# Glasses.net
KiCad netlist of a schematic drawn in EAGLE
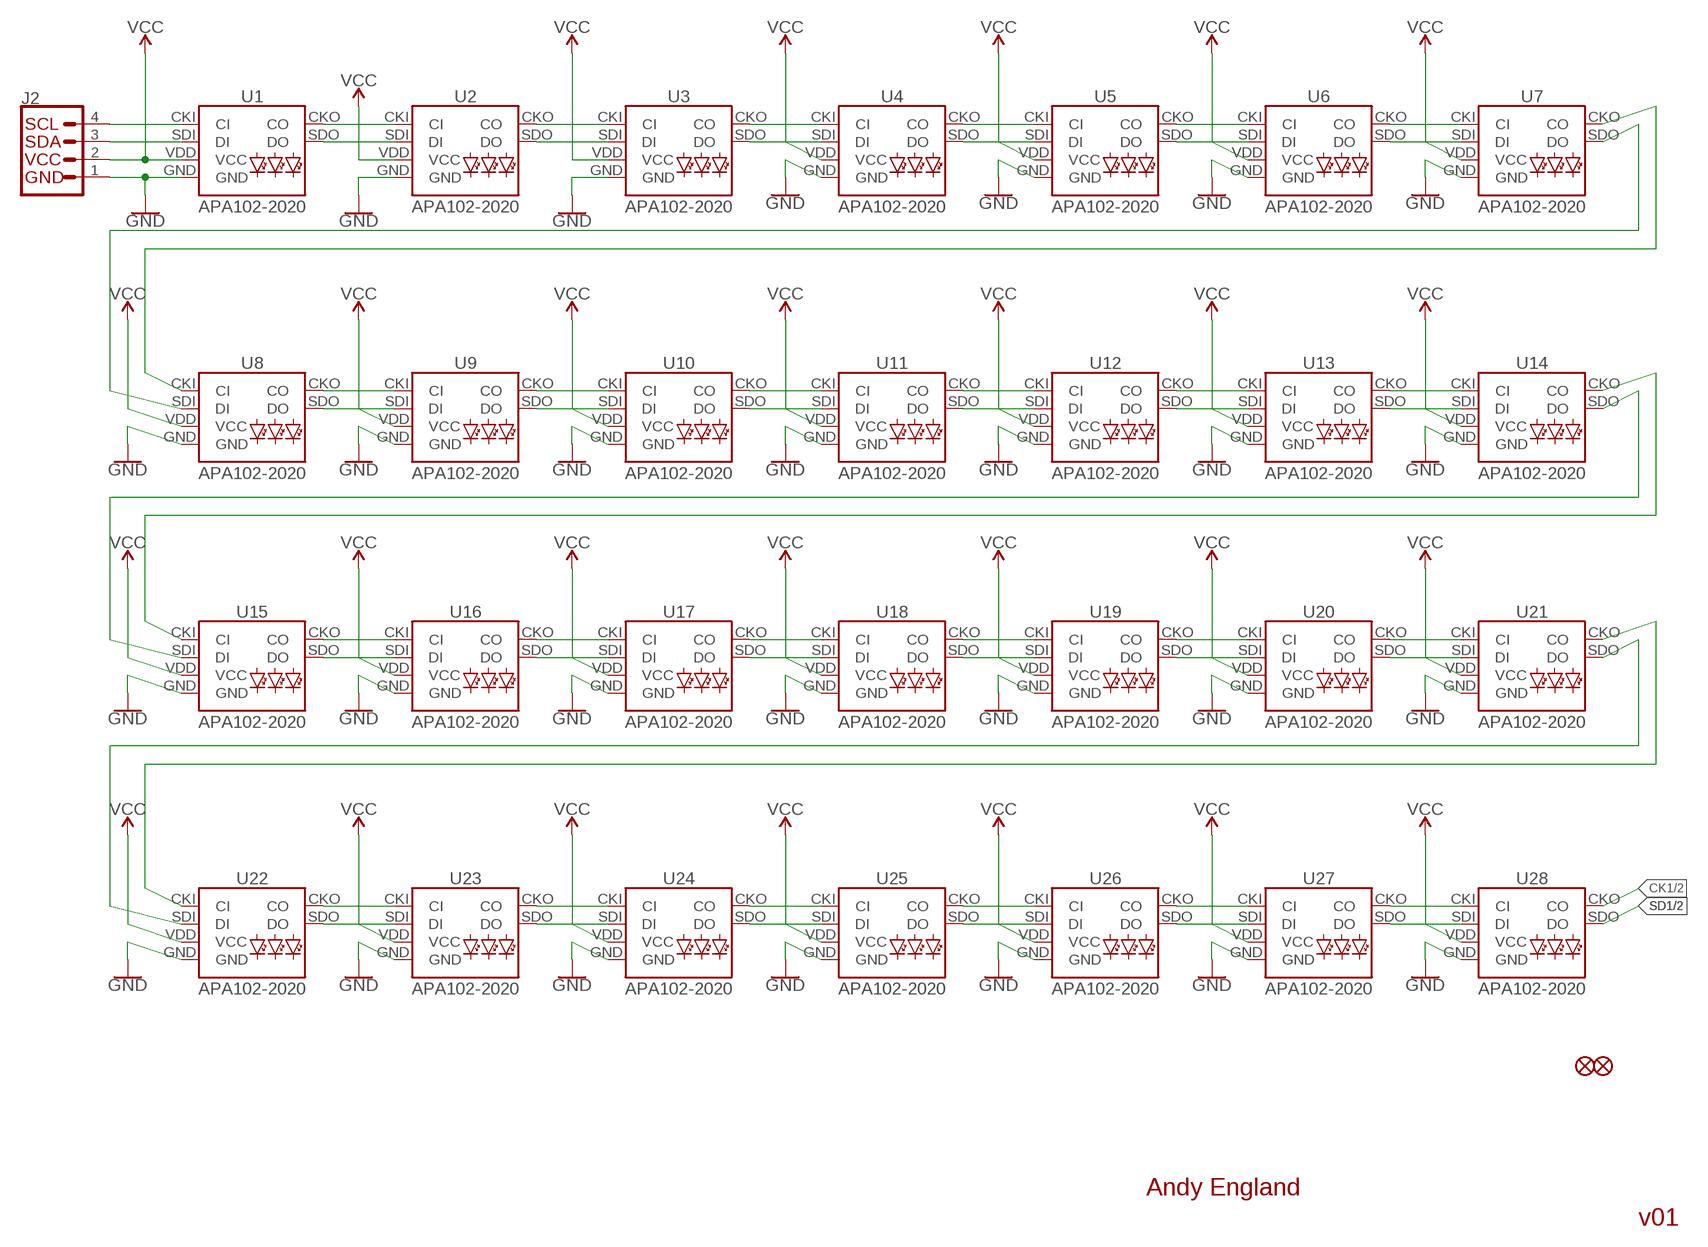
[diagram p0: schematic, sheet 1]
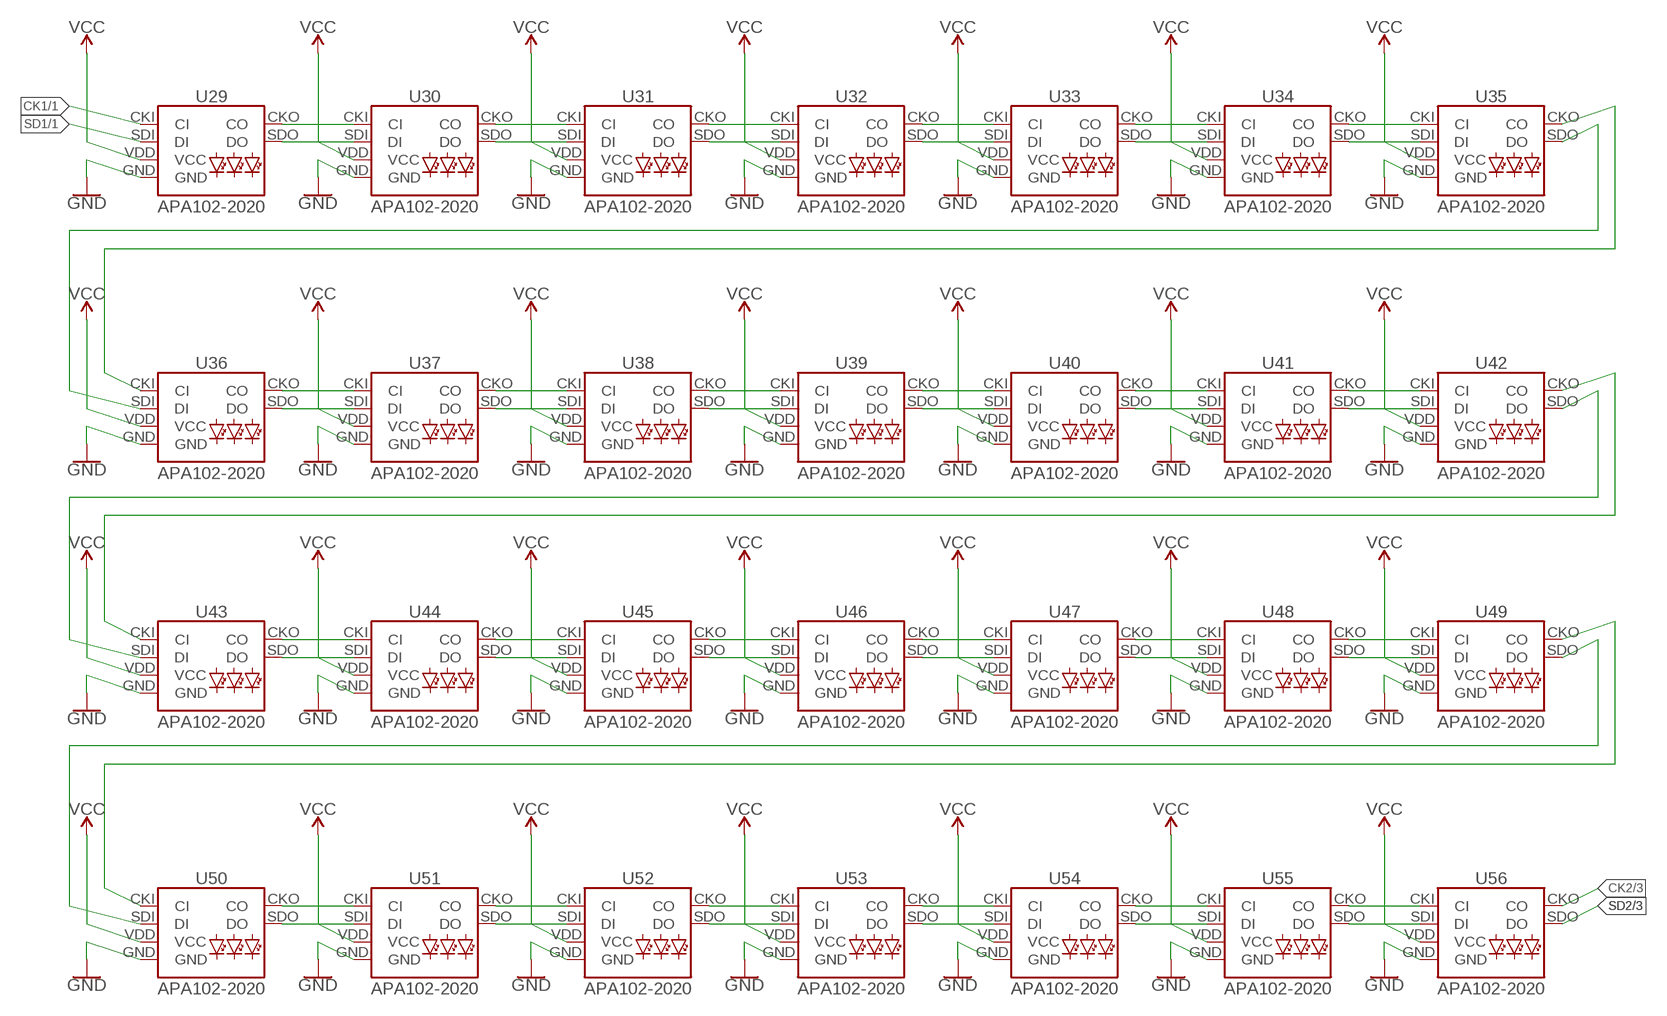
[diagram p1: schematic, sheet 2]
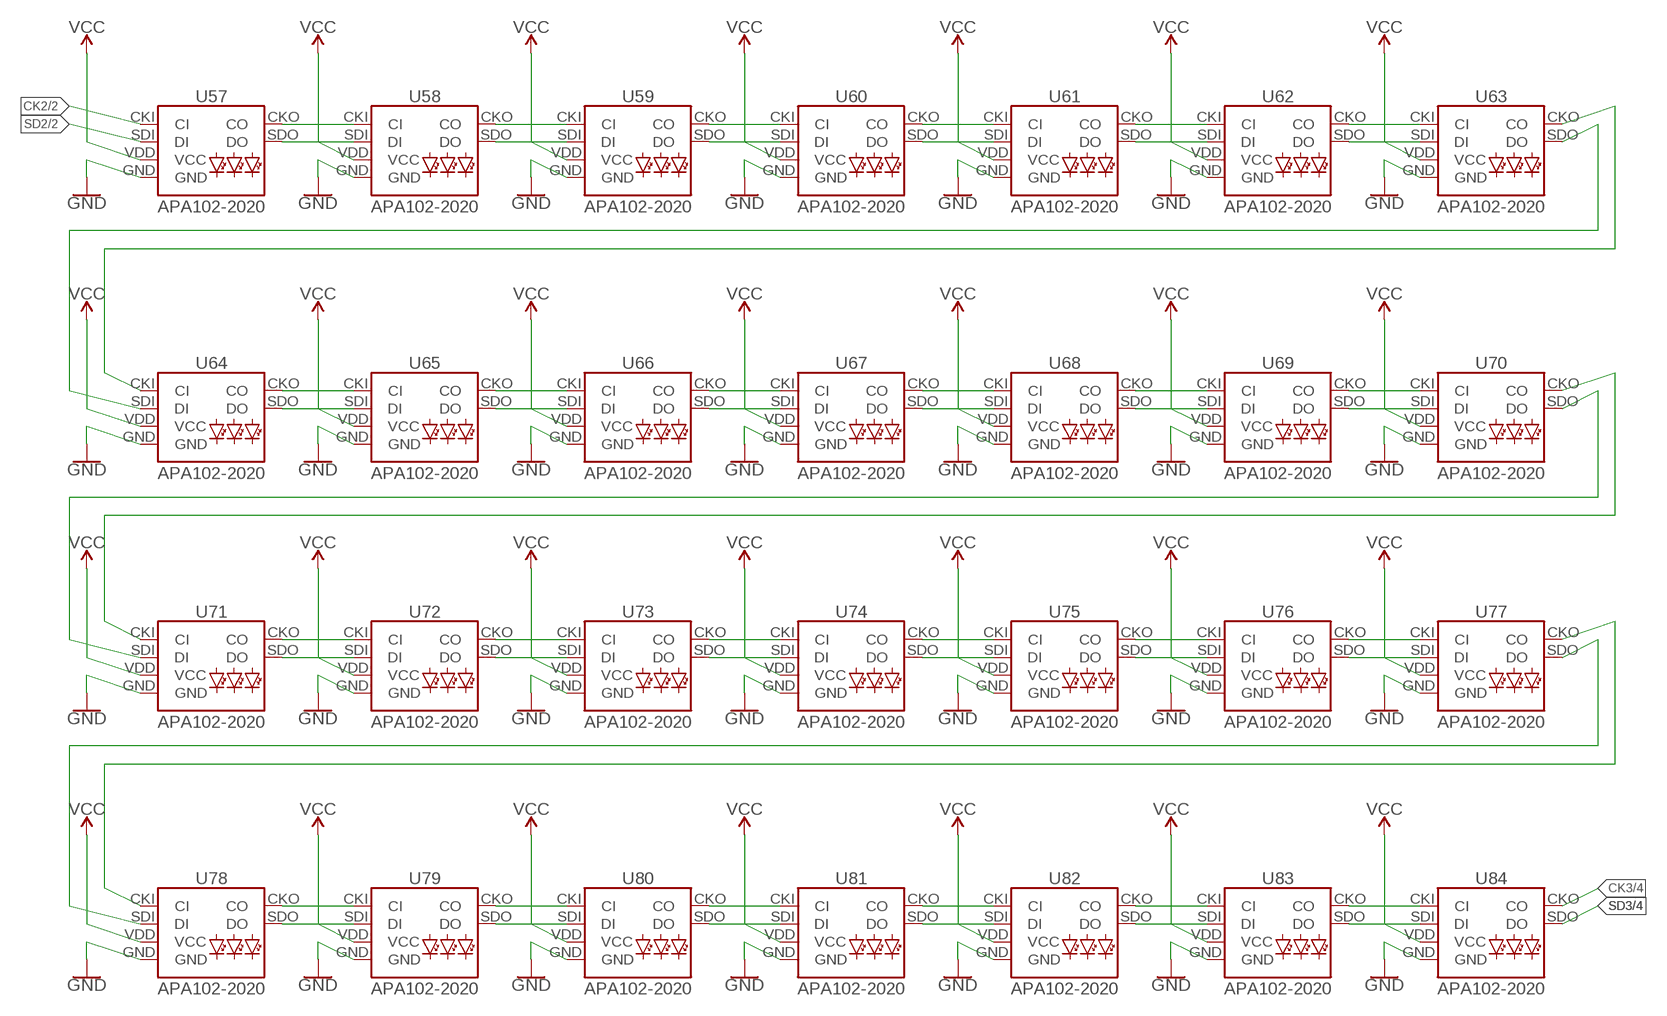
[diagram p2: schematic, sheet 3]
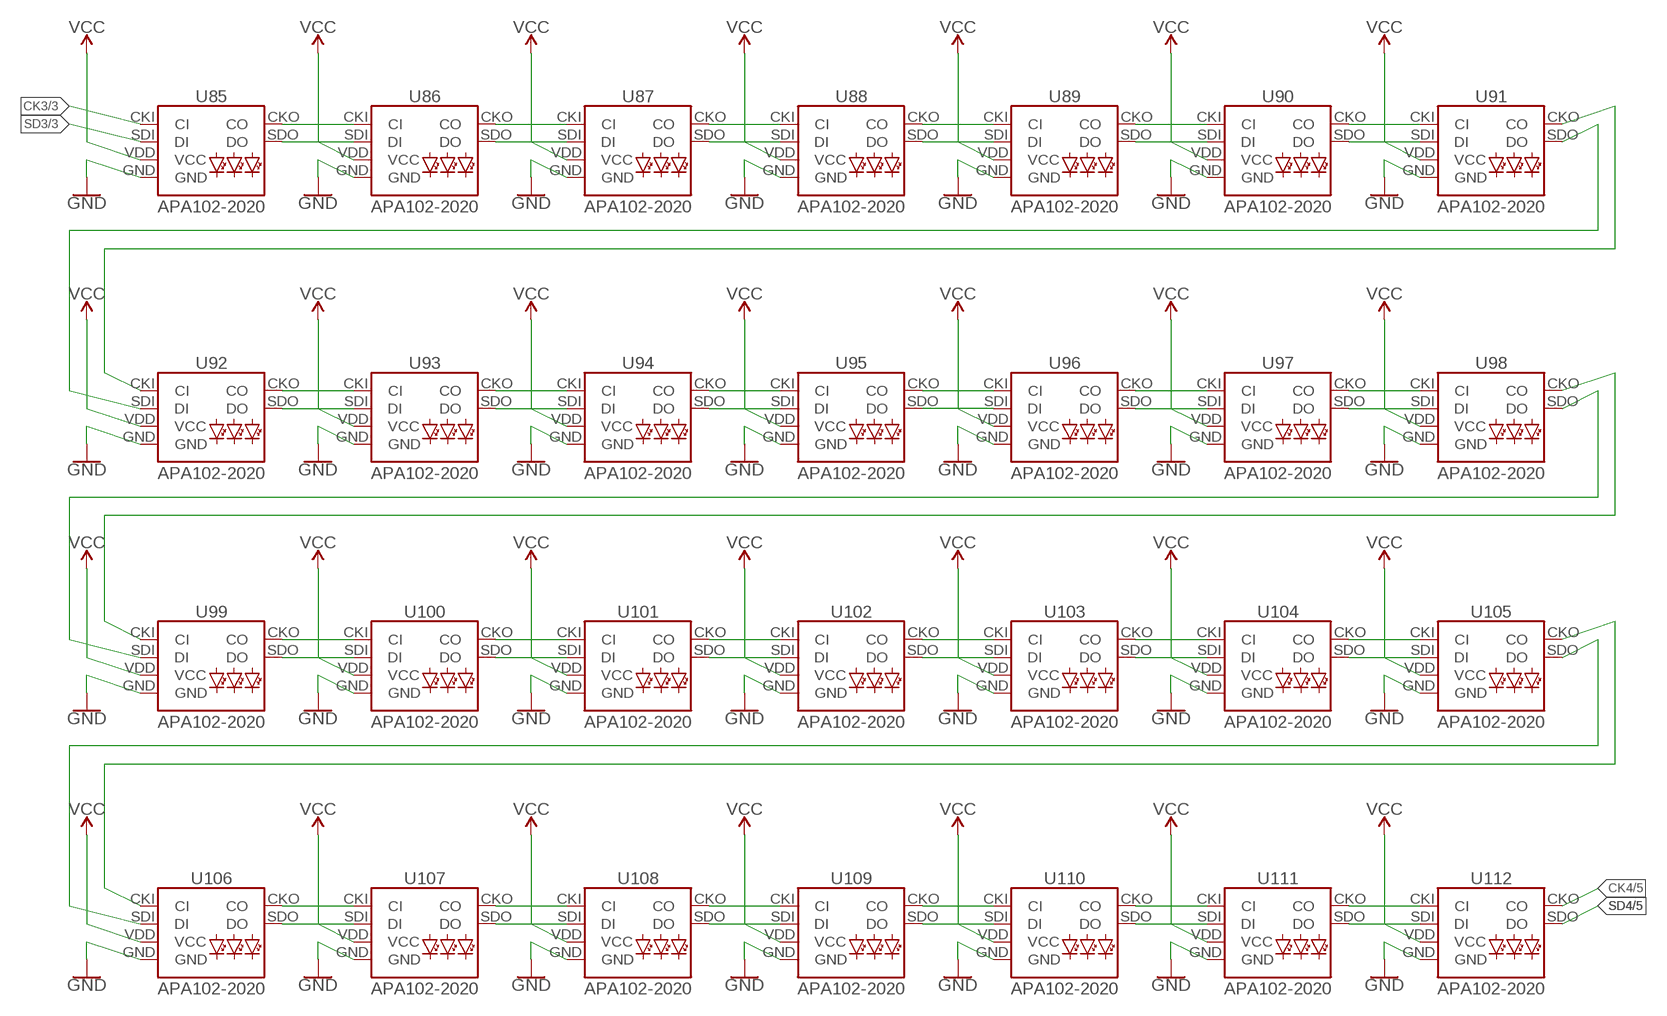
[diagram p3: schematic, sheet 4]
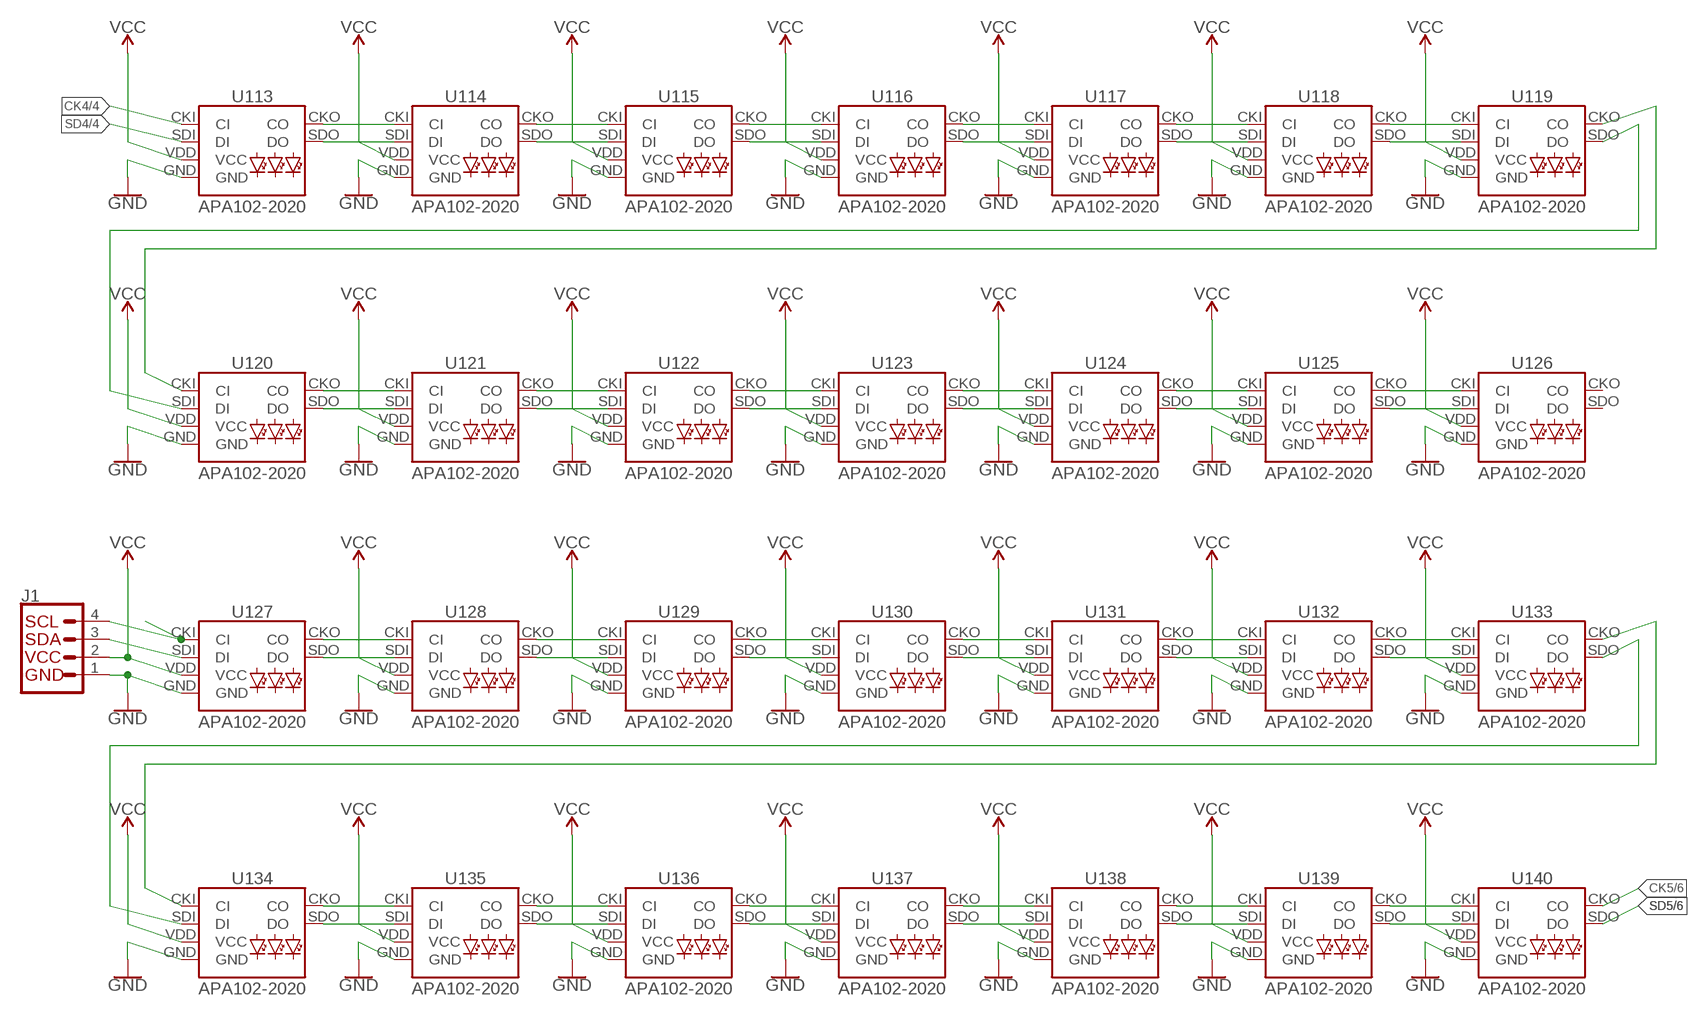
[diagram p4: schematic, sheet 5]
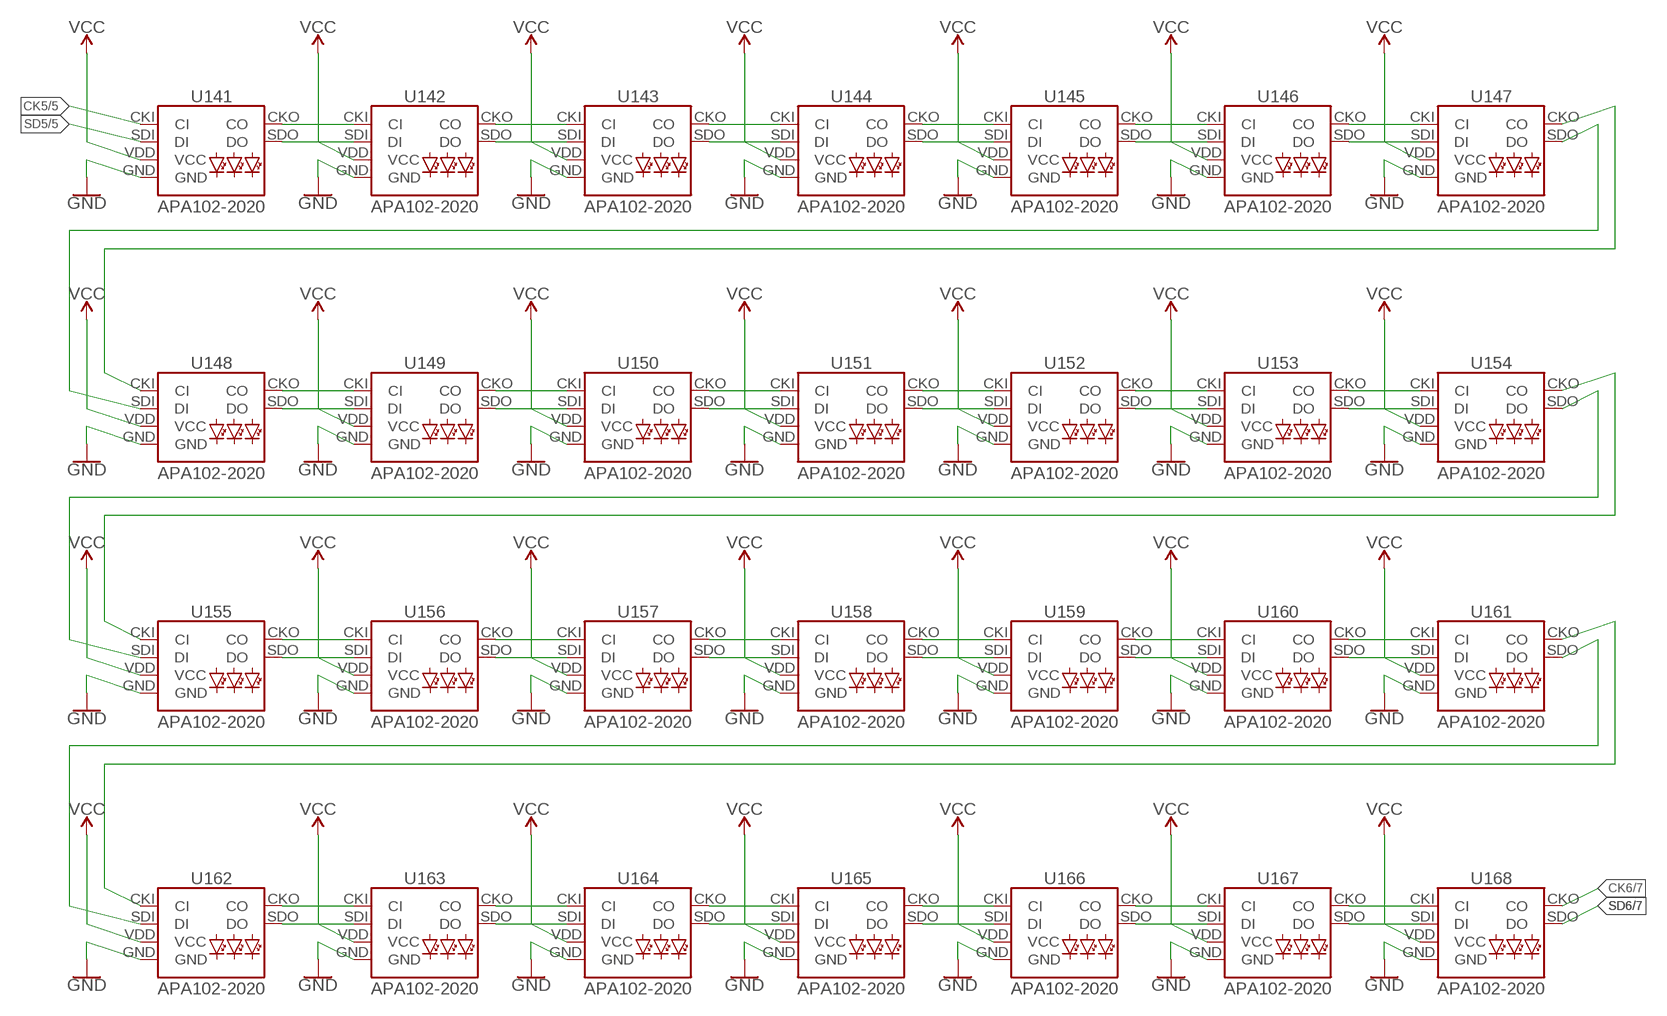
[diagram p5: schematic, sheet 6]
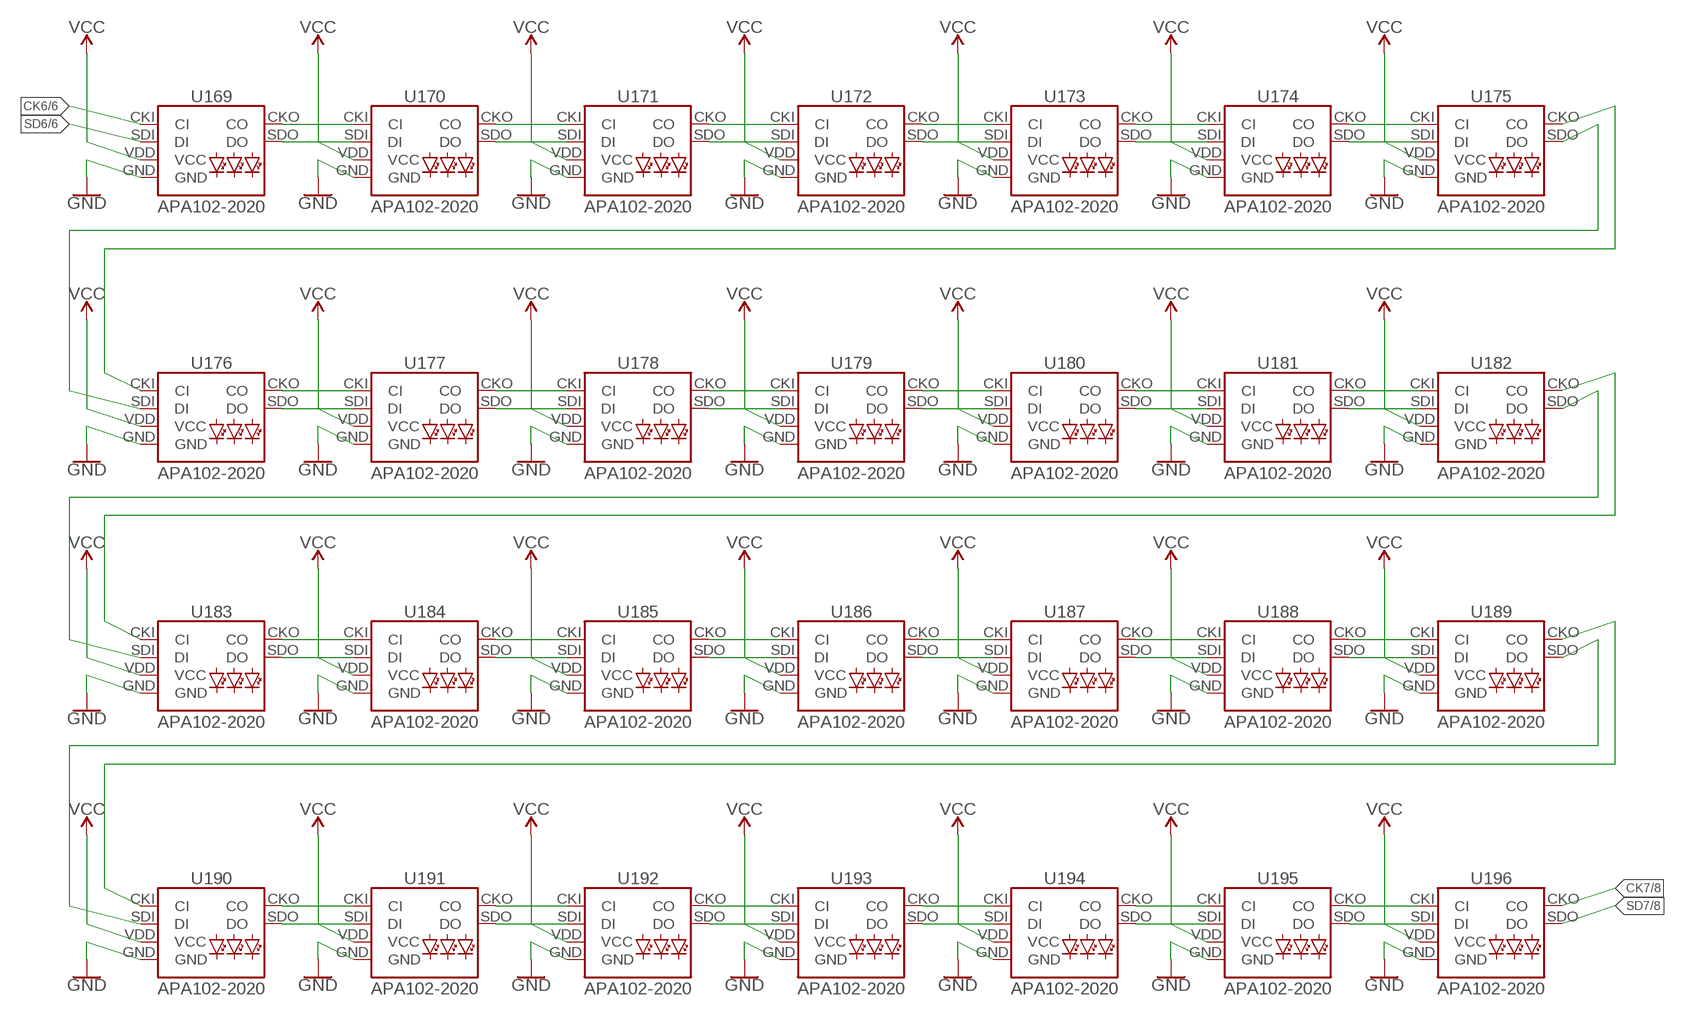
[diagram p6: schematic, sheet 7]
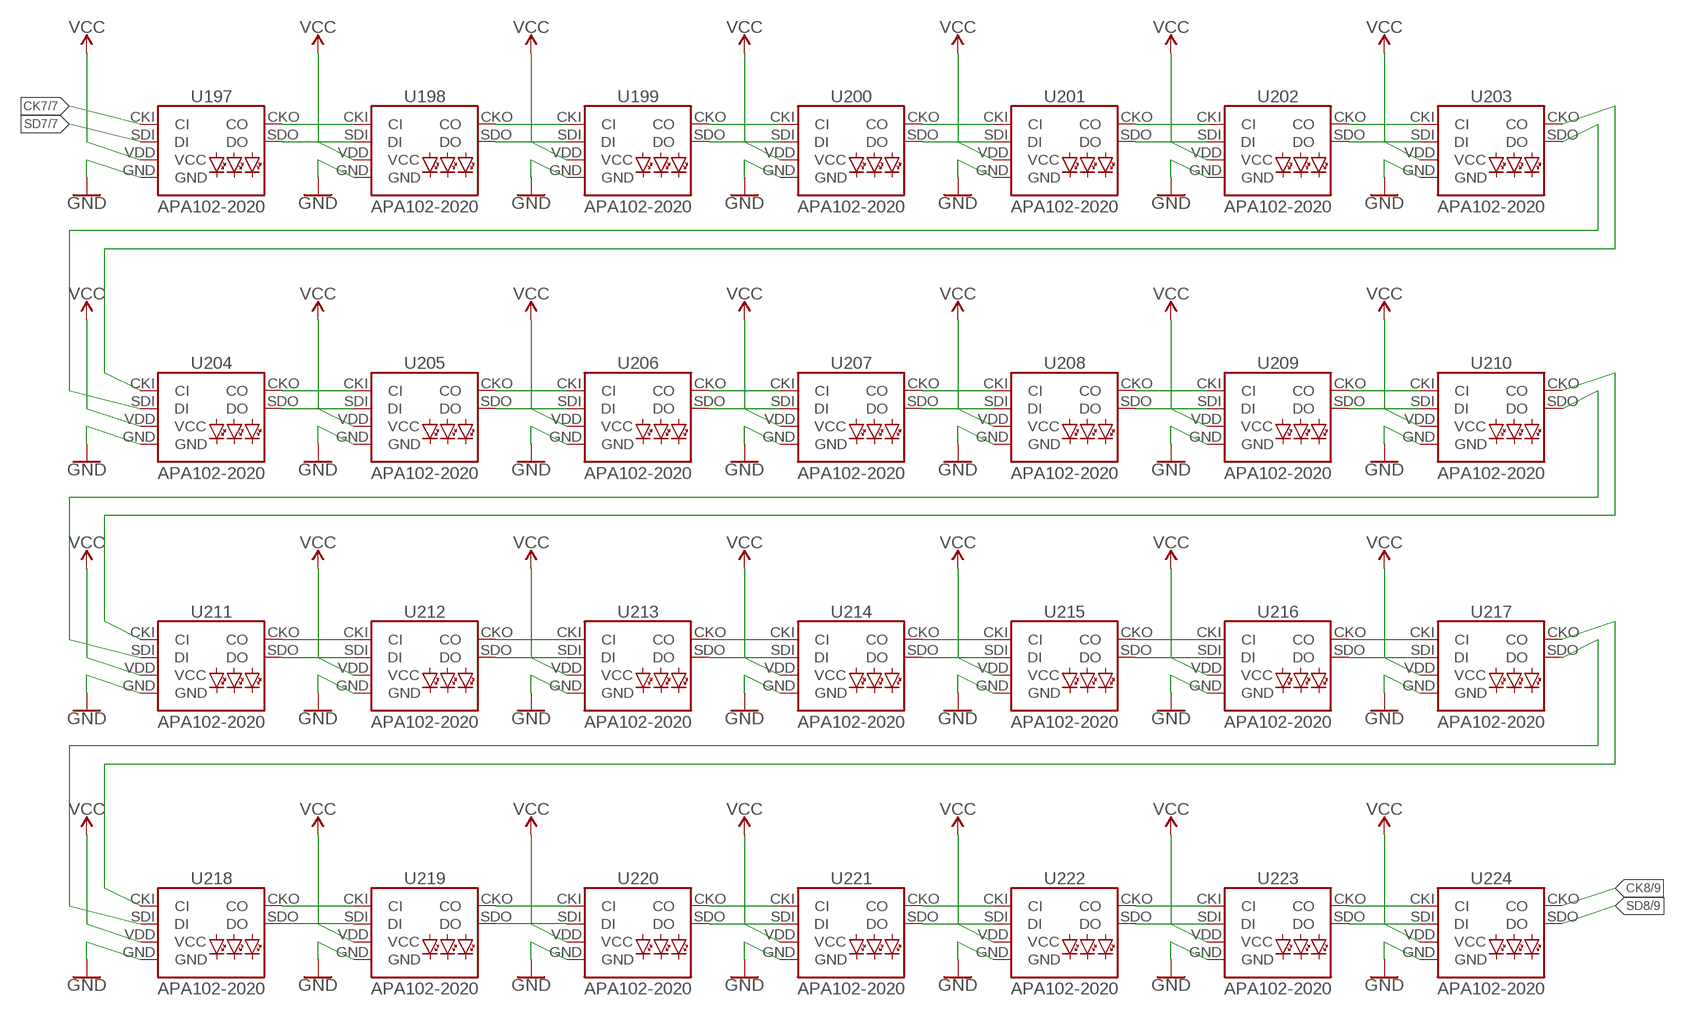
[diagram p7: schematic, sheet 8]
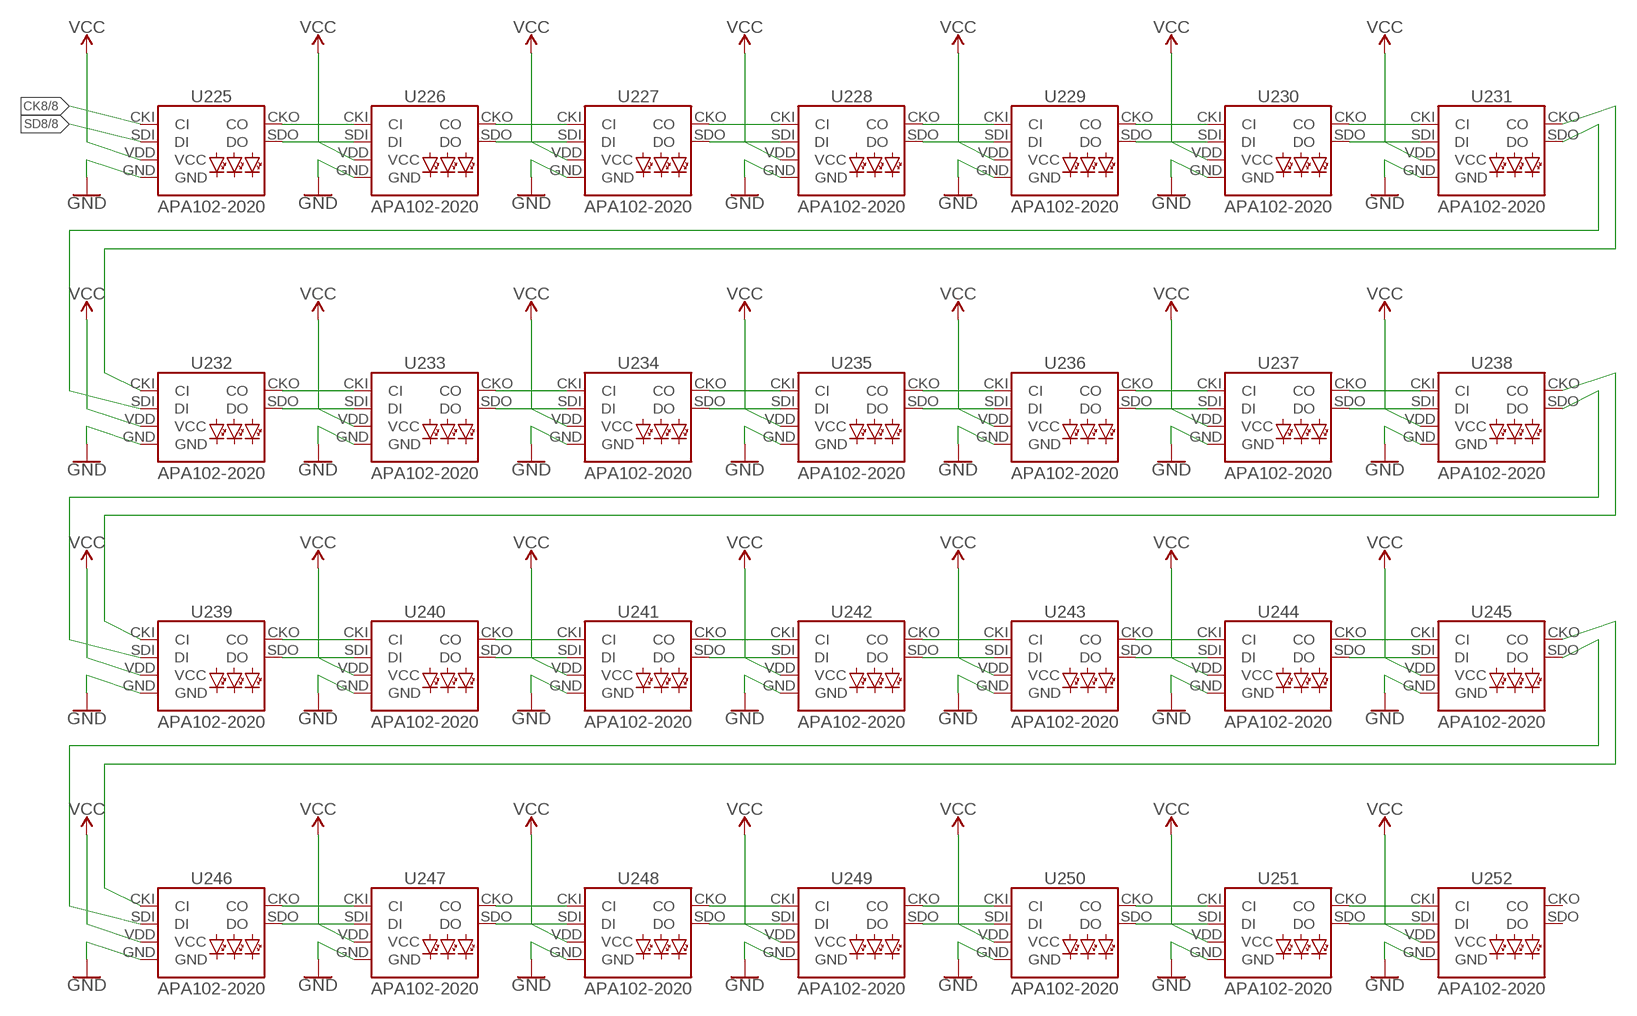
[diagram p8: schematic, sheet 9]

(export (version "E")
  (design (tool "Eeschema 10.0.6"))
  (components
    (comp (ref "U29")
      (value "APA102-2020")
      (footprint "eagle-import:APA102-2020")
      (libsource (lib "eagle-import") (part "APA102-2020"))
    )
    (comp (ref "U30")
      (value "APA102-2020")
      (footprint "eagle-import:APA102-2020")
      (libsource (lib "eagle-import") (part "APA102-2020"))
    )
    (comp (ref "U31")
      (value "APA102-2020")
      (footprint "eagle-import:APA102-2020")
      (libsource (lib "eagle-import") (part "APA102-2020"))
    )
    (comp (ref "U32")
      (value "APA102-2020")
      (footprint "eagle-import:APA102-2020")
      (libsource (lib "eagle-import") (part "APA102-2020"))
    )
    (comp (ref "U33")
      (value "APA102-2020")
      (footprint "eagle-import:APA102-2020")
      (libsource (lib "eagle-import") (part "APA102-2020"))
    )
    (comp (ref "U34")
      (value "APA102-2020")
      (footprint "eagle-import:APA102-2020")
      (libsource (lib "eagle-import") (part "APA102-2020"))
    )
    (comp (ref "U35")
      (value "APA102-2020")
      (footprint "eagle-import:APA102-2020")
      (libsource (lib "eagle-import") (part "APA102-2020"))
    )
    (comp (ref "U36")
      (value "APA102-2020")
      (footprint "eagle-import:APA102-2020")
      (libsource (lib "eagle-import") (part "APA102-2020"))
    )
    (comp (ref "U37")
      (value "APA102-2020")
      (footprint "eagle-import:APA102-2020")
      (libsource (lib "eagle-import") (part "APA102-2020"))
    )
    (comp (ref "U38")
      (value "APA102-2020")
      (footprint "eagle-import:APA102-2020")
      (libsource (lib "eagle-import") (part "APA102-2020"))
    )
    (comp (ref "U39")
      (value "APA102-2020")
      (footprint "eagle-import:APA102-2020")
      (libsource (lib "eagle-import") (part "APA102-2020"))
    )
    (comp (ref "U40")
      (value "APA102-2020")
      (footprint "eagle-import:APA102-2020")
      (libsource (lib "eagle-import") (part "APA102-2020"))
    )
    (comp (ref "U41")
      (value "APA102-2020")
      (footprint "eagle-import:APA102-2020")
      (libsource (lib "eagle-import") (part "APA102-2020"))
    )
    (comp (ref "U42")
      (value "APA102-2020")
      (footprint "eagle-import:APA102-2020")
      (libsource (lib "eagle-import") (part "APA102-2020"))
    )
    (comp (ref "U43")
      (value "APA102-2020")
      (footprint "eagle-import:APA102-2020")
      (libsource (lib "eagle-import") (part "APA102-2020"))
    )
    (comp (ref "U44")
      (value "APA102-2020")
      (footprint "eagle-import:APA102-2020")
      (libsource (lib "eagle-import") (part "APA102-2020"))
    )
    (comp (ref "U45")
      (value "APA102-2020")
      (footprint "eagle-import:APA102-2020")
      (libsource (lib "eagle-import") (part "APA102-2020"))
    )
    (comp (ref "U46")
      (value "APA102-2020")
      (footprint "eagle-import:APA102-2020")
      (libsource (lib "eagle-import") (part "APA102-2020"))
    )
    (comp (ref "U47")
      (value "APA102-2020")
      (footprint "eagle-import:APA102-2020")
      (libsource (lib "eagle-import") (part "APA102-2020"))
    )
    (comp (ref "U48")
      (value "APA102-2020")
      (footprint "eagle-import:APA102-2020")
      (libsource (lib "eagle-import") (part "APA102-2020"))
    )
    (comp (ref "U49")
      (value "APA102-2020")
      (footprint "eagle-import:APA102-2020")
      (libsource (lib "eagle-import") (part "APA102-2020"))
    )
    (comp (ref "U50")
      (value "APA102-2020")
      (footprint "eagle-import:APA102-2020")
      (libsource (lib "eagle-import") (part "APA102-2020"))
    )
    (comp (ref "U51")
      (value "APA102-2020")
      (footprint "eagle-import:APA102-2020")
      (libsource (lib "eagle-import") (part "APA102-2020"))
    )
    (comp (ref "U52")
      (value "APA102-2020")
      (footprint "eagle-import:APA102-2020")
      (libsource (lib "eagle-import") (part "APA102-2020"))
    )
    (comp (ref "U53")
      (value "APA102-2020")
      (footprint "eagle-import:APA102-2020")
      (libsource (lib "eagle-import") (part "APA102-2020"))
    )
    (comp (ref "U54")
      (value "APA102-2020")
      (footprint "eagle-import:APA102-2020")
      (libsource (lib "eagle-import") (part "APA102-2020"))
    )
    (comp (ref "U55")
      (value "APA102-2020")
      (footprint "eagle-import:APA102-2020")
      (libsource (lib "eagle-import") (part "APA102-2020"))
    )
    (comp (ref "U56")
      (value "APA102-2020")
      (footprint "eagle-import:APA102-2020")
      (libsource (lib "eagle-import") (part "APA102-2020"))
    )
    (comp (ref "U225")
      (value "APA102-2020")
      (footprint "eagle-import:APA102-2020")
      (libsource (lib "eagle-import") (part "APA102-2020"))
    )
    (comp (ref "U226")
      (value "APA102-2020")
      (footprint "eagle-import:APA102-2020")
      (libsource (lib "eagle-import") (part "APA102-2020"))
    )
    (comp (ref "U227")
      (value "APA102-2020")
      (footprint "eagle-import:APA102-2020")
      (libsource (lib "eagle-import") (part "APA102-2020"))
    )
    (comp (ref "U228")
      (value "APA102-2020")
      (footprint "eagle-import:APA102-2020")
      (libsource (lib "eagle-import") (part "APA102-2020"))
    )
    (comp (ref "U229")
      (value "APA102-2020")
      (footprint "eagle-import:APA102-2020")
      (libsource (lib "eagle-import") (part "APA102-2020"))
    )
    (comp (ref "U230")
      (value "APA102-2020")
      (footprint "eagle-import:APA102-2020")
      (libsource (lib "eagle-import") (part "APA102-2020"))
    )
    (comp (ref "U231")
      (value "APA102-2020")
      (footprint "eagle-import:APA102-2020")
      (libsource (lib "eagle-import") (part "APA102-2020"))
    )
    (comp (ref "U232")
      (value "APA102-2020")
      (footprint "eagle-import:APA102-2020")
      (libsource (lib "eagle-import") (part "APA102-2020"))
    )
    (comp (ref "U233")
      (value "APA102-2020")
      (footprint "eagle-import:APA102-2020")
      (libsource (lib "eagle-import") (part "APA102-2020"))
    )
    (comp (ref "U234")
      (value "APA102-2020")
      (footprint "eagle-import:APA102-2020")
      (libsource (lib "eagle-import") (part "APA102-2020"))
    )
    (comp (ref "U235")
      (value "APA102-2020")
      (footprint "eagle-import:APA102-2020")
      (libsource (lib "eagle-import") (part "APA102-2020"))
    )
    (comp (ref "U236")
      (value "APA102-2020")
      (footprint "eagle-import:APA102-2020")
      (libsource (lib "eagle-import") (part "APA102-2020"))
    )
    (comp (ref "U237")
      (value "APA102-2020")
      (footprint "eagle-import:APA102-2020")
      (libsource (lib "eagle-import") (part "APA102-2020"))
    )
    (comp (ref "U238")
      (value "APA102-2020")
      (footprint "eagle-import:APA102-2020")
      (libsource (lib "eagle-import") (part "APA102-2020"))
    )
    (comp (ref "U239")
      (value "APA102-2020")
      (footprint "eagle-import:APA102-2020")
      (libsource (lib "eagle-import") (part "APA102-2020"))
    )
    (comp (ref "U240")
      (value "APA102-2020")
      (footprint "eagle-import:APA102-2020")
      (libsource (lib "eagle-import") (part "APA102-2020"))
    )
    (comp (ref "U241")
      (value "APA102-2020")
      (footprint "eagle-import:APA102-2020")
      (libsource (lib "eagle-import") (part "APA102-2020"))
    )
    (comp (ref "U242")
      (value "APA102-2020")
      (footprint "eagle-import:APA102-2020")
      (libsource (lib "eagle-import") (part "APA102-2020"))
    )
    (comp (ref "U243")
      (value "APA102-2020")
      (footprint "eagle-import:APA102-2020")
      (libsource (lib "eagle-import") (part "APA102-2020"))
    )
    (comp (ref "U244")
      (value "APA102-2020")
      (footprint "eagle-import:APA102-2020")
      (libsource (lib "eagle-import") (part "APA102-2020"))
    )
    (comp (ref "U245")
      (value "APA102-2020")
      (footprint "eagle-import:APA102-2020")
      (libsource (lib "eagle-import") (part "APA102-2020"))
    )
    (comp (ref "U246")
      (value "APA102-2020")
      (footprint "eagle-import:APA102-2020")
      (libsource (lib "eagle-import") (part "APA102-2020"))
    )
    (comp (ref "U247")
      (value "APA102-2020")
      (footprint "eagle-import:APA102-2020")
      (libsource (lib "eagle-import") (part "APA102-2020"))
    )
    (comp (ref "U248")
      (value "APA102-2020")
      (footprint "eagle-import:APA102-2020")
      (libsource (lib "eagle-import") (part "APA102-2020"))
    )
    (comp (ref "U249")
      (value "APA102-2020")
      (footprint "eagle-import:APA102-2020")
      (libsource (lib "eagle-import") (part "APA102-2020"))
    )
    (comp (ref "U250")
      (value "APA102-2020")
      (footprint "eagle-import:APA102-2020")
      (libsource (lib "eagle-import") (part "APA102-2020"))
    )
    (comp (ref "U251")
      (value "APA102-2020")
      (footprint "eagle-import:APA102-2020")
      (libsource (lib "eagle-import") (part "APA102-2020"))
    )
    (comp (ref "U252")
      (value "APA102-2020")
      (footprint "eagle-import:APA102-2020")
      (libsource (lib "eagle-import") (part "APA102-2020"))
    )
    (comp (ref "U197")
      (value "APA102-2020")
      (footprint "eagle-import:APA102-2020")
      (libsource (lib "eagle-import") (part "APA102-2020"))
    )
    (comp (ref "U198")
      (value "APA102-2020")
      (footprint "eagle-import:APA102-2020")
      (libsource (lib "eagle-import") (part "APA102-2020"))
    )
    (comp (ref "U199")
      (value "APA102-2020")
      (footprint "eagle-import:APA102-2020")
      (libsource (lib "eagle-import") (part "APA102-2020"))
    )
    (comp (ref "U200")
      (value "APA102-2020")
      (footprint "eagle-import:APA102-2020")
      (libsource (lib "eagle-import") (part "APA102-2020"))
    )
    (comp (ref "U201")
      (value "APA102-2020")
      (footprint "eagle-import:APA102-2020")
      (libsource (lib "eagle-import") (part "APA102-2020"))
    )
    (comp (ref "U202")
      (value "APA102-2020")
      (footprint "eagle-import:APA102-2020")
      (libsource (lib "eagle-import") (part "APA102-2020"))
    )
    (comp (ref "U203")
      (value "APA102-2020")
      (footprint "eagle-import:APA102-2020")
      (libsource (lib "eagle-import") (part "APA102-2020"))
    )
    (comp (ref "U204")
      (value "APA102-2020")
      (footprint "eagle-import:APA102-2020")
      (libsource (lib "eagle-import") (part "APA102-2020"))
    )
    (comp (ref "U205")
      (value "APA102-2020")
      (footprint "eagle-import:APA102-2020")
      (libsource (lib "eagle-import") (part "APA102-2020"))
    )
    (comp (ref "U206")
      (value "APA102-2020")
      (footprint "eagle-import:APA102-2020")
      (libsource (lib "eagle-import") (part "APA102-2020"))
    )
    (comp (ref "U207")
      (value "APA102-2020")
      (footprint "eagle-import:APA102-2020")
      (libsource (lib "eagle-import") (part "APA102-2020"))
    )
    (comp (ref "U208")
      (value "APA102-2020")
      (footprint "eagle-import:APA102-2020")
      (libsource (lib "eagle-import") (part "APA102-2020"))
    )
    (comp (ref "U209")
      (value "APA102-2020")
      (footprint "eagle-import:APA102-2020")
      (libsource (lib "eagle-import") (part "APA102-2020"))
    )
    (comp (ref "U210")
      (value "APA102-2020")
      (footprint "eagle-import:APA102-2020")
      (libsource (lib "eagle-import") (part "APA102-2020"))
    )
    (comp (ref "U211")
      (value "APA102-2020")
      (footprint "eagle-import:APA102-2020")
      (libsource (lib "eagle-import") (part "APA102-2020"))
    )
    (comp (ref "U212")
      (value "APA102-2020")
      (footprint "eagle-import:APA102-2020")
      (libsource (lib "eagle-import") (part "APA102-2020"))
    )
    (comp (ref "U213")
      (value "APA102-2020")
      (footprint "eagle-import:APA102-2020")
      (libsource (lib "eagle-import") (part "APA102-2020"))
    )
    (comp (ref "U214")
      (value "APA102-2020")
      (footprint "eagle-import:APA102-2020")
      (libsource (lib "eagle-import") (part "APA102-2020"))
    )
    (comp (ref "U215")
      (value "APA102-2020")
      (footprint "eagle-import:APA102-2020")
      (libsource (lib "eagle-import") (part "APA102-2020"))
    )
    (comp (ref "U216")
      (value "APA102-2020")
      (footprint "eagle-import:APA102-2020")
      (libsource (lib "eagle-import") (part "APA102-2020"))
    )
    (comp (ref "U217")
      (value "APA102-2020")
      (footprint "eagle-import:APA102-2020")
      (libsource (lib "eagle-import") (part "APA102-2020"))
    )
    (comp (ref "U218")
      (value "APA102-2020")
      (footprint "eagle-import:APA102-2020")
      (libsource (lib "eagle-import") (part "APA102-2020"))
    )
    (comp (ref "U219")
      (value "APA102-2020")
      (footprint "eagle-import:APA102-2020")
      (libsource (lib "eagle-import") (part "APA102-2020"))
    )
    (comp (ref "U220")
      (value "APA102-2020")
      (footprint "eagle-import:APA102-2020")
      (libsource (lib "eagle-import") (part "APA102-2020"))
    )
    (comp (ref "U221")
      (value "APA102-2020")
      (footprint "eagle-import:APA102-2020")
      (libsource (lib "eagle-import") (part "APA102-2020"))
    )
    (comp (ref "U222")
      (value "APA102-2020")
      (footprint "eagle-import:APA102-2020")
      (libsource (lib "eagle-import") (part "APA102-2020"))
    )
    (comp (ref "U223")
      (value "APA102-2020")
      (footprint "eagle-import:APA102-2020")
      (libsource (lib "eagle-import") (part "APA102-2020"))
    )
    (comp (ref "U224")
      (value "APA102-2020")
      (footprint "eagle-import:APA102-2020")
      (libsource (lib "eagle-import") (part "APA102-2020"))
    )
    (comp (ref "U169")
      (value "APA102-2020")
      (footprint "eagle-import:APA102-2020")
      (libsource (lib "eagle-import") (part "APA102-2020"))
    )
    (comp (ref "U170")
      (value "APA102-2020")
      (footprint "eagle-import:APA102-2020")
      (libsource (lib "eagle-import") (part "APA102-2020"))
    )
    (comp (ref "U171")
      (value "APA102-2020")
      (footprint "eagle-import:APA102-2020")
      (libsource (lib "eagle-import") (part "APA102-2020"))
    )
    (comp (ref "U172")
      (value "APA102-2020")
      (footprint "eagle-import:APA102-2020")
      (libsource (lib "eagle-import") (part "APA102-2020"))
    )
    (comp (ref "U173")
      (value "APA102-2020")
      (footprint "eagle-import:APA102-2020")
      (libsource (lib "eagle-import") (part "APA102-2020"))
    )
    (comp (ref "U174")
      (value "APA102-2020")
      (footprint "eagle-import:APA102-2020")
      (libsource (lib "eagle-import") (part "APA102-2020"))
    )
    (comp (ref "U175")
      (value "APA102-2020")
      (footprint "eagle-import:APA102-2020")
      (libsource (lib "eagle-import") (part "APA102-2020"))
    )
    (comp (ref "U176")
      (value "APA102-2020")
      (footprint "eagle-import:APA102-2020")
      (libsource (lib "eagle-import") (part "APA102-2020"))
    )
    (comp (ref "U177")
      (value "APA102-2020")
      (footprint "eagle-import:APA102-2020")
      (libsource (lib "eagle-import") (part "APA102-2020"))
    )
    (comp (ref "U178")
      (value "APA102-2020")
      (footprint "eagle-import:APA102-2020")
      (libsource (lib "eagle-import") (part "APA102-2020"))
    )
    (comp (ref "U179")
      (value "APA102-2020")
      (footprint "eagle-import:APA102-2020")
      (libsource (lib "eagle-import") (part "APA102-2020"))
    )
    (comp (ref "U180")
      (value "APA102-2020")
      (footprint "eagle-import:APA102-2020")
      (libsource (lib "eagle-import") (part "APA102-2020"))
    )
    (comp (ref "U181")
      (value "APA102-2020")
      (footprint "eagle-import:APA102-2020")
      (libsource (lib "eagle-import") (part "APA102-2020"))
    )
    (comp (ref "U182")
      (value "APA102-2020")
      (footprint "eagle-import:APA102-2020")
      (libsource (lib "eagle-import") (part "APA102-2020"))
    )
    (comp (ref "U183")
      (value "APA102-2020")
      (footprint "eagle-import:APA102-2020")
      (libsource (lib "eagle-import") (part "APA102-2020"))
    )
    (comp (ref "U184")
      (value "APA102-2020")
      (footprint "eagle-import:APA102-2020")
      (libsource (lib "eagle-import") (part "APA102-2020"))
    )
    (comp (ref "U185")
      (value "APA102-2020")
      (footprint "eagle-import:APA102-2020")
      (libsource (lib "eagle-import") (part "APA102-2020"))
    )
    (comp (ref "U186")
      (value "APA102-2020")
      (footprint "eagle-import:APA102-2020")
      (libsource (lib "eagle-import") (part "APA102-2020"))
    )
    (comp (ref "U187")
      (value "APA102-2020")
      (footprint "eagle-import:APA102-2020")
      (libsource (lib "eagle-import") (part "APA102-2020"))
    )
    (comp (ref "U188")
      (value "APA102-2020")
      (footprint "eagle-import:APA102-2020")
      (libsource (lib "eagle-import") (part "APA102-2020"))
    )
    (comp (ref "U189")
      (value "APA102-2020")
      (footprint "eagle-import:APA102-2020")
      (libsource (lib "eagle-import") (part "APA102-2020"))
    )
    (comp (ref "U190")
      (value "APA102-2020")
      (footprint "eagle-import:APA102-2020")
      (libsource (lib "eagle-import") (part "APA102-2020"))
    )
    (comp (ref "U191")
      (value "APA102-2020")
      (footprint "eagle-import:APA102-2020")
      (libsource (lib "eagle-import") (part "APA102-2020"))
    )
    (comp (ref "U192")
      (value "APA102-2020")
      (footprint "eagle-import:APA102-2020")
      (libsource (lib "eagle-import") (part "APA102-2020"))
    )
    (comp (ref "U193")
      (value "APA102-2020")
      (footprint "eagle-import:APA102-2020")
      (libsource (lib "eagle-import") (part "APA102-2020"))
    )
    (comp (ref "U194")
      (value "APA102-2020")
      (footprint "eagle-import:APA102-2020")
      (libsource (lib "eagle-import") (part "APA102-2020"))
    )
    (comp (ref "U195")
      (value "APA102-2020")
      (footprint "eagle-import:APA102-2020")
      (libsource (lib "eagle-import") (part "APA102-2020"))
    )
    (comp (ref "U196")
      (value "APA102-2020")
      (footprint "eagle-import:APA102-2020")
      (libsource (lib "eagle-import") (part "APA102-2020"))
    )
    (comp (ref "U141")
      (value "APA102-2020")
      (footprint "eagle-import:APA102-2020")
      (libsource (lib "eagle-import") (part "APA102-2020"))
    )
    (comp (ref "U142")
      (value "APA102-2020")
      (footprint "eagle-import:APA102-2020")
      (libsource (lib "eagle-import") (part "APA102-2020"))
    )
    (comp (ref "U143")
      (value "APA102-2020")
      (footprint "eagle-import:APA102-2020")
      (libsource (lib "eagle-import") (part "APA102-2020"))
    )
    (comp (ref "U144")
      (value "APA102-2020")
      (footprint "eagle-import:APA102-2020")
      (libsource (lib "eagle-import") (part "APA102-2020"))
    )
    (comp (ref "U145")
      (value "APA102-2020")
      (footprint "eagle-import:APA102-2020")
      (libsource (lib "eagle-import") (part "APA102-2020"))
    )
    (comp (ref "U146")
      (value "APA102-2020")
      (footprint "eagle-import:APA102-2020")
      (libsource (lib "eagle-import") (part "APA102-2020"))
    )
    (comp (ref "U147")
      (value "APA102-2020")
      (footprint "eagle-import:APA102-2020")
      (libsource (lib "eagle-import") (part "APA102-2020"))
    )
    (comp (ref "U148")
      (value "APA102-2020")
      (footprint "eagle-import:APA102-2020")
      (libsource (lib "eagle-import") (part "APA102-2020"))
    )
    (comp (ref "U149")
      (value "APA102-2020")
      (footprint "eagle-import:APA102-2020")
      (libsource (lib "eagle-import") (part "APA102-2020"))
    )
    (comp (ref "U150")
      (value "APA102-2020")
      (footprint "eagle-import:APA102-2020")
      (libsource (lib "eagle-import") (part "APA102-2020"))
    )
    (comp (ref "U151")
      (value "APA102-2020")
      (footprint "eagle-import:APA102-2020")
      (libsource (lib "eagle-import") (part "APA102-2020"))
    )
    (comp (ref "U152")
      (value "APA102-2020")
      (footprint "eagle-import:APA102-2020")
      (libsource (lib "eagle-import") (part "APA102-2020"))
    )
    (comp (ref "U153")
      (value "APA102-2020")
      (footprint "eagle-import:APA102-2020")
      (libsource (lib "eagle-import") (part "APA102-2020"))
    )
    (comp (ref "U154")
      (value "APA102-2020")
      (footprint "eagle-import:APA102-2020")
      (libsource (lib "eagle-import") (part "APA102-2020"))
    )
    (comp (ref "U155")
      (value "APA102-2020")
      (footprint "eagle-import:APA102-2020")
      (libsource (lib "eagle-import") (part "APA102-2020"))
    )
    (comp (ref "U156")
      (value "APA102-2020")
      (footprint "eagle-import:APA102-2020")
      (libsource (lib "eagle-import") (part "APA102-2020"))
    )
    (comp (ref "U157")
      (value "APA102-2020")
      (footprint "eagle-import:APA102-2020")
      (libsource (lib "eagle-import") (part "APA102-2020"))
    )
    (comp (ref "U158")
      (value "APA102-2020")
      (footprint "eagle-import:APA102-2020")
      (libsource (lib "eagle-import") (part "APA102-2020"))
    )
    (comp (ref "U159")
      (value "APA102-2020")
      (footprint "eagle-import:APA102-2020")
      (libsource (lib "eagle-import") (part "APA102-2020"))
    )
    (comp (ref "U160")
      (value "APA102-2020")
      (footprint "eagle-import:APA102-2020")
      (libsource (lib "eagle-import") (part "APA102-2020"))
    )
    (comp (ref "U161")
      (value "APA102-2020")
      (footprint "eagle-import:APA102-2020")
      (libsource (lib "eagle-import") (part "APA102-2020"))
    )
    (comp (ref "U162")
      (value "APA102-2020")
      (footprint "eagle-import:APA102-2020")
      (libsource (lib "eagle-import") (part "APA102-2020"))
    )
    (comp (ref "U163")
      (value "APA102-2020")
      (footprint "eagle-import:APA102-2020")
      (libsource (lib "eagle-import") (part "APA102-2020"))
    )
    (comp (ref "U164")
      (value "APA102-2020")
      (footprint "eagle-import:APA102-2020")
      (libsource (lib "eagle-import") (part "APA102-2020"))
    )
    (comp (ref "U165")
      (value "APA102-2020")
      (footprint "eagle-import:APA102-2020")
      (libsource (lib "eagle-import") (part "APA102-2020"))
    )
    (comp (ref "U166")
      (value "APA102-2020")
      (footprint "eagle-import:APA102-2020")
      (libsource (lib "eagle-import") (part "APA102-2020"))
    )
    (comp (ref "U167")
      (value "APA102-2020")
      (footprint "eagle-import:APA102-2020")
      (libsource (lib "eagle-import") (part "APA102-2020"))
    )
    (comp (ref "U168")
      (value "APA102-2020")
      (footprint "eagle-import:APA102-2020")
      (libsource (lib "eagle-import") (part "APA102-2020"))
    )
    (comp (ref "FD1")
      (value "FIDUCIALUFIDUCIAL")
      (footprint "eagle-import:FIDUCIAL-MICRO")
      (libsource (lib "eagle-import") (part "FIDUCIALUFIDUCIAL"))
    )
    (comp (ref "FD2")
      (value "FIDUCIALUFIDUCIAL")
      (footprint "eagle-import:FIDUCIAL-MICRO")
      (libsource (lib "eagle-import") (part "FIDUCIALUFIDUCIAL"))
    )
    (comp (ref "J2")
      (value "QWIIC_CONNECTORJS-1MM")
      (footprint "eagle-import:1X04_1MM_RA")
      (libsource (lib "eagle-import") (part "QWIIC_CONNECTORJS-1MM"))
    )
    (comp (ref "U1")
      (value "APA102-2020")
      (footprint "eagle-import:APA102-2020")
      (libsource (lib "eagle-import") (part "APA102-2020"))
    )
    (comp (ref "U2")
      (value "APA102-2020")
      (footprint "eagle-import:APA102-2020")
      (libsource (lib "eagle-import") (part "APA102-2020"))
    )
    (comp (ref "U3")
      (value "APA102-2020")
      (footprint "eagle-import:APA102-2020")
      (libsource (lib "eagle-import") (part "APA102-2020"))
    )
    (comp (ref "U4")
      (value "APA102-2020")
      (footprint "eagle-import:APA102-2020")
      (libsource (lib "eagle-import") (part "APA102-2020"))
    )
    (comp (ref "U5")
      (value "APA102-2020")
      (footprint "eagle-import:APA102-2020")
      (libsource (lib "eagle-import") (part "APA102-2020"))
    )
    (comp (ref "U6")
      (value "APA102-2020")
      (footprint "eagle-import:APA102-2020")
      (libsource (lib "eagle-import") (part "APA102-2020"))
    )
    (comp (ref "U7")
      (value "APA102-2020")
      (footprint "eagle-import:APA102-2020")
      (libsource (lib "eagle-import") (part "APA102-2020"))
    )
    (comp (ref "U8")
      (value "APA102-2020")
      (footprint "eagle-import:APA102-2020")
      (libsource (lib "eagle-import") (part "APA102-2020"))
    )
    (comp (ref "U9")
      (value "APA102-2020")
      (footprint "eagle-import:APA102-2020")
      (libsource (lib "eagle-import") (part "APA102-2020"))
    )
    (comp (ref "U10")
      (value "APA102-2020")
      (footprint "eagle-import:APA102-2020")
      (libsource (lib "eagle-import") (part "APA102-2020"))
    )
    (comp (ref "U11")
      (value "APA102-2020")
      (footprint "eagle-import:APA102-2020")
      (libsource (lib "eagle-import") (part "APA102-2020"))
    )
    (comp (ref "U12")
      (value "APA102-2020")
      (footprint "eagle-import:APA102-2020")
      (libsource (lib "eagle-import") (part "APA102-2020"))
    )
    (comp (ref "U13")
      (value "APA102-2020")
      (footprint "eagle-import:APA102-2020")
      (libsource (lib "eagle-import") (part "APA102-2020"))
    )
    (comp (ref "U14")
      (value "APA102-2020")
      (footprint "eagle-import:APA102-2020")
      (libsource (lib "eagle-import") (part "APA102-2020"))
    )
    (comp (ref "U15")
      (value "APA102-2020")
      (footprint "eagle-import:APA102-2020")
      (libsource (lib "eagle-import") (part "APA102-2020"))
    )
    (comp (ref "U16")
      (value "APA102-2020")
      (footprint "eagle-import:APA102-2020")
      (libsource (lib "eagle-import") (part "APA102-2020"))
    )
    (comp (ref "U17")
      (value "APA102-2020")
      (footprint "eagle-import:APA102-2020")
      (libsource (lib "eagle-import") (part "APA102-2020"))
    )
    (comp (ref "U18")
      (value "APA102-2020")
      (footprint "eagle-import:APA102-2020")
      (libsource (lib "eagle-import") (part "APA102-2020"))
    )
    (comp (ref "U19")
      (value "APA102-2020")
      (footprint "eagle-import:APA102-2020")
      (libsource (lib "eagle-import") (part "APA102-2020"))
    )
    (comp (ref "U20")
      (value "APA102-2020")
      (footprint "eagle-import:APA102-2020")
      (libsource (lib "eagle-import") (part "APA102-2020"))
    )
    (comp (ref "U21")
      (value "APA102-2020")
      (footprint "eagle-import:APA102-2020")
      (libsource (lib "eagle-import") (part "APA102-2020"))
    )
    (comp (ref "U22")
      (value "APA102-2020")
      (footprint "eagle-import:APA102-2020")
      (libsource (lib "eagle-import") (part "APA102-2020"))
    )
    (comp (ref "U23")
      (value "APA102-2020")
      (footprint "eagle-import:APA102-2020")
      (libsource (lib "eagle-import") (part "APA102-2020"))
    )
    (comp (ref "U24")
      (value "APA102-2020")
      (footprint "eagle-import:APA102-2020")
      (libsource (lib "eagle-import") (part "APA102-2020"))
    )
    (comp (ref "U25")
      (value "APA102-2020")
      (footprint "eagle-import:APA102-2020")
      (libsource (lib "eagle-import") (part "APA102-2020"))
    )
    (comp (ref "U26")
      (value "APA102-2020")
      (footprint "eagle-import:APA102-2020")
      (libsource (lib "eagle-import") (part "APA102-2020"))
    )
    (comp (ref "U27")
      (value "APA102-2020")
      (footprint "eagle-import:APA102-2020")
      (libsource (lib "eagle-import") (part "APA102-2020"))
    )
    (comp (ref "U28")
      (value "APA102-2020")
      (footprint "eagle-import:APA102-2020")
      (libsource (lib "eagle-import") (part "APA102-2020"))
    )
    (comp (ref "J1")
      (value "QWIIC_CONNECTORJS-1MM")
      (footprint "eagle-import:1X04_1MM_RA")
      (libsource (lib "eagle-import") (part "QWIIC_CONNECTORJS-1MM"))
    )
    (comp (ref "U113")
      (value "APA102-2020")
      (footprint "eagle-import:APA102-2020")
      (libsource (lib "eagle-import") (part "APA102-2020"))
    )
    (comp (ref "U114")
      (value "APA102-2020")
      (footprint "eagle-import:APA102-2020")
      (libsource (lib "eagle-import") (part "APA102-2020"))
    )
    (comp (ref "U115")
      (value "APA102-2020")
      (footprint "eagle-import:APA102-2020")
      (libsource (lib "eagle-import") (part "APA102-2020"))
    )
    (comp (ref "U116")
      (value "APA102-2020")
      (footprint "eagle-import:APA102-2020")
      (libsource (lib "eagle-import") (part "APA102-2020"))
    )
    (comp (ref "U117")
      (value "APA102-2020")
      (footprint "eagle-import:APA102-2020")
      (libsource (lib "eagle-import") (part "APA102-2020"))
    )
    (comp (ref "U118")
      (value "APA102-2020")
      (footprint "eagle-import:APA102-2020")
      (libsource (lib "eagle-import") (part "APA102-2020"))
    )
    (comp (ref "U119")
      (value "APA102-2020")
      (footprint "eagle-import:APA102-2020")
      (libsource (lib "eagle-import") (part "APA102-2020"))
    )
    (comp (ref "U120")
      (value "APA102-2020")
      (footprint "eagle-import:APA102-2020")
      (libsource (lib "eagle-import") (part "APA102-2020"))
    )
    (comp (ref "U121")
      (value "APA102-2020")
      (footprint "eagle-import:APA102-2020")
      (libsource (lib "eagle-import") (part "APA102-2020"))
    )
    (comp (ref "U122")
      (value "APA102-2020")
      (footprint "eagle-import:APA102-2020")
      (libsource (lib "eagle-import") (part "APA102-2020"))
    )
    (comp (ref "U123")
      (value "APA102-2020")
      (footprint "eagle-import:APA102-2020")
      (libsource (lib "eagle-import") (part "APA102-2020"))
    )
    (comp (ref "U124")
      (value "APA102-2020")
      (footprint "eagle-import:APA102-2020")
      (libsource (lib "eagle-import") (part "APA102-2020"))
    )
    (comp (ref "U125")
      (value "APA102-2020")
      (footprint "eagle-import:APA102-2020")
      (libsource (lib "eagle-import") (part "APA102-2020"))
    )
    (comp (ref "U126")
      (value "APA102-2020")
      (footprint "eagle-import:APA102-2020")
      (libsource (lib "eagle-import") (part "APA102-2020"))
    )
    (comp (ref "U127")
      (value "APA102-2020")
      (footprint "eagle-import:APA102-2020")
      (libsource (lib "eagle-import") (part "APA102-2020"))
    )
    (comp (ref "U128")
      (value "APA102-2020")
      (footprint "eagle-import:APA102-2020")
      (libsource (lib "eagle-import") (part "APA102-2020"))
    )
    (comp (ref "U129")
      (value "APA102-2020")
      (footprint "eagle-import:APA102-2020")
      (libsource (lib "eagle-import") (part "APA102-2020"))
    )
    (comp (ref "U130")
      (value "APA102-2020")
      (footprint "eagle-import:APA102-2020")
      (libsource (lib "eagle-import") (part "APA102-2020"))
    )
    (comp (ref "U131")
      (value "APA102-2020")
      (footprint "eagle-import:APA102-2020")
      (libsource (lib "eagle-import") (part "APA102-2020"))
    )
    (comp (ref "U132")
      (value "APA102-2020")
      (footprint "eagle-import:APA102-2020")
      (libsource (lib "eagle-import") (part "APA102-2020"))
    )
    (comp (ref "U133")
      (value "APA102-2020")
      (footprint "eagle-import:APA102-2020")
      (libsource (lib "eagle-import") (part "APA102-2020"))
    )
    (comp (ref "U134")
      (value "APA102-2020")
      (footprint "eagle-import:APA102-2020")
      (libsource (lib "eagle-import") (part "APA102-2020"))
    )
    (comp (ref "U135")
      (value "APA102-2020")
      (footprint "eagle-import:APA102-2020")
      (libsource (lib "eagle-import") (part "APA102-2020"))
    )
    (comp (ref "U136")
      (value "APA102-2020")
      (footprint "eagle-import:APA102-2020")
      (libsource (lib "eagle-import") (part "APA102-2020"))
    )
    (comp (ref "U137")
      (value "APA102-2020")
      (footprint "eagle-import:APA102-2020")
      (libsource (lib "eagle-import") (part "APA102-2020"))
    )
    (comp (ref "U138")
      (value "APA102-2020")
      (footprint "eagle-import:APA102-2020")
      (libsource (lib "eagle-import") (part "APA102-2020"))
    )
    (comp (ref "U139")
      (value "APA102-2020")
      (footprint "eagle-import:APA102-2020")
      (libsource (lib "eagle-import") (part "APA102-2020"))
    )
    (comp (ref "U140")
      (value "APA102-2020")
      (footprint "eagle-import:APA102-2020")
      (libsource (lib "eagle-import") (part "APA102-2020"))
    )
    (comp (ref "U85")
      (value "APA102-2020")
      (footprint "eagle-import:APA102-2020")
      (libsource (lib "eagle-import") (part "APA102-2020"))
    )
    (comp (ref "U86")
      (value "APA102-2020")
      (footprint "eagle-import:APA102-2020")
      (libsource (lib "eagle-import") (part "APA102-2020"))
    )
    (comp (ref "U87")
      (value "APA102-2020")
      (footprint "eagle-import:APA102-2020")
      (libsource (lib "eagle-import") (part "APA102-2020"))
    )
    (comp (ref "U88")
      (value "APA102-2020")
      (footprint "eagle-import:APA102-2020")
      (libsource (lib "eagle-import") (part "APA102-2020"))
    )
    (comp (ref "U89")
      (value "APA102-2020")
      (footprint "eagle-import:APA102-2020")
      (libsource (lib "eagle-import") (part "APA102-2020"))
    )
    (comp (ref "U90")
      (value "APA102-2020")
      (footprint "eagle-import:APA102-2020")
      (libsource (lib "eagle-import") (part "APA102-2020"))
    )
    (comp (ref "U91")
      (value "APA102-2020")
      (footprint "eagle-import:APA102-2020")
      (libsource (lib "eagle-import") (part "APA102-2020"))
    )
    (comp (ref "U92")
      (value "APA102-2020")
      (footprint "eagle-import:APA102-2020")
      (libsource (lib "eagle-import") (part "APA102-2020"))
    )
    (comp (ref "U93")
      (value "APA102-2020")
      (footprint "eagle-import:APA102-2020")
      (libsource (lib "eagle-import") (part "APA102-2020"))
    )
    (comp (ref "U94")
      (value "APA102-2020")
      (footprint "eagle-import:APA102-2020")
      (libsource (lib "eagle-import") (part "APA102-2020"))
    )
    (comp (ref "U95")
      (value "APA102-2020")
      (footprint "eagle-import:APA102-2020")
      (libsource (lib "eagle-import") (part "APA102-2020"))
    )
    (comp (ref "U96")
      (value "APA102-2020")
      (footprint "eagle-import:APA102-2020")
      (libsource (lib "eagle-import") (part "APA102-2020"))
    )
    (comp (ref "U97")
      (value "APA102-2020")
      (footprint "eagle-import:APA102-2020")
      (libsource (lib "eagle-import") (part "APA102-2020"))
    )
    (comp (ref "U98")
      (value "APA102-2020")
      (footprint "eagle-import:APA102-2020")
      (libsource (lib "eagle-import") (part "APA102-2020"))
    )
    (comp (ref "U99")
      (value "APA102-2020")
      (footprint "eagle-import:APA102-2020")
      (libsource (lib "eagle-import") (part "APA102-2020"))
    )
    (comp (ref "U100")
      (value "APA102-2020")
      (footprint "eagle-import:APA102-2020")
      (libsource (lib "eagle-import") (part "APA102-2020"))
    )
    (comp (ref "U101")
      (value "APA102-2020")
      (footprint "eagle-import:APA102-2020")
      (libsource (lib "eagle-import") (part "APA102-2020"))
    )
    (comp (ref "U102")
      (value "APA102-2020")
      (footprint "eagle-import:APA102-2020")
      (libsource (lib "eagle-import") (part "APA102-2020"))
    )
    (comp (ref "U103")
      (value "APA102-2020")
      (footprint "eagle-import:APA102-2020")
      (libsource (lib "eagle-import") (part "APA102-2020"))
    )
    (comp (ref "U104")
      (value "APA102-2020")
      (footprint "eagle-import:APA102-2020")
      (libsource (lib "eagle-import") (part "APA102-2020"))
    )
    (comp (ref "U105")
      (value "APA102-2020")
      (footprint "eagle-import:APA102-2020")
      (libsource (lib "eagle-import") (part "APA102-2020"))
    )
    (comp (ref "U106")
      (value "APA102-2020")
      (footprint "eagle-import:APA102-2020")
      (libsource (lib "eagle-import") (part "APA102-2020"))
    )
    (comp (ref "U107")
      (value "APA102-2020")
      (footprint "eagle-import:APA102-2020")
      (libsource (lib "eagle-import") (part "APA102-2020"))
    )
    (comp (ref "U108")
      (value "APA102-2020")
      (footprint "eagle-import:APA102-2020")
      (libsource (lib "eagle-import") (part "APA102-2020"))
    )
    (comp (ref "U109")
      (value "APA102-2020")
      (footprint "eagle-import:APA102-2020")
      (libsource (lib "eagle-import") (part "APA102-2020"))
    )
    (comp (ref "U110")
      (value "APA102-2020")
      (footprint "eagle-import:APA102-2020")
      (libsource (lib "eagle-import") (part "APA102-2020"))
    )
    (comp (ref "U111")
      (value "APA102-2020")
      (footprint "eagle-import:APA102-2020")
      (libsource (lib "eagle-import") (part "APA102-2020"))
    )
    (comp (ref "U112")
      (value "APA102-2020")
      (footprint "eagle-import:APA102-2020")
      (libsource (lib "eagle-import") (part "APA102-2020"))
    )
    (comp (ref "U57")
      (value "APA102-2020")
      (footprint "eagle-import:APA102-2020")
      (libsource (lib "eagle-import") (part "APA102-2020"))
    )
    (comp (ref "U58")
      (value "APA102-2020")
      (footprint "eagle-import:APA102-2020")
      (libsource (lib "eagle-import") (part "APA102-2020"))
    )
    (comp (ref "U59")
      (value "APA102-2020")
      (footprint "eagle-import:APA102-2020")
      (libsource (lib "eagle-import") (part "APA102-2020"))
    )
    (comp (ref "U60")
      (value "APA102-2020")
      (footprint "eagle-import:APA102-2020")
      (libsource (lib "eagle-import") (part "APA102-2020"))
    )
    (comp (ref "U61")
      (value "APA102-2020")
      (footprint "eagle-import:APA102-2020")
      (libsource (lib "eagle-import") (part "APA102-2020"))
    )
    (comp (ref "U62")
      (value "APA102-2020")
      (footprint "eagle-import:APA102-2020")
      (libsource (lib "eagle-import") (part "APA102-2020"))
    )
    (comp (ref "U63")
      (value "APA102-2020")
      (footprint "eagle-import:APA102-2020")
      (libsource (lib "eagle-import") (part "APA102-2020"))
    )
    (comp (ref "U64")
      (value "APA102-2020")
      (footprint "eagle-import:APA102-2020")
      (libsource (lib "eagle-import") (part "APA102-2020"))
    )
    (comp (ref "U65")
      (value "APA102-2020")
      (footprint "eagle-import:APA102-2020")
      (libsource (lib "eagle-import") (part "APA102-2020"))
    )
    (comp (ref "U66")
      (value "APA102-2020")
      (footprint "eagle-import:APA102-2020")
      (libsource (lib "eagle-import") (part "APA102-2020"))
    )
    (comp (ref "U67")
      (value "APA102-2020")
      (footprint "eagle-import:APA102-2020")
      (libsource (lib "eagle-import") (part "APA102-2020"))
    )
    (comp (ref "U68")
      (value "APA102-2020")
      (footprint "eagle-import:APA102-2020")
      (libsource (lib "eagle-import") (part "APA102-2020"))
    )
    (comp (ref "U69")
      (value "APA102-2020")
      (footprint "eagle-import:APA102-2020")
      (libsource (lib "eagle-import") (part "APA102-2020"))
    )
    (comp (ref "U70")
      (value "APA102-2020")
      (footprint "eagle-import:APA102-2020")
      (libsource (lib "eagle-import") (part "APA102-2020"))
    )
    (comp (ref "U71")
      (value "APA102-2020")
      (footprint "eagle-import:APA102-2020")
      (libsource (lib "eagle-import") (part "APA102-2020"))
    )
    (comp (ref "U72")
      (value "APA102-2020")
      (footprint "eagle-import:APA102-2020")
      (libsource (lib "eagle-import") (part "APA102-2020"))
    )
    (comp (ref "U73")
      (value "APA102-2020")
      (footprint "eagle-import:APA102-2020")
      (libsource (lib "eagle-import") (part "APA102-2020"))
    )
    (comp (ref "U74")
      (value "APA102-2020")
      (footprint "eagle-import:APA102-2020")
      (libsource (lib "eagle-import") (part "APA102-2020"))
    )
    (comp (ref "U75")
      (value "APA102-2020")
      (footprint "eagle-import:APA102-2020")
      (libsource (lib "eagle-import") (part "APA102-2020"))
    )
    (comp (ref "U76")
      (value "APA102-2020")
      (footprint "eagle-import:APA102-2020")
      (libsource (lib "eagle-import") (part "APA102-2020"))
    )
    (comp (ref "U77")
      (value "APA102-2020")
      (footprint "eagle-import:APA102-2020")
      (libsource (lib "eagle-import") (part "APA102-2020"))
    )
    (comp (ref "U78")
      (value "APA102-2020")
      (footprint "eagle-import:APA102-2020")
      (libsource (lib "eagle-import") (part "APA102-2020"))
    )
    (comp (ref "U79")
      (value "APA102-2020")
      (footprint "eagle-import:APA102-2020")
      (libsource (lib "eagle-import") (part "APA102-2020"))
    )
    (comp (ref "U80")
      (value "APA102-2020")
      (footprint "eagle-import:APA102-2020")
      (libsource (lib "eagle-import") (part "APA102-2020"))
    )
    (comp (ref "U81")
      (value "APA102-2020")
      (footprint "eagle-import:APA102-2020")
      (libsource (lib "eagle-import") (part "APA102-2020"))
    )
    (comp (ref "U82")
      (value "APA102-2020")
      (footprint "eagle-import:APA102-2020")
      (libsource (lib "eagle-import") (part "APA102-2020"))
    )
    (comp (ref "U83")
      (value "APA102-2020")
      (footprint "eagle-import:APA102-2020")
      (libsource (lib "eagle-import") (part "APA102-2020"))
    )
    (comp (ref "U84")
      (value "APA102-2020")
      (footprint "eagle-import:APA102-2020")
      (libsource (lib "eagle-import") (part "APA102-2020"))
    )
  )
  (nets
    (net (code "1") (name "CK1") (class "Default")
      (node (ref "U28") (pin "CKO") (pinfunction "CO_CKO") (pintype "bidirectional"))
      (node (ref "U29") (pin "CKI") (pinfunction "CI_CKI") (pintype "bidirectional"))
    )
    (net (code "2") (name "CK2") (class "Default")
      (node (ref "U56") (pin "CKO") (pinfunction "CO_CKO") (pintype "bidirectional"))
      (node (ref "U57") (pin "CKI") (pinfunction "CI_CKI") (pintype "bidirectional"))
    )
    (net (code "3") (name "CK3") (class "Default")
      (node (ref "U84") (pin "CKO") (pinfunction "CO_CKO") (pintype "bidirectional"))
      (node (ref "U85") (pin "CKI") (pinfunction "CI_CKI") (pintype "bidirectional"))
    )
    (net (code "4") (name "CK4") (class "Default")
      (node (ref "U112") (pin "CKO") (pinfunction "CO_CKO") (pintype "bidirectional"))
      (node (ref "U113") (pin "CKI") (pinfunction "CI_CKI") (pintype "bidirectional"))
    )
    (net (code "5") (name "CK5") (class "Default")
      (node (ref "U140") (pin "CKO") (pinfunction "CO_CKO") (pintype "bidirectional"))
      (node (ref "U141") (pin "CKI") (pinfunction "CI_CKI") (pintype "bidirectional"))
    )
    (net (code "6") (name "CK6") (class "Default")
      (node (ref "U168") (pin "CKO") (pinfunction "CO_CKO") (pintype "bidirectional"))
      (node (ref "U169") (pin "CKI") (pinfunction "CI_CKI") (pintype "bidirectional"))
    )
    (net (code "7") (name "CK7") (class "Default")
      (node (ref "U196") (pin "CKO") (pinfunction "CO_CKO") (pintype "bidirectional"))
      (node (ref "U197") (pin "CKI") (pinfunction "CI_CKI") (pintype "bidirectional"))
    )
    (net (code "8") (name "CK8") (class "Default")
      (node (ref "U224") (pin "CKO") (pinfunction "CO_CKO") (pintype "bidirectional"))
      (node (ref "U225") (pin "CKI") (pinfunction "CI_CKI") (pintype "bidirectional"))
    )
    (net (code "9") (name "GND") (class "Default")
      (node (ref "J1") (pin "1") (pinfunction "1_1") (pintype "power_in"))
      (node (ref "J2") (pin "1") (pinfunction "1_1") (pintype "power_in"))
      (node (ref "U1") (pin "GND") (pinfunction "GND_GND") (pintype "bidirectional"))
      (node (ref "U10") (pin "GND") (pinfunction "GND_GND") (pintype "bidirectional"))
      (node (ref "U100") (pin "GND") (pinfunction "GND_GND") (pintype "bidirectional"))
      (node (ref "U101") (pin "GND") (pinfunction "GND_GND") (pintype "bidirectional"))
      (node (ref "U102") (pin "GND") (pinfunction "GND_GND") (pintype "bidirectional"))
      (node (ref "U103") (pin "GND") (pinfunction "GND_GND") (pintype "bidirectional"))
      (node (ref "U104") (pin "GND") (pinfunction "GND_GND") (pintype "bidirectional"))
      (node (ref "U105") (pin "GND") (pinfunction "GND_GND") (pintype "bidirectional"))
      (node (ref "U106") (pin "GND") (pinfunction "GND_GND") (pintype "bidirectional"))
      (node (ref "U107") (pin "GND") (pinfunction "GND_GND") (pintype "bidirectional"))
      (node (ref "U108") (pin "GND") (pinfunction "GND_GND") (pintype "bidirectional"))
      (node (ref "U109") (pin "GND") (pinfunction "GND_GND") (pintype "bidirectional"))
      (node (ref "U11") (pin "GND") (pinfunction "GND_GND") (pintype "bidirectional"))
      (node (ref "U110") (pin "GND") (pinfunction "GND_GND") (pintype "bidirectional"))
      (node (ref "U111") (pin "GND") (pinfunction "GND_GND") (pintype "bidirectional"))
      (node (ref "U112") (pin "GND") (pinfunction "GND_GND") (pintype "bidirectional"))
      (node (ref "U113") (pin "GND") (pinfunction "GND_GND") (pintype "bidirectional"))
      (node (ref "U114") (pin "GND") (pinfunction "GND_GND") (pintype "bidirectional"))
      (node (ref "U115") (pin "GND") (pinfunction "GND_GND") (pintype "bidirectional"))
      (node (ref "U116") (pin "GND") (pinfunction "GND_GND") (pintype "bidirectional"))
      (node (ref "U117") (pin "GND") (pinfunction "GND_GND") (pintype "bidirectional"))
      (node (ref "U118") (pin "GND") (pinfunction "GND_GND") (pintype "bidirectional"))
      (node (ref "U119") (pin "GND") (pinfunction "GND_GND") (pintype "bidirectional"))
      (node (ref "U12") (pin "GND") (pinfunction "GND_GND") (pintype "bidirectional"))
      (node (ref "U120") (pin "GND") (pinfunction "GND_GND") (pintype "bidirectional"))
      (node (ref "U121") (pin "GND") (pinfunction "GND_GND") (pintype "bidirectional"))
      (node (ref "U122") (pin "GND") (pinfunction "GND_GND") (pintype "bidirectional"))
      (node (ref "U123") (pin "GND") (pinfunction "GND_GND") (pintype "bidirectional"))
      (node (ref "U124") (pin "GND") (pinfunction "GND_GND") (pintype "bidirectional"))
      (node (ref "U125") (pin "GND") (pinfunction "GND_GND") (pintype "bidirectional"))
      (node (ref "U126") (pin "GND") (pinfunction "GND_GND") (pintype "bidirectional"))
      (node (ref "U127") (pin "GND") (pinfunction "GND_GND") (pintype "bidirectional"))
      (node (ref "U128") (pin "GND") (pinfunction "GND_GND") (pintype "bidirectional"))
      (node (ref "U129") (pin "GND") (pinfunction "GND_GND") (pintype "bidirectional"))
      (node (ref "U13") (pin "GND") (pinfunction "GND_GND") (pintype "bidirectional"))
      (node (ref "U130") (pin "GND") (pinfunction "GND_GND") (pintype "bidirectional"))
      (node (ref "U131") (pin "GND") (pinfunction "GND_GND") (pintype "bidirectional"))
      (node (ref "U132") (pin "GND") (pinfunction "GND_GND") (pintype "bidirectional"))
      (node (ref "U133") (pin "GND") (pinfunction "GND_GND") (pintype "bidirectional"))
      (node (ref "U134") (pin "GND") (pinfunction "GND_GND") (pintype "bidirectional"))
      (node (ref "U135") (pin "GND") (pinfunction "GND_GND") (pintype "bidirectional"))
      (node (ref "U136") (pin "GND") (pinfunction "GND_GND") (pintype "bidirectional"))
      (node (ref "U137") (pin "GND") (pinfunction "GND_GND") (pintype "bidirectional"))
      (node (ref "U138") (pin "GND") (pinfunction "GND_GND") (pintype "bidirectional"))
      (node (ref "U139") (pin "GND") (pinfunction "GND_GND") (pintype "bidirectional"))
      (node (ref "U14") (pin "GND") (pinfunction "GND_GND") (pintype "bidirectional"))
      (node (ref "U140") (pin "GND") (pinfunction "GND_GND") (pintype "bidirectional"))
      (node (ref "U141") (pin "GND") (pinfunction "GND_GND") (pintype "bidirectional"))
      (node (ref "U142") (pin "GND") (pinfunction "GND_GND") (pintype "bidirectional"))
      (node (ref "U143") (pin "GND") (pinfunction "GND_GND") (pintype "bidirectional"))
      (node (ref "U144") (pin "GND") (pinfunction "GND_GND") (pintype "bidirectional"))
      (node (ref "U145") (pin "GND") (pinfunction "GND_GND") (pintype "bidirectional"))
      (node (ref "U146") (pin "GND") (pinfunction "GND_GND") (pintype "bidirectional"))
      (node (ref "U147") (pin "GND") (pinfunction "GND_GND") (pintype "bidirectional"))
      (node (ref "U148") (pin "GND") (pinfunction "GND_GND") (pintype "bidirectional"))
      (node (ref "U149") (pin "GND") (pinfunction "GND_GND") (pintype "bidirectional"))
      (node (ref "U15") (pin "GND") (pinfunction "GND_GND") (pintype "bidirectional"))
      (node (ref "U150") (pin "GND") (pinfunction "GND_GND") (pintype "bidirectional"))
      (node (ref "U151") (pin "GND") (pinfunction "GND_GND") (pintype "bidirectional"))
      (node (ref "U152") (pin "GND") (pinfunction "GND_GND") (pintype "bidirectional"))
      (node (ref "U153") (pin "GND") (pinfunction "GND_GND") (pintype "bidirectional"))
      (node (ref "U154") (pin "GND") (pinfunction "GND_GND") (pintype "bidirectional"))
      (node (ref "U155") (pin "GND") (pinfunction "GND_GND") (pintype "bidirectional"))
      (node (ref "U156") (pin "GND") (pinfunction "GND_GND") (pintype "bidirectional"))
      (node (ref "U157") (pin "GND") (pinfunction "GND_GND") (pintype "bidirectional"))
      (node (ref "U158") (pin "GND") (pinfunction "GND_GND") (pintype "bidirectional"))
      (node (ref "U159") (pin "GND") (pinfunction "GND_GND") (pintype "bidirectional"))
      (node (ref "U16") (pin "GND") (pinfunction "GND_GND") (pintype "bidirectional"))
      (node (ref "U160") (pin "GND") (pinfunction "GND_GND") (pintype "bidirectional"))
      (node (ref "U161") (pin "GND") (pinfunction "GND_GND") (pintype "bidirectional"))
      (node (ref "U162") (pin "GND") (pinfunction "GND_GND") (pintype "bidirectional"))
      (node (ref "U163") (pin "GND") (pinfunction "GND_GND") (pintype "bidirectional"))
      (node (ref "U164") (pin "GND") (pinfunction "GND_GND") (pintype "bidirectional"))
      (node (ref "U165") (pin "GND") (pinfunction "GND_GND") (pintype "bidirectional"))
      (node (ref "U166") (pin "GND") (pinfunction "GND_GND") (pintype "bidirectional"))
      (node (ref "U167") (pin "GND") (pinfunction "GND_GND") (pintype "bidirectional"))
      (node (ref "U168") (pin "GND") (pinfunction "GND_GND") (pintype "bidirectional"))
      (node (ref "U169") (pin "GND") (pinfunction "GND_GND") (pintype "bidirectional"))
      (node (ref "U17") (pin "GND") (pinfunction "GND_GND") (pintype "bidirectional"))
      (node (ref "U170") (pin "GND") (pinfunction "GND_GND") (pintype "bidirectional"))
      (node (ref "U171") (pin "GND") (pinfunction "GND_GND") (pintype "bidirectional"))
      (node (ref "U172") (pin "GND") (pinfunction "GND_GND") (pintype "bidirectional"))
      (node (ref "U173") (pin "GND") (pinfunction "GND_GND") (pintype "bidirectional"))
      (node (ref "U174") (pin "GND") (pinfunction "GND_GND") (pintype "bidirectional"))
      (node (ref "U175") (pin "GND") (pinfunction "GND_GND") (pintype "bidirectional"))
      (node (ref "U176") (pin "GND") (pinfunction "GND_GND") (pintype "bidirectional"))
      (node (ref "U177") (pin "GND") (pinfunction "GND_GND") (pintype "bidirectional"))
      (node (ref "U178") (pin "GND") (pinfunction "GND_GND") (pintype "bidirectional"))
      (node (ref "U179") (pin "GND") (pinfunction "GND_GND") (pintype "bidirectional"))
      (node (ref "U18") (pin "GND") (pinfunction "GND_GND") (pintype "bidirectional"))
      (node (ref "U180") (pin "GND") (pinfunction "GND_GND") (pintype "bidirectional"))
      (node (ref "U181") (pin "GND") (pinfunction "GND_GND") (pintype "bidirectional"))
      (node (ref "U182") (pin "GND") (pinfunction "GND_GND") (pintype "bidirectional"))
      (node (ref "U183") (pin "GND") (pinfunction "GND_GND") (pintype "bidirectional"))
      (node (ref "U184") (pin "GND") (pinfunction "GND_GND") (pintype "bidirectional"))
      (node (ref "U185") (pin "GND") (pinfunction "GND_GND") (pintype "bidirectional"))
      (node (ref "U186") (pin "GND") (pinfunction "GND_GND") (pintype "bidirectional"))
      (node (ref "U187") (pin "GND") (pinfunction "GND_GND") (pintype "bidirectional"))
      (node (ref "U188") (pin "GND") (pinfunction "GND_GND") (pintype "bidirectional"))
      (node (ref "U189") (pin "GND") (pinfunction "GND_GND") (pintype "bidirectional"))
      (node (ref "U19") (pin "GND") (pinfunction "GND_GND") (pintype "bidirectional"))
      (node (ref "U190") (pin "GND") (pinfunction "GND_GND") (pintype "bidirectional"))
      (node (ref "U191") (pin "GND") (pinfunction "GND_GND") (pintype "bidirectional"))
      (node (ref "U192") (pin "GND") (pinfunction "GND_GND") (pintype "bidirectional"))
      (node (ref "U193") (pin "GND") (pinfunction "GND_GND") (pintype "bidirectional"))
      (node (ref "U194") (pin "GND") (pinfunction "GND_GND") (pintype "bidirectional"))
      (node (ref "U195") (pin "GND") (pinfunction "GND_GND") (pintype "bidirectional"))
      (node (ref "U196") (pin "GND") (pinfunction "GND_GND") (pintype "bidirectional"))
      (node (ref "U197") (pin "GND") (pinfunction "GND_GND") (pintype "bidirectional"))
      (node (ref "U198") (pin "GND") (pinfunction "GND_GND") (pintype "bidirectional"))
      (node (ref "U199") (pin "GND") (pinfunction "GND_GND") (pintype "bidirectional"))
      (node (ref "U2") (pin "GND") (pinfunction "GND_GND") (pintype "bidirectional"))
      (node (ref "U20") (pin "GND") (pinfunction "GND_GND") (pintype "bidirectional"))
      (node (ref "U200") (pin "GND") (pinfunction "GND_GND") (pintype "bidirectional"))
      (node (ref "U201") (pin "GND") (pinfunction "GND_GND") (pintype "bidirectional"))
      (node (ref "U202") (pin "GND") (pinfunction "GND_GND") (pintype "bidirectional"))
      (node (ref "U203") (pin "GND") (pinfunction "GND_GND") (pintype "bidirectional"))
      (node (ref "U204") (pin "GND") (pinfunction "GND_GND") (pintype "bidirectional"))
      (node (ref "U205") (pin "GND") (pinfunction "GND_GND") (pintype "bidirectional"))
      (node (ref "U206") (pin "GND") (pinfunction "GND_GND") (pintype "bidirectional"))
      (node (ref "U207") (pin "GND") (pinfunction "GND_GND") (pintype "bidirectional"))
      (node (ref "U208") (pin "GND") (pinfunction "GND_GND") (pintype "bidirectional"))
      (node (ref "U209") (pin "GND") (pinfunction "GND_GND") (pintype "bidirectional"))
      (node (ref "U21") (pin "GND") (pinfunction "GND_GND") (pintype "bidirectional"))
      (node (ref "U210") (pin "GND") (pinfunction "GND_GND") (pintype "bidirectional"))
      (node (ref "U211") (pin "GND") (pinfunction "GND_GND") (pintype "bidirectional"))
      (node (ref "U212") (pin "GND") (pinfunction "GND_GND") (pintype "bidirectional"))
      (node (ref "U213") (pin "GND") (pinfunction "GND_GND") (pintype "bidirectional"))
      (node (ref "U214") (pin "GND") (pinfunction "GND_GND") (pintype "bidirectional"))
      (node (ref "U215") (pin "GND") (pinfunction "GND_GND") (pintype "bidirectional"))
      (node (ref "U216") (pin "GND") (pinfunction "GND_GND") (pintype "bidirectional"))
      (node (ref "U217") (pin "GND") (pinfunction "GND_GND") (pintype "bidirectional"))
      (node (ref "U218") (pin "GND") (pinfunction "GND_GND") (pintype "bidirectional"))
      (node (ref "U219") (pin "GND") (pinfunction "GND_GND") (pintype "bidirectional"))
      (node (ref "U22") (pin "GND") (pinfunction "GND_GND") (pintype "bidirectional"))
      (node (ref "U220") (pin "GND") (pinfunction "GND_GND") (pintype "bidirectional"))
      (node (ref "U221") (pin "GND") (pinfunction "GND_GND") (pintype "bidirectional"))
      (node (ref "U222") (pin "GND") (pinfunction "GND_GND") (pintype "bidirectional"))
      (node (ref "U223") (pin "GND") (pinfunction "GND_GND") (pintype "bidirectional"))
      (node (ref "U224") (pin "GND") (pinfunction "GND_GND") (pintype "bidirectional"))
      (node (ref "U225") (pin "GND") (pinfunction "GND_GND") (pintype "bidirectional"))
      (node (ref "U226") (pin "GND") (pinfunction "GND_GND") (pintype "bidirectional"))
      (node (ref "U227") (pin "GND") (pinfunction "GND_GND") (pintype "bidirectional"))
      (node (ref "U228") (pin "GND") (pinfunction "GND_GND") (pintype "bidirectional"))
      (node (ref "U229") (pin "GND") (pinfunction "GND_GND") (pintype "bidirectional"))
      (node (ref "U23") (pin "GND") (pinfunction "GND_GND") (pintype "bidirectional"))
      (node (ref "U230") (pin "GND") (pinfunction "GND_GND") (pintype "bidirectional"))
      (node (ref "U231") (pin "GND") (pinfunction "GND_GND") (pintype "bidirectional"))
      (node (ref "U232") (pin "GND") (pinfunction "GND_GND") (pintype "bidirectional"))
      (node (ref "U233") (pin "GND") (pinfunction "GND_GND") (pintype "bidirectional"))
      (node (ref "U234") (pin "GND") (pinfunction "GND_GND") (pintype "bidirectional"))
      (node (ref "U235") (pin "GND") (pinfunction "GND_GND") (pintype "bidirectional"))
      (node (ref "U236") (pin "GND") (pinfunction "GND_GND") (pintype "bidirectional"))
      (node (ref "U237") (pin "GND") (pinfunction "GND_GND") (pintype "bidirectional"))
      (node (ref "U238") (pin "GND") (pinfunction "GND_GND") (pintype "bidirectional"))
      (node (ref "U239") (pin "GND") (pinfunction "GND_GND") (pintype "bidirectional"))
      (node (ref "U24") (pin "GND") (pinfunction "GND_GND") (pintype "bidirectional"))
      (node (ref "U240") (pin "GND") (pinfunction "GND_GND") (pintype "bidirectional"))
      (node (ref "U241") (pin "GND") (pinfunction "GND_GND") (pintype "bidirectional"))
      (node (ref "U242") (pin "GND") (pinfunction "GND_GND") (pintype "bidirectional"))
      (node (ref "U243") (pin "GND") (pinfunction "GND_GND") (pintype "bidirectional"))
      (node (ref "U244") (pin "GND") (pinfunction "GND_GND") (pintype "bidirectional"))
      (node (ref "U245") (pin "GND") (pinfunction "GND_GND") (pintype "bidirectional"))
      (node (ref "U246") (pin "GND") (pinfunction "GND_GND") (pintype "bidirectional"))
      (node (ref "U247") (pin "GND") (pinfunction "GND_GND") (pintype "bidirectional"))
      (node (ref "U248") (pin "GND") (pinfunction "GND_GND") (pintype "bidirectional"))
      (node (ref "U249") (pin "GND") (pinfunction "GND_GND") (pintype "bidirectional"))
      (node (ref "U25") (pin "GND") (pinfunction "GND_GND") (pintype "bidirectional"))
      (node (ref "U250") (pin "GND") (pinfunction "GND_GND") (pintype "bidirectional"))
      (node (ref "U251") (pin "GND") (pinfunction "GND_GND") (pintype "bidirectional"))
      (node (ref "U252") (pin "GND") (pinfunction "GND_GND") (pintype "bidirectional"))
      (node (ref "U26") (pin "GND") (pinfunction "GND_GND") (pintype "bidirectional"))
      (node (ref "U27") (pin "GND") (pinfunction "GND_GND") (pintype "bidirectional"))
      (node (ref "U28") (pin "GND") (pinfunction "GND_GND") (pintype "bidirectional"))
      (node (ref "U29") (pin "GND") (pinfunction "GND_GND") (pintype "bidirectional"))
      (node (ref "U3") (pin "GND") (pinfunction "GND_GND") (pintype "bidirectional"))
      (node (ref "U30") (pin "GND") (pinfunction "GND_GND") (pintype "bidirectional"))
      (node (ref "U31") (pin "GND") (pinfunction "GND_GND") (pintype "bidirectional"))
      (node (ref "U32") (pin "GND") (pinfunction "GND_GND") (pintype "bidirectional"))
      (node (ref "U33") (pin "GND") (pinfunction "GND_GND") (pintype "bidirectional"))
      (node (ref "U34") (pin "GND") (pinfunction "GND_GND") (pintype "bidirectional"))
      (node (ref "U35") (pin "GND") (pinfunction "GND_GND") (pintype "bidirectional"))
      (node (ref "U36") (pin "GND") (pinfunction "GND_GND") (pintype "bidirectional"))
      (node (ref "U37") (pin "GND") (pinfunction "GND_GND") (pintype "bidirectional"))
      (node (ref "U38") (pin "GND") (pinfunction "GND_GND") (pintype "bidirectional"))
      (node (ref "U39") (pin "GND") (pinfunction "GND_GND") (pintype "bidirectional"))
      (node (ref "U4") (pin "GND") (pinfunction "GND_GND") (pintype "bidirectional"))
      (node (ref "U40") (pin "GND") (pinfunction "GND_GND") (pintype "bidirectional"))
      (node (ref "U41") (pin "GND") (pinfunction "GND_GND") (pintype "bidirectional"))
      (node (ref "U42") (pin "GND") (pinfunction "GND_GND") (pintype "bidirectional"))
      (node (ref "U43") (pin "GND") (pinfunction "GND_GND") (pintype "bidirectional"))
      (node (ref "U44") (pin "GND") (pinfunction "GND_GND") (pintype "bidirectional"))
      (node (ref "U45") (pin "GND") (pinfunction "GND_GND") (pintype "bidirectional"))
      (node (ref "U46") (pin "GND") (pinfunction "GND_GND") (pintype "bidirectional"))
      (node (ref "U47") (pin "GND") (pinfunction "GND_GND") (pintype "bidirectional"))
      (node (ref "U48") (pin "GND") (pinfunction "GND_GND") (pintype "bidirectional"))
      (node (ref "U49") (pin "GND") (pinfunction "GND_GND") (pintype "bidirectional"))
      (node (ref "U5") (pin "GND") (pinfunction "GND_GND") (pintype "bidirectional"))
      (node (ref "U50") (pin "GND") (pinfunction "GND_GND") (pintype "bidirectional"))
      (node (ref "U51") (pin "GND") (pinfunction "GND_GND") (pintype "bidirectional"))
      (node (ref "U52") (pin "GND") (pinfunction "GND_GND") (pintype "bidirectional"))
      (node (ref "U53") (pin "GND") (pinfunction "GND_GND") (pintype "bidirectional"))
      (node (ref "U54") (pin "GND") (pinfunction "GND_GND") (pintype "bidirectional"))
      (node (ref "U55") (pin "GND") (pinfunction "GND_GND") (pintype "bidirectional"))
      (node (ref "U56") (pin "GND") (pinfunction "GND_GND") (pintype "bidirectional"))
      (node (ref "U57") (pin "GND") (pinfunction "GND_GND") (pintype "bidirectional"))
      (node (ref "U58") (pin "GND") (pinfunction "GND_GND") (pintype "bidirectional"))
      (node (ref "U59") (pin "GND") (pinfunction "GND_GND") (pintype "bidirectional"))
      (node (ref "U6") (pin "GND") (pinfunction "GND_GND") (pintype "bidirectional"))
      (node (ref "U60") (pin "GND") (pinfunction "GND_GND") (pintype "bidirectional"))
      (node (ref "U61") (pin "GND") (pinfunction "GND_GND") (pintype "bidirectional"))
      (node (ref "U62") (pin "GND") (pinfunction "GND_GND") (pintype "bidirectional"))
      (node (ref "U63") (pin "GND") (pinfunction "GND_GND") (pintype "bidirectional"))
      (node (ref "U64") (pin "GND") (pinfunction "GND_GND") (pintype "bidirectional"))
      (node (ref "U65") (pin "GND") (pinfunction "GND_GND") (pintype "bidirectional"))
      (node (ref "U66") (pin "GND") (pinfunction "GND_GND") (pintype "bidirectional"))
      (node (ref "U67") (pin "GND") (pinfunction "GND_GND") (pintype "bidirectional"))
      (node (ref "U68") (pin "GND") (pinfunction "GND_GND") (pintype "bidirectional"))
      (node (ref "U69") (pin "GND") (pinfunction "GND_GND") (pintype "bidirectional"))
      (node (ref "U7") (pin "GND") (pinfunction "GND_GND") (pintype "bidirectional"))
      (node (ref "U70") (pin "GND") (pinfunction "GND_GND") (pintype "bidirectional"))
      (node (ref "U71") (pin "GND") (pinfunction "GND_GND") (pintype "bidirectional"))
      (node (ref "U72") (pin "GND") (pinfunction "GND_GND") (pintype "bidirectional"))
      (node (ref "U73") (pin "GND") (pinfunction "GND_GND") (pintype "bidirectional"))
      (node (ref "U74") (pin "GND") (pinfunction "GND_GND") (pintype "bidirectional"))
      (node (ref "U75") (pin "GND") (pinfunction "GND_GND") (pintype "bidirectional"))
      (node (ref "U76") (pin "GND") (pinfunction "GND_GND") (pintype "bidirectional"))
      (node (ref "U77") (pin "GND") (pinfunction "GND_GND") (pintype "bidirectional"))
      (node (ref "U78") (pin "GND") (pinfunction "GND_GND") (pintype "bidirectional"))
      (node (ref "U79") (pin "GND") (pinfunction "GND_GND") (pintype "bidirectional"))
      (node (ref "U8") (pin "GND") (pinfunction "GND_GND") (pintype "bidirectional"))
      (node (ref "U80") (pin "GND") (pinfunction "GND_GND") (pintype "bidirectional"))
      (node (ref "U81") (pin "GND") (pinfunction "GND_GND") (pintype "bidirectional"))
      (node (ref "U82") (pin "GND") (pinfunction "GND_GND") (pintype "bidirectional"))
      (node (ref "U83") (pin "GND") (pinfunction "GND_GND") (pintype "bidirectional"))
      (node (ref "U84") (pin "GND") (pinfunction "GND_GND") (pintype "bidirectional"))
      (node (ref "U85") (pin "GND") (pinfunction "GND_GND") (pintype "bidirectional"))
      (node (ref "U86") (pin "GND") (pinfunction "GND_GND") (pintype "bidirectional"))
      (node (ref "U87") (pin "GND") (pinfunction "GND_GND") (pintype "bidirectional"))
      (node (ref "U88") (pin "GND") (pinfunction "GND_GND") (pintype "bidirectional"))
      (node (ref "U89") (pin "GND") (pinfunction "GND_GND") (pintype "bidirectional"))
      (node (ref "U9") (pin "GND") (pinfunction "GND_GND") (pintype "bidirectional"))
      (node (ref "U90") (pin "GND") (pinfunction "GND_GND") (pintype "bidirectional"))
      (node (ref "U91") (pin "GND") (pinfunction "GND_GND") (pintype "bidirectional"))
      (node (ref "U92") (pin "GND") (pinfunction "GND_GND") (pintype "bidirectional"))
      (node (ref "U93") (pin "GND") (pinfunction "GND_GND") (pintype "bidirectional"))
      (node (ref "U94") (pin "GND") (pinfunction "GND_GND") (pintype "bidirectional"))
      (node (ref "U95") (pin "GND") (pinfunction "GND_GND") (pintype "bidirectional"))
      (node (ref "U96") (pin "GND") (pinfunction "GND_GND") (pintype "bidirectional"))
      (node (ref "U97") (pin "GND") (pinfunction "GND_GND") (pintype "bidirectional"))
      (node (ref "U98") (pin "GND") (pinfunction "GND_GND") (pintype "bidirectional"))
      (node (ref "U99") (pin "GND") (pinfunction "GND_GND") (pintype "bidirectional"))
    )
    (net (code "10") (name "Net-(U1-CI)") (class "Default")
      (node (ref "J2") (pin "4") (pinfunction "4_4") (pintype "passive"))
      (node (ref "U1") (pin "CKI") (pinfunction "CI_CKI") (pintype "bidirectional"))
    )
    (net (code "11") (name "Net-(U1-CO)") (class "Default")
      (node (ref "U1") (pin "CKO") (pinfunction "CO_CKO") (pintype "bidirectional"))
      (node (ref "U2") (pin "CKI") (pinfunction "CI_CKI") (pintype "bidirectional"))
    )
    (net (code "12") (name "Net-(U1-DI)") (class "Default")
      (node (ref "J2") (pin "3") (pinfunction "3_3") (pintype "passive"))
      (node (ref "U1") (pin "SDI") (pinfunction "DI_SDI") (pintype "bidirectional"))
    )
    (net (code "13") (name "Net-(U1-DO)") (class "Default")
      (node (ref "U1") (pin "SDO") (pinfunction "DO_SDO") (pintype "bidirectional"))
      (node (ref "U2") (pin "SDI") (pinfunction "DI_SDI") (pintype "bidirectional"))
    )
    (net (code "14") (name "Net-(U2-CO)") (class "Default")
      (node (ref "U2") (pin "CKO") (pinfunction "CO_CKO") (pintype "bidirectional"))
      (node (ref "U3") (pin "CKI") (pinfunction "CI_CKI") (pintype "bidirectional"))
    )
    (net (code "15") (name "Net-(U2-DO)") (class "Default")
      (node (ref "U2") (pin "SDO") (pinfunction "DO_SDO") (pintype "bidirectional"))
      (node (ref "U3") (pin "SDI") (pinfunction "DI_SDI") (pintype "bidirectional"))
    )
    (net (code "16") (name "Net-(U3-CO)") (class "Default")
      (node (ref "U3") (pin "CKO") (pinfunction "CO_CKO") (pintype "bidirectional"))
      (node (ref "U4") (pin "CKI") (pinfunction "CI_CKI") (pintype "bidirectional"))
    )
    (net (code "17") (name "Net-(U3-DO)") (class "Default")
      (node (ref "U3") (pin "SDO") (pinfunction "DO_SDO") (pintype "bidirectional"))
      (node (ref "U4") (pin "SDI") (pinfunction "DI_SDI") (pintype "bidirectional"))
    )
    (net (code "18") (name "Net-(U4-CO)") (class "Default")
      (node (ref "U4") (pin "CKO") (pinfunction "CO_CKO") (pintype "bidirectional"))
      (node (ref "U5") (pin "CKI") (pinfunction "CI_CKI") (pintype "bidirectional"))
    )
    (net (code "19") (name "Net-(U4-DO)") (class "Default")
      (node (ref "U4") (pin "SDO") (pinfunction "DO_SDO") (pintype "bidirectional"))
      (node (ref "U5") (pin "SDI") (pinfunction "DI_SDI") (pintype "bidirectional"))
    )
    (net (code "20") (name "Net-(U5-CO)") (class "Default")
      (node (ref "U5") (pin "CKO") (pinfunction "CO_CKO") (pintype "bidirectional"))
      (node (ref "U6") (pin "CKI") (pinfunction "CI_CKI") (pintype "bidirectional"))
    )
    (net (code "21") (name "Net-(U5-DO)") (class "Default")
      (node (ref "U5") (pin "SDO") (pinfunction "DO_SDO") (pintype "bidirectional"))
      (node (ref "U6") (pin "SDI") (pinfunction "DI_SDI") (pintype "bidirectional"))
    )
    (net (code "22") (name "Net-(U6-CO)") (class "Default")
      (node (ref "U6") (pin "CKO") (pinfunction "CO_CKO") (pintype "bidirectional"))
      (node (ref "U7") (pin "CKI") (pinfunction "CI_CKI") (pintype "bidirectional"))
    )
    (net (code "23") (name "Net-(U6-DO)") (class "Default")
      (node (ref "U6") (pin "SDO") (pinfunction "DO_SDO") (pintype "bidirectional"))
      (node (ref "U7") (pin "SDI") (pinfunction "DI_SDI") (pintype "bidirectional"))
    )
    (net (code "24") (name "Net-(U7-CO)") (class "Default")
      (node (ref "U7") (pin "CKO") (pinfunction "CO_CKO") (pintype "bidirectional"))
      (node (ref "U8") (pin "CKI") (pinfunction "CI_CKI") (pintype "bidirectional"))
    )
    (net (code "25") (name "Net-(U7-DO)") (class "Default")
      (node (ref "U7") (pin "SDO") (pinfunction "DO_SDO") (pintype "bidirectional"))
      (node (ref "U8") (pin "SDI") (pinfunction "DI_SDI") (pintype "bidirectional"))
    )
    (net (code "26") (name "Net-(U8-CO)") (class "Default")
      (node (ref "U8") (pin "CKO") (pinfunction "CO_CKO") (pintype "bidirectional"))
      (node (ref "U9") (pin "CKI") (pinfunction "CI_CKI") (pintype "bidirectional"))
    )
    (net (code "27") (name "Net-(U8-DO)") (class "Default")
      (node (ref "U8") (pin "SDO") (pinfunction "DO_SDO") (pintype "bidirectional"))
      (node (ref "U9") (pin "SDI") (pinfunction "DI_SDI") (pintype "bidirectional"))
    )
    (net (code "28") (name "Net-(U10-CI)") (class "Default")
      (node (ref "U10") (pin "CKI") (pinfunction "CI_CKI") (pintype "bidirectional"))
      (node (ref "U9") (pin "CKO") (pinfunction "CO_CKO") (pintype "bidirectional"))
    )
    (net (code "29") (name "Net-(U10-CO)") (class "Default")
      (node (ref "U10") (pin "CKO") (pinfunction "CO_CKO") (pintype "bidirectional"))
      (node (ref "U11") (pin "CKI") (pinfunction "CI_CKI") (pintype "bidirectional"))
    )
    (net (code "30") (name "Net-(U10-DI)") (class "Default")
      (node (ref "U10") (pin "SDI") (pinfunction "DI_SDI") (pintype "bidirectional"))
      (node (ref "U9") (pin "SDO") (pinfunction "DO_SDO") (pintype "bidirectional"))
    )
    (net (code "31") (name "Net-(U10-DO)") (class "Default")
      (node (ref "U10") (pin "SDO") (pinfunction "DO_SDO") (pintype "bidirectional"))
      (node (ref "U11") (pin "SDI") (pinfunction "DI_SDI") (pintype "bidirectional"))
    )
    (net (code "32") (name "Net-(U11-CO)") (class "Default")
      (node (ref "U11") (pin "CKO") (pinfunction "CO_CKO") (pintype "bidirectional"))
      (node (ref "U12") (pin "CKI") (pinfunction "CI_CKI") (pintype "bidirectional"))
    )
    (net (code "33") (name "Net-(U11-DO)") (class "Default")
      (node (ref "U11") (pin "SDO") (pinfunction "DO_SDO") (pintype "bidirectional"))
      (node (ref "U12") (pin "SDI") (pinfunction "DI_SDI") (pintype "bidirectional"))
    )
    (net (code "34") (name "Net-(U12-CO)") (class "Default")
      (node (ref "U12") (pin "CKO") (pinfunction "CO_CKO") (pintype "bidirectional"))
      (node (ref "U13") (pin "CKI") (pinfunction "CI_CKI") (pintype "bidirectional"))
    )
    (net (code "35") (name "Net-(U12-DO)") (class "Default")
      (node (ref "U12") (pin "SDO") (pinfunction "DO_SDO") (pintype "bidirectional"))
      (node (ref "U13") (pin "SDI") (pinfunction "DI_SDI") (pintype "bidirectional"))
    )
    (net (code "36") (name "Net-(U13-CO)") (class "Default")
      (node (ref "U13") (pin "CKO") (pinfunction "CO_CKO") (pintype "bidirectional"))
      (node (ref "U14") (pin "CKI") (pinfunction "CI_CKI") (pintype "bidirectional"))
    )
    (net (code "37") (name "Net-(U13-DO)") (class "Default")
      (node (ref "U13") (pin "SDO") (pinfunction "DO_SDO") (pintype "bidirectional"))
      (node (ref "U14") (pin "SDI") (pinfunction "DI_SDI") (pintype "bidirectional"))
    )
    (net (code "38") (name "Net-(U14-CO)") (class "Default")
      (node (ref "U14") (pin "CKO") (pinfunction "CO_CKO") (pintype "bidirectional"))
      (node (ref "U15") (pin "CKI") (pinfunction "CI_CKI") (pintype "bidirectional"))
    )
    (net (code "39") (name "Net-(U14-DO)") (class "Default")
      (node (ref "U14") (pin "SDO") (pinfunction "DO_SDO") (pintype "bidirectional"))
      (node (ref "U15") (pin "SDI") (pinfunction "DI_SDI") (pintype "bidirectional"))
    )
    (net (code "40") (name "Net-(U15-CO)") (class "Default")
      (node (ref "U15") (pin "CKO") (pinfunction "CO_CKO") (pintype "bidirectional"))
      (node (ref "U16") (pin "CKI") (pinfunction "CI_CKI") (pintype "bidirectional"))
    )
    (net (code "41") (name "Net-(U15-DO)") (class "Default")
      (node (ref "U15") (pin "SDO") (pinfunction "DO_SDO") (pintype "bidirectional"))
      (node (ref "U16") (pin "SDI") (pinfunction "DI_SDI") (pintype "bidirectional"))
    )
    (net (code "42") (name "Net-(U16-CO)") (class "Default")
      (node (ref "U16") (pin "CKO") (pinfunction "CO_CKO") (pintype "bidirectional"))
      (node (ref "U17") (pin "CKI") (pinfunction "CI_CKI") (pintype "bidirectional"))
    )
    (net (code "43") (name "Net-(U16-DO)") (class "Default")
      (node (ref "U16") (pin "SDO") (pinfunction "DO_SDO") (pintype "bidirectional"))
      (node (ref "U17") (pin "SDI") (pinfunction "DI_SDI") (pintype "bidirectional"))
    )
    (net (code "44") (name "Net-(U17-CO)") (class "Default")
      (node (ref "U17") (pin "CKO") (pinfunction "CO_CKO") (pintype "bidirectional"))
      (node (ref "U18") (pin "CKI") (pinfunction "CI_CKI") (pintype "bidirectional"))
    )
    (net (code "45") (name "Net-(U17-DO)") (class "Default")
      (node (ref "U17") (pin "SDO") (pinfunction "DO_SDO") (pintype "bidirectional"))
      (node (ref "U18") (pin "SDI") (pinfunction "DI_SDI") (pintype "bidirectional"))
    )
    (net (code "46") (name "Net-(U18-CO)") (class "Default")
      (node (ref "U18") (pin "CKO") (pinfunction "CO_CKO") (pintype "bidirectional"))
      (node (ref "U19") (pin "CKI") (pinfunction "CI_CKI") (pintype "bidirectional"))
    )
    (net (code "47") (name "Net-(U18-DO)") (class "Default")
      (node (ref "U18") (pin "SDO") (pinfunction "DO_SDO") (pintype "bidirectional"))
      (node (ref "U19") (pin "SDI") (pinfunction "DI_SDI") (pintype "bidirectional"))
    )
    (net (code "48") (name "Net-(U19-CO)") (class "Default")
      (node (ref "U19") (pin "CKO") (pinfunction "CO_CKO") (pintype "bidirectional"))
      (node (ref "U20") (pin "CKI") (pinfunction "CI_CKI") (pintype "bidirectional"))
    )
    (net (code "49") (name "Net-(U19-DO)") (class "Default")
      (node (ref "U19") (pin "SDO") (pinfunction "DO_SDO") (pintype "bidirectional"))
      (node (ref "U20") (pin "SDI") (pinfunction "DI_SDI") (pintype "bidirectional"))
    )
    (net (code "50") (name "Net-(U20-CO)") (class "Default")
      (node (ref "U20") (pin "CKO") (pinfunction "CO_CKO") (pintype "bidirectional"))
      (node (ref "U21") (pin "CKI") (pinfunction "CI_CKI") (pintype "bidirectional"))
    )
    (net (code "51") (name "Net-(U20-DO)") (class "Default")
      (node (ref "U20") (pin "SDO") (pinfunction "DO_SDO") (pintype "bidirectional"))
      (node (ref "U21") (pin "SDI") (pinfunction "DI_SDI") (pintype "bidirectional"))
    )
    (net (code "52") (name "Net-(U21-CO)") (class "Default")
      (node (ref "U21") (pin "CKO") (pinfunction "CO_CKO") (pintype "bidirectional"))
      (node (ref "U22") (pin "CKI") (pinfunction "CI_CKI") (pintype "bidirectional"))
    )
    (net (code "53") (name "Net-(U21-DO)") (class "Default")
      (node (ref "U21") (pin "SDO") (pinfunction "DO_SDO") (pintype "bidirectional"))
      (node (ref "U22") (pin "SDI") (pinfunction "DI_SDI") (pintype "bidirectional"))
    )
    (net (code "54") (name "Net-(U22-CO)") (class "Default")
      (node (ref "U22") (pin "CKO") (pinfunction "CO_CKO") (pintype "bidirectional"))
      (node (ref "U23") (pin "CKI") (pinfunction "CI_CKI") (pintype "bidirectional"))
    )
    (net (code "55") (name "Net-(U22-DO)") (class "Default")
      (node (ref "U22") (pin "SDO") (pinfunction "DO_SDO") (pintype "bidirectional"))
      (node (ref "U23") (pin "SDI") (pinfunction "DI_SDI") (pintype "bidirectional"))
    )
    (net (code "56") (name "Net-(U23-CO)") (class "Default")
      (node (ref "U23") (pin "CKO") (pinfunction "CO_CKO") (pintype "bidirectional"))
      (node (ref "U24") (pin "CKI") (pinfunction "CI_CKI") (pintype "bidirectional"))
    )
    (net (code "57") (name "Net-(U23-DO)") (class "Default")
      (node (ref "U23") (pin "SDO") (pinfunction "DO_SDO") (pintype "bidirectional"))
      (node (ref "U24") (pin "SDI") (pinfunction "DI_SDI") (pintype "bidirectional"))
    )
    (net (code "58") (name "Net-(U24-CO)") (class "Default")
      (node (ref "U24") (pin "CKO") (pinfunction "CO_CKO") (pintype "bidirectional"))
      (node (ref "U25") (pin "CKI") (pinfunction "CI_CKI") (pintype "bidirectional"))
    )
    (net (code "59") (name "Net-(U24-DO)") (class "Default")
      (node (ref "U24") (pin "SDO") (pinfunction "DO_SDO") (pintype "bidirectional"))
      (node (ref "U25") (pin "SDI") (pinfunction "DI_SDI") (pintype "bidirectional"))
    )
    (net (code "60") (name "Net-(U25-CO)") (class "Default")
      (node (ref "U25") (pin "CKO") (pinfunction "CO_CKO") (pintype "bidirectional"))
      (node (ref "U26") (pin "CKI") (pinfunction "CI_CKI") (pintype "bidirectional"))
    )
    (net (code "61") (name "Net-(U25-DO)") (class "Default")
      (node (ref "U25") (pin "SDO") (pinfunction "DO_SDO") (pintype "bidirectional"))
      (node (ref "U26") (pin "SDI") (pinfunction "DI_SDI") (pintype "bidirectional"))
    )
    (net (code "62") (name "Net-(U26-CO)") (class "Default")
      (node (ref "U26") (pin "CKO") (pinfunction "CO_CKO") (pintype "bidirectional"))
      (node (ref "U27") (pin "CKI") (pinfunction "CI_CKI") (pintype "bidirectional"))
    )
    (net (code "63") (name "Net-(U26-DO)") (class "Default")
      (node (ref "U26") (pin "SDO") (pinfunction "DO_SDO") (pintype "bidirectional"))
      (node (ref "U27") (pin "SDI") (pinfunction "DI_SDI") (pintype "bidirectional"))
    )
    (net (code "64") (name "Net-(U27-CO)") (class "Default")
      (node (ref "U27") (pin "CKO") (pinfunction "CO_CKO") (pintype "bidirectional"))
      (node (ref "U28") (pin "CKI") (pinfunction "CI_CKI") (pintype "bidirectional"))
    )
    (net (code "65") (name "Net-(U27-DO)") (class "Default")
      (node (ref "U27") (pin "SDO") (pinfunction "DO_SDO") (pintype "bidirectional"))
      (node (ref "U28") (pin "SDI") (pinfunction "DI_SDI") (pintype "bidirectional"))
    )
    (net (code "66") (name "Net-(U29-CO)") (class "Default")
      (node (ref "U29") (pin "CKO") (pinfunction "CO_CKO") (pintype "bidirectional"))
      (node (ref "U30") (pin "CKI") (pinfunction "CI_CKI") (pintype "bidirectional"))
    )
    (net (code "67") (name "Net-(U29-DO)") (class "Default")
      (node (ref "U29") (pin "SDO") (pinfunction "DO_SDO") (pintype "bidirectional"))
      (node (ref "U30") (pin "SDI") (pinfunction "DI_SDI") (pintype "bidirectional"))
    )
    (net (code "68") (name "Net-(U30-CO)") (class "Default")
      (node (ref "U30") (pin "CKO") (pinfunction "CO_CKO") (pintype "bidirectional"))
      (node (ref "U31") (pin "CKI") (pinfunction "CI_CKI") (pintype "bidirectional"))
    )
    (net (code "69") (name "Net-(U30-DO)") (class "Default")
      (node (ref "U30") (pin "SDO") (pinfunction "DO_SDO") (pintype "bidirectional"))
      (node (ref "U31") (pin "SDI") (pinfunction "DI_SDI") (pintype "bidirectional"))
    )
    (net (code "70") (name "Net-(U31-CO)") (class "Default")
      (node (ref "U31") (pin "CKO") (pinfunction "CO_CKO") (pintype "bidirectional"))
      (node (ref "U32") (pin "CKI") (pinfunction "CI_CKI") (pintype "bidirectional"))
    )
    (net (code "71") (name "Net-(U31-DO)") (class "Default")
      (node (ref "U31") (pin "SDO") (pinfunction "DO_SDO") (pintype "bidirectional"))
      (node (ref "U32") (pin "SDI") (pinfunction "DI_SDI") (pintype "bidirectional"))
    )
    (net (code "72") (name "Net-(U32-CO)") (class "Default")
      (node (ref "U32") (pin "CKO") (pinfunction "CO_CKO") (pintype "bidirectional"))
      (node (ref "U33") (pin "CKI") (pinfunction "CI_CKI") (pintype "bidirectional"))
    )
    (net (code "73") (name "Net-(U32-DO)") (class "Default")
      (node (ref "U32") (pin "SDO") (pinfunction "DO_SDO") (pintype "bidirectional"))
      (node (ref "U33") (pin "SDI") (pinfunction "DI_SDI") (pintype "bidirectional"))
    )
    (net (code "74") (name "Net-(U33-CO)") (class "Default")
      (node (ref "U33") (pin "CKO") (pinfunction "CO_CKO") (pintype "bidirectional"))
      (node (ref "U34") (pin "CKI") (pinfunction "CI_CKI") (pintype "bidirectional"))
    )
    (net (code "75") (name "Net-(U33-DO)") (class "Default")
      (node (ref "U33") (pin "SDO") (pinfunction "DO_SDO") (pintype "bidirectional"))
      (node (ref "U34") (pin "SDI") (pinfunction "DI_SDI") (pintype "bidirectional"))
    )
    (net (code "76") (name "Net-(U34-CO)") (class "Default")
      (node (ref "U34") (pin "CKO") (pinfunction "CO_CKO") (pintype "bidirectional"))
      (node (ref "U35") (pin "CKI") (pinfunction "CI_CKI") (pintype "bidirectional"))
    )
    (net (code "77") (name "Net-(U34-DO)") (class "Default")
      (node (ref "U34") (pin "SDO") (pinfunction "DO_SDO") (pintype "bidirectional"))
      (node (ref "U35") (pin "SDI") (pinfunction "DI_SDI") (pintype "bidirectional"))
    )
    (net (code "78") (name "Net-(U35-CO)") (class "Default")
      (node (ref "U35") (pin "CKO") (pinfunction "CO_CKO") (pintype "bidirectional"))
      (node (ref "U36") (pin "CKI") (pinfunction "CI_CKI") (pintype "bidirectional"))
    )
    (net (code "79") (name "Net-(U35-DO)") (class "Default")
      (node (ref "U35") (pin "SDO") (pinfunction "DO_SDO") (pintype "bidirectional"))
      (node (ref "U36") (pin "SDI") (pinfunction "DI_SDI") (pintype "bidirectional"))
    )
    (net (code "80") (name "Net-(U36-CO)") (class "Default")
      (node (ref "U36") (pin "CKO") (pinfunction "CO_CKO") (pintype "bidirectional"))
      (node (ref "U37") (pin "CKI") (pinfunction "CI_CKI") (pintype "bidirectional"))
    )
    (net (code "81") (name "Net-(U36-DO)") (class "Default")
      (node (ref "U36") (pin "SDO") (pinfunction "DO_SDO") (pintype "bidirectional"))
      (node (ref "U37") (pin "SDI") (pinfunction "DI_SDI") (pintype "bidirectional"))
    )
    (net (code "82") (name "Net-(U37-CO)") (class "Default")
      (node (ref "U37") (pin "CKO") (pinfunction "CO_CKO") (pintype "bidirectional"))
      (node (ref "U38") (pin "CKI") (pinfunction "CI_CKI") (pintype "bidirectional"))
    )
    (net (code "83") (name "Net-(U37-DO)") (class "Default")
      (node (ref "U37") (pin "SDO") (pinfunction "DO_SDO") (pintype "bidirectional"))
      (node (ref "U38") (pin "SDI") (pinfunction "DI_SDI") (pintype "bidirectional"))
    )
    (net (code "84") (name "Net-(U38-CO)") (class "Default")
      (node (ref "U38") (pin "CKO") (pinfunction "CO_CKO") (pintype "bidirectional"))
      (node (ref "U39") (pin "CKI") (pinfunction "CI_CKI") (pintype "bidirectional"))
    )
    (net (code "85") (name "Net-(U38-DO)") (class "Default")
      (node (ref "U38") (pin "SDO") (pinfunction "DO_SDO") (pintype "bidirectional"))
      (node (ref "U39") (pin "SDI") (pinfunction "DI_SDI") (pintype "bidirectional"))
    )
    (net (code "86") (name "Net-(U39-CO)") (class "Default")
      (node (ref "U39") (pin "CKO") (pinfunction "CO_CKO") (pintype "bidirectional"))
      (node (ref "U40") (pin "CKI") (pinfunction "CI_CKI") (pintype "bidirectional"))
    )
    (net (code "87") (name "Net-(U39-DO)") (class "Default")
      (node (ref "U39") (pin "SDO") (pinfunction "DO_SDO") (pintype "bidirectional"))
      (node (ref "U40") (pin "SDI") (pinfunction "DI_SDI") (pintype "bidirectional"))
    )
    (net (code "88") (name "Net-(U40-CO)") (class "Default")
      (node (ref "U40") (pin "CKO") (pinfunction "CO_CKO") (pintype "bidirectional"))
      (node (ref "U41") (pin "CKI") (pinfunction "CI_CKI") (pintype "bidirectional"))
    )
    (net (code "89") (name "Net-(U40-DO)") (class "Default")
      (node (ref "U40") (pin "SDO") (pinfunction "DO_SDO") (pintype "bidirectional"))
      (node (ref "U41") (pin "SDI") (pinfunction "DI_SDI") (pintype "bidirectional"))
    )
    (net (code "90") (name "Net-(U41-CO)") (class "Default")
      (node (ref "U41") (pin "CKO") (pinfunction "CO_CKO") (pintype "bidirectional"))
      (node (ref "U42") (pin "CKI") (pinfunction "CI_CKI") (pintype "bidirectional"))
    )
    (net (code "91") (name "Net-(U41-DO)") (class "Default")
      (node (ref "U41") (pin "SDO") (pinfunction "DO_SDO") (pintype "bidirectional"))
      (node (ref "U42") (pin "SDI") (pinfunction "DI_SDI") (pintype "bidirectional"))
    )
    (net (code "92") (name "Net-(U42-CO)") (class "Default")
      (node (ref "U42") (pin "CKO") (pinfunction "CO_CKO") (pintype "bidirectional"))
      (node (ref "U43") (pin "CKI") (pinfunction "CI_CKI") (pintype "bidirectional"))
    )
    (net (code "93") (name "Net-(U42-DO)") (class "Default")
      (node (ref "U42") (pin "SDO") (pinfunction "DO_SDO") (pintype "bidirectional"))
      (node (ref "U43") (pin "SDI") (pinfunction "DI_SDI") (pintype "bidirectional"))
    )
    (net (code "94") (name "Net-(U43-CO)") (class "Default")
      (node (ref "U43") (pin "CKO") (pinfunction "CO_CKO") (pintype "bidirectional"))
      (node (ref "U44") (pin "CKI") (pinfunction "CI_CKI") (pintype "bidirectional"))
    )
    (net (code "95") (name "Net-(U43-DO)") (class "Default")
      (node (ref "U43") (pin "SDO") (pinfunction "DO_SDO") (pintype "bidirectional"))
      (node (ref "U44") (pin "SDI") (pinfunction "DI_SDI") (pintype "bidirectional"))
    )
    (net (code "96") (name "Net-(U44-CO)") (class "Default")
      (node (ref "U44") (pin "CKO") (pinfunction "CO_CKO") (pintype "bidirectional"))
      (node (ref "U45") (pin "CKI") (pinfunction "CI_CKI") (pintype "bidirectional"))
    )
    (net (code "97") (name "Net-(U44-DO)") (class "Default")
      (node (ref "U44") (pin "SDO") (pinfunction "DO_SDO") (pintype "bidirectional"))
      (node (ref "U45") (pin "SDI") (pinfunction "DI_SDI") (pintype "bidirectional"))
    )
    (net (code "98") (name "Net-(U45-CO)") (class "Default")
      (node (ref "U45") (pin "CKO") (pinfunction "CO_CKO") (pintype "bidirectional"))
      (node (ref "U46") (pin "CKI") (pinfunction "CI_CKI") (pintype "bidirectional"))
    )
    (net (code "99") (name "Net-(U45-DO)") (class "Default")
      (node (ref "U45") (pin "SDO") (pinfunction "DO_SDO") (pintype "bidirectional"))
      (node (ref "U46") (pin "SDI") (pinfunction "DI_SDI") (pintype "bidirectional"))
    )
    (net (code "100") (name "Net-(U46-CO)") (class "Default")
      (node (ref "U46") (pin "CKO") (pinfunction "CO_CKO") (pintype "bidirectional"))
      (node (ref "U47") (pin "CKI") (pinfunction "CI_CKI") (pintype "bidirectional"))
    )
    (net (code "101") (name "Net-(U46-DO)") (class "Default")
      (node (ref "U46") (pin "SDO") (pinfunction "DO_SDO") (pintype "bidirectional"))
      (node (ref "U47") (pin "SDI") (pinfunction "DI_SDI") (pintype "bidirectional"))
    )
    (net (code "102") (name "Net-(U47-CO)") (class "Default")
      (node (ref "U47") (pin "CKO") (pinfunction "CO_CKO") (pintype "bidirectional"))
      (node (ref "U48") (pin "CKI") (pinfunction "CI_CKI") (pintype "bidirectional"))
    )
    (net (code "103") (name "Net-(U47-DO)") (class "Default")
      (node (ref "U47") (pin "SDO") (pinfunction "DO_SDO") (pintype "bidirectional"))
      (node (ref "U48") (pin "SDI") (pinfunction "DI_SDI") (pintype "bidirectional"))
    )
    (net (code "104") (name "Net-(U48-CO)") (class "Default")
      (node (ref "U48") (pin "CKO") (pinfunction "CO_CKO") (pintype "bidirectional"))
      (node (ref "U49") (pin "CKI") (pinfunction "CI_CKI") (pintype "bidirectional"))
    )
    (net (code "105") (name "Net-(U48-DO)") (class "Default")
      (node (ref "U48") (pin "SDO") (pinfunction "DO_SDO") (pintype "bidirectional"))
      (node (ref "U49") (pin "SDI") (pinfunction "DI_SDI") (pintype "bidirectional"))
    )
    (net (code "106") (name "Net-(U49-CO)") (class "Default")
      (node (ref "U49") (pin "CKO") (pinfunction "CO_CKO") (pintype "bidirectional"))
      (node (ref "U50") (pin "CKI") (pinfunction "CI_CKI") (pintype "bidirectional"))
    )
    (net (code "107") (name "Net-(U49-DO)") (class "Default")
      (node (ref "U49") (pin "SDO") (pinfunction "DO_SDO") (pintype "bidirectional"))
      (node (ref "U50") (pin "SDI") (pinfunction "DI_SDI") (pintype "bidirectional"))
    )
    (net (code "108") (name "Net-(U50-CO)") (class "Default")
      (node (ref "U50") (pin "CKO") (pinfunction "CO_CKO") (pintype "bidirectional"))
      (node (ref "U51") (pin "CKI") (pinfunction "CI_CKI") (pintype "bidirectional"))
    )
    (net (code "109") (name "Net-(U50-DO)") (class "Default")
      (node (ref "U50") (pin "SDO") (pinfunction "DO_SDO") (pintype "bidirectional"))
      (node (ref "U51") (pin "SDI") (pinfunction "DI_SDI") (pintype "bidirectional"))
    )
    (net (code "110") (name "Net-(U51-CO)") (class "Default")
      (node (ref "U51") (pin "CKO") (pinfunction "CO_CKO") (pintype "bidirectional"))
      (node (ref "U52") (pin "CKI") (pinfunction "CI_CKI") (pintype "bidirectional"))
    )
    (net (code "111") (name "Net-(U51-DO)") (class "Default")
      (node (ref "U51") (pin "SDO") (pinfunction "DO_SDO") (pintype "bidirectional"))
      (node (ref "U52") (pin "SDI") (pinfunction "DI_SDI") (pintype "bidirectional"))
    )
    (net (code "112") (name "Net-(U52-CO)") (class "Default")
      (node (ref "U52") (pin "CKO") (pinfunction "CO_CKO") (pintype "bidirectional"))
      (node (ref "U53") (pin "CKI") (pinfunction "CI_CKI") (pintype "bidirectional"))
    )
    (net (code "113") (name "Net-(U52-DO)") (class "Default")
      (node (ref "U52") (pin "SDO") (pinfunction "DO_SDO") (pintype "bidirectional"))
      (node (ref "U53") (pin "SDI") (pinfunction "DI_SDI") (pintype "bidirectional"))
    )
    (net (code "114") (name "Net-(U53-CO)") (class "Default")
      (node (ref "U53") (pin "CKO") (pinfunction "CO_CKO") (pintype "bidirectional"))
      (node (ref "U54") (pin "CKI") (pinfunction "CI_CKI") (pintype "bidirectional"))
    )
    (net (code "115") (name "Net-(U53-DO)") (class "Default")
      (node (ref "U53") (pin "SDO") (pinfunction "DO_SDO") (pintype "bidirectional"))
      (node (ref "U54") (pin "SDI") (pinfunction "DI_SDI") (pintype "bidirectional"))
    )
    (net (code "116") (name "Net-(U54-CO)") (class "Default")
      (node (ref "U54") (pin "CKO") (pinfunction "CO_CKO") (pintype "bidirectional"))
      (node (ref "U55") (pin "CKI") (pinfunction "CI_CKI") (pintype "bidirectional"))
    )
    (net (code "117") (name "Net-(U54-DO)") (class "Default")
      (node (ref "U54") (pin "SDO") (pinfunction "DO_SDO") (pintype "bidirectional"))
      (node (ref "U55") (pin "SDI") (pinfunction "DI_SDI") (pintype "bidirectional"))
    )
    (net (code "118") (name "Net-(U55-CO)") (class "Default")
      (node (ref "U55") (pin "CKO") (pinfunction "CO_CKO") (pintype "bidirectional"))
      (node (ref "U56") (pin "CKI") (pinfunction "CI_CKI") (pintype "bidirectional"))
    )
    (net (code "119") (name "Net-(U55-DO)") (class "Default")
      (node (ref "U55") (pin "SDO") (pinfunction "DO_SDO") (pintype "bidirectional"))
      (node (ref "U56") (pin "SDI") (pinfunction "DI_SDI") (pintype "bidirectional"))
    )
    (net (code "120") (name "Net-(U57-CO)") (class "Default")
      (node (ref "U57") (pin "CKO") (pinfunction "CO_CKO") (pintype "bidirectional"))
      (node (ref "U58") (pin "CKI") (pinfunction "CI_CKI") (pintype "bidirectional"))
    )
    (net (code "121") (name "Net-(U57-DO)") (class "Default")
      (node (ref "U57") (pin "SDO") (pinfunction "DO_SDO") (pintype "bidirectional"))
      (node (ref "U58") (pin "SDI") (pinfunction "DI_SDI") (pintype "bidirectional"))
    )
    (net (code "122") (name "Net-(U58-CO)") (class "Default")
      (node (ref "U58") (pin "CKO") (pinfunction "CO_CKO") (pintype "bidirectional"))
      (node (ref "U59") (pin "CKI") (pinfunction "CI_CKI") (pintype "bidirectional"))
    )
    (net (code "123") (name "Net-(U58-DO)") (class "Default")
      (node (ref "U58") (pin "SDO") (pinfunction "DO_SDO") (pintype "bidirectional"))
      (node (ref "U59") (pin "SDI") (pinfunction "DI_SDI") (pintype "bidirectional"))
    )
    (net (code "124") (name "Net-(U59-CO)") (class "Default")
      (node (ref "U59") (pin "CKO") (pinfunction "CO_CKO") (pintype "bidirectional"))
      (node (ref "U60") (pin "CKI") (pinfunction "CI_CKI") (pintype "bidirectional"))
    )
    (net (code "125") (name "Net-(U59-DO)") (class "Default")
      (node (ref "U59") (pin "SDO") (pinfunction "DO_SDO") (pintype "bidirectional"))
      (node (ref "U60") (pin "SDI") (pinfunction "DI_SDI") (pintype "bidirectional"))
    )
    (net (code "126") (name "Net-(U60-CO)") (class "Default")
      (node (ref "U60") (pin "CKO") (pinfunction "CO_CKO") (pintype "bidirectional"))
      (node (ref "U61") (pin "CKI") (pinfunction "CI_CKI") (pintype "bidirectional"))
    )
    (net (code "127") (name "Net-(U60-DO)") (class "Default")
      (node (ref "U60") (pin "SDO") (pinfunction "DO_SDO") (pintype "bidirectional"))
      (node (ref "U61") (pin "SDI") (pinfunction "DI_SDI") (pintype "bidirectional"))
    )
    (net (code "128") (name "Net-(U61-CO)") (class "Default")
      (node (ref "U61") (pin "CKO") (pinfunction "CO_CKO") (pintype "bidirectional"))
      (node (ref "U62") (pin "CKI") (pinfunction "CI_CKI") (pintype "bidirectional"))
    )
    (net (code "129") (name "Net-(U61-DO)") (class "Default")
      (node (ref "U61") (pin "SDO") (pinfunction "DO_SDO") (pintype "bidirectional"))
      (node (ref "U62") (pin "SDI") (pinfunction "DI_SDI") (pintype "bidirectional"))
    )
    (net (code "130") (name "Net-(U62-CO)") (class "Default")
      (node (ref "U62") (pin "CKO") (pinfunction "CO_CKO") (pintype "bidirectional"))
      (node (ref "U63") (pin "CKI") (pinfunction "CI_CKI") (pintype "bidirectional"))
    )
    (net (code "131") (name "Net-(U62-DO)") (class "Default")
      (node (ref "U62") (pin "SDO") (pinfunction "DO_SDO") (pintype "bidirectional"))
      (node (ref "U63") (pin "SDI") (pinfunction "DI_SDI") (pintype "bidirectional"))
    )
    (net (code "132") (name "Net-(U63-CO)") (class "Default")
      (node (ref "U63") (pin "CKO") (pinfunction "CO_CKO") (pintype "bidirectional"))
      (node (ref "U64") (pin "CKI") (pinfunction "CI_CKI") (pintype "bidirectional"))
    )
    (net (code "133") (name "Net-(U63-DO)") (class "Default")
      (node (ref "U63") (pin "SDO") (pinfunction "DO_SDO") (pintype "bidirectional"))
      (node (ref "U64") (pin "SDI") (pinfunction "DI_SDI") (pintype "bidirectional"))
    )
    (net (code "134") (name "Net-(U64-CO)") (class "Default")
      (node (ref "U64") (pin "CKO") (pinfunction "CO_CKO") (pintype "bidirectional"))
      (node (ref "U65") (pin "CKI") (pinfunction "CI_CKI") (pintype "bidirectional"))
    )
    (net (code "135") (name "Net-(U64-DO)") (class "Default")
      (node (ref "U64") (pin "SDO") (pinfunction "DO_SDO") (pintype "bidirectional"))
      (node (ref "U65") (pin "SDI") (pinfunction "DI_SDI") (pintype "bidirectional"))
    )
    (net (code "136") (name "Net-(U65-CO)") (class "Default")
      (node (ref "U65") (pin "CKO") (pinfunction "CO_CKO") (pintype "bidirectional"))
      (node (ref "U66") (pin "CKI") (pinfunction "CI_CKI") (pintype "bidirectional"))
    )
    (net (code "137") (name "Net-(U65-DO)") (class "Default")
      (node (ref "U65") (pin "SDO") (pinfunction "DO_SDO") (pintype "bidirectional"))
      (node (ref "U66") (pin "SDI") (pinfunction "DI_SDI") (pintype "bidirectional"))
    )
    (net (code "138") (name "Net-(U66-CO)") (class "Default")
      (node (ref "U66") (pin "CKO") (pinfunction "CO_CKO") (pintype "bidirectional"))
      (node (ref "U67") (pin "CKI") (pinfunction "CI_CKI") (pintype "bidirectional"))
    )
    (net (code "139") (name "Net-(U66-DO)") (class "Default")
      (node (ref "U66") (pin "SDO") (pinfunction "DO_SDO") (pintype "bidirectional"))
      (node (ref "U67") (pin "SDI") (pinfunction "DI_SDI") (pintype "bidirectional"))
    )
    (net (code "140") (name "Net-(U67-CO)") (class "Default")
      (node (ref "U67") (pin "CKO") (pinfunction "CO_CKO") (pintype "bidirectional"))
      (node (ref "U68") (pin "CKI") (pinfunction "CI_CKI") (pintype "bidirectional"))
    )
    (net (code "141") (name "Net-(U67-DO)") (class "Default")
      (node (ref "U67") (pin "SDO") (pinfunction "DO_SDO") (pintype "bidirectional"))
      (node (ref "U68") (pin "SDI") (pinfunction "DI_SDI") (pintype "bidirectional"))
    )
    (net (code "142") (name "Net-(U68-CO)") (class "Default")
      (node (ref "U68") (pin "CKO") (pinfunction "CO_CKO") (pintype "bidirectional"))
      (node (ref "U69") (pin "CKI") (pinfunction "CI_CKI") (pintype "bidirectional"))
    )
    (net (code "143") (name "Net-(U68-DO)") (class "Default")
      (node (ref "U68") (pin "SDO") (pinfunction "DO_SDO") (pintype "bidirectional"))
      (node (ref "U69") (pin "SDI") (pinfunction "DI_SDI") (pintype "bidirectional"))
    )
    (net (code "144") (name "Net-(U69-CO)") (class "Default")
      (node (ref "U69") (pin "CKO") (pinfunction "CO_CKO") (pintype "bidirectional"))
      (node (ref "U70") (pin "CKI") (pinfunction "CI_CKI") (pintype "bidirectional"))
    )
    (net (code "145") (name "Net-(U69-DO)") (class "Default")
      (node (ref "U69") (pin "SDO") (pinfunction "DO_SDO") (pintype "bidirectional"))
      (node (ref "U70") (pin "SDI") (pinfunction "DI_SDI") (pintype "bidirectional"))
    )
    (net (code "146") (name "Net-(U70-CO)") (class "Default")
      (node (ref "U70") (pin "CKO") (pinfunction "CO_CKO") (pintype "bidirectional"))
      (node (ref "U71") (pin "CKI") (pinfunction "CI_CKI") (pintype "bidirectional"))
    )
    (net (code "147") (name "Net-(U70-DO)") (class "Default")
      (node (ref "U70") (pin "SDO") (pinfunction "DO_SDO") (pintype "bidirectional"))
      (node (ref "U71") (pin "SDI") (pinfunction "DI_SDI") (pintype "bidirectional"))
    )
    (net (code "148") (name "Net-(U71-CO)") (class "Default")
      (node (ref "U71") (pin "CKO") (pinfunction "CO_CKO") (pintype "bidirectional"))
      (node (ref "U72") (pin "CKI") (pinfunction "CI_CKI") (pintype "bidirectional"))
    )
    (net (code "149") (name "Net-(U71-DO)") (class "Default")
      (node (ref "U71") (pin "SDO") (pinfunction "DO_SDO") (pintype "bidirectional"))
      (node (ref "U72") (pin "SDI") (pinfunction "DI_SDI") (pintype "bidirectional"))
    )
    (net (code "150") (name "Net-(U72-CO)") (class "Default")
      (node (ref "U72") (pin "CKO") (pinfunction "CO_CKO") (pintype "bidirectional"))
      (node (ref "U73") (pin "CKI") (pinfunction "CI_CKI") (pintype "bidirectional"))
    )
    (net (code "151") (name "Net-(U72-DO)") (class "Default")
      (node (ref "U72") (pin "SDO") (pinfunction "DO_SDO") (pintype "bidirectional"))
      (node (ref "U73") (pin "SDI") (pinfunction "DI_SDI") (pintype "bidirectional"))
    )
    (net (code "152") (name "Net-(U73-CO)") (class "Default")
      (node (ref "U73") (pin "CKO") (pinfunction "CO_CKO") (pintype "bidirectional"))
      (node (ref "U74") (pin "CKI") (pinfunction "CI_CKI") (pintype "bidirectional"))
    )
    (net (code "153") (name "Net-(U73-DO)") (class "Default")
      (node (ref "U73") (pin "SDO") (pinfunction "DO_SDO") (pintype "bidirectional"))
      (node (ref "U74") (pin "SDI") (pinfunction "DI_SDI") (pintype "bidirectional"))
    )
    (net (code "154") (name "Net-(U74-CO)") (class "Default")
      (node (ref "U74") (pin "CKO") (pinfunction "CO_CKO") (pintype "bidirectional"))
      (node (ref "U75") (pin "CKI") (pinfunction "CI_CKI") (pintype "bidirectional"))
    )
    (net (code "155") (name "Net-(U74-DO)") (class "Default")
      (node (ref "U74") (pin "SDO") (pinfunction "DO_SDO") (pintype "bidirectional"))
      (node (ref "U75") (pin "SDI") (pinfunction "DI_SDI") (pintype "bidirectional"))
    )
    (net (code "156") (name "Net-(U75-CO)") (class "Default")
      (node (ref "U75") (pin "CKO") (pinfunction "CO_CKO") (pintype "bidirectional"))
      (node (ref "U76") (pin "CKI") (pinfunction "CI_CKI") (pintype "bidirectional"))
    )
    (net (code "157") (name "Net-(U75-DO)") (class "Default")
      (node (ref "U75") (pin "SDO") (pinfunction "DO_SDO") (pintype "bidirectional"))
      (node (ref "U76") (pin "SDI") (pinfunction "DI_SDI") (pintype "bidirectional"))
    )
    (net (code "158") (name "Net-(U76-CO)") (class "Default")
      (node (ref "U76") (pin "CKO") (pinfunction "CO_CKO") (pintype "bidirectional"))
      (node (ref "U77") (pin "CKI") (pinfunction "CI_CKI") (pintype "bidirectional"))
    )
    (net (code "159") (name "Net-(U76-DO)") (class "Default")
      (node (ref "U76") (pin "SDO") (pinfunction "DO_SDO") (pintype "bidirectional"))
      (node (ref "U77") (pin "SDI") (pinfunction "DI_SDI") (pintype "bidirectional"))
    )
    (net (code "160") (name "Net-(U77-CO)") (class "Default")
      (node (ref "U77") (pin "CKO") (pinfunction "CO_CKO") (pintype "bidirectional"))
      (node (ref "U78") (pin "CKI") (pinfunction "CI_CKI") (pintype "bidirectional"))
    )
    (net (code "161") (name "Net-(U77-DO)") (class "Default")
      (node (ref "U77") (pin "SDO") (pinfunction "DO_SDO") (pintype "bidirectional"))
      (node (ref "U78") (pin "SDI") (pinfunction "DI_SDI") (pintype "bidirectional"))
    )
    (net (code "162") (name "Net-(U78-CO)") (class "Default")
      (node (ref "U78") (pin "CKO") (pinfunction "CO_CKO") (pintype "bidirectional"))
      (node (ref "U79") (pin "CKI") (pinfunction "CI_CKI") (pintype "bidirectional"))
    )
    (net (code "163") (name "Net-(U78-DO)") (class "Default")
      (node (ref "U78") (pin "SDO") (pinfunction "DO_SDO") (pintype "bidirectional"))
      (node (ref "U79") (pin "SDI") (pinfunction "DI_SDI") (pintype "bidirectional"))
    )
    (net (code "164") (name "Net-(U79-CO)") (class "Default")
      (node (ref "U79") (pin "CKO") (pinfunction "CO_CKO") (pintype "bidirectional"))
      (node (ref "U80") (pin "CKI") (pinfunction "CI_CKI") (pintype "bidirectional"))
    )
    (net (code "165") (name "Net-(U79-DO)") (class "Default")
      (node (ref "U79") (pin "SDO") (pinfunction "DO_SDO") (pintype "bidirectional"))
      (node (ref "U80") (pin "SDI") (pinfunction "DI_SDI") (pintype "bidirectional"))
    )
    (net (code "166") (name "Net-(U80-CO)") (class "Default")
      (node (ref "U80") (pin "CKO") (pinfunction "CO_CKO") (pintype "bidirectional"))
      (node (ref "U81") (pin "CKI") (pinfunction "CI_CKI") (pintype "bidirectional"))
    )
    (net (code "167") (name "Net-(U80-DO)") (class "Default")
      (node (ref "U80") (pin "SDO") (pinfunction "DO_SDO") (pintype "bidirectional"))
      (node (ref "U81") (pin "SDI") (pinfunction "DI_SDI") (pintype "bidirectional"))
    )
    (net (code "168") (name "Net-(U81-CO)") (class "Default")
      (node (ref "U81") (pin "CKO") (pinfunction "CO_CKO") (pintype "bidirectional"))
      (node (ref "U82") (pin "CKI") (pinfunction "CI_CKI") (pintype "bidirectional"))
    )
    (net (code "169") (name "Net-(U81-DO)") (class "Default")
      (node (ref "U81") (pin "SDO") (pinfunction "DO_SDO") (pintype "bidirectional"))
      (node (ref "U82") (pin "SDI") (pinfunction "DI_SDI") (pintype "bidirectional"))
    )
    (net (code "170") (name "Net-(U82-CO)") (class "Default")
      (node (ref "U82") (pin "CKO") (pinfunction "CO_CKO") (pintype "bidirectional"))
      (node (ref "U83") (pin "CKI") (pinfunction "CI_CKI") (pintype "bidirectional"))
    )
    (net (code "171") (name "Net-(U82-DO)") (class "Default")
      (node (ref "U82") (pin "SDO") (pinfunction "DO_SDO") (pintype "bidirectional"))
      (node (ref "U83") (pin "SDI") (pinfunction "DI_SDI") (pintype "bidirectional"))
    )
    (net (code "172") (name "Net-(U83-CO)") (class "Default")
      (node (ref "U83") (pin "CKO") (pinfunction "CO_CKO") (pintype "bidirectional"))
      (node (ref "U84") (pin "CKI") (pinfunction "CI_CKI") (pintype "bidirectional"))
    )
    (net (code "173") (name "Net-(U83-DO)") (class "Default")
      (node (ref "U83") (pin "SDO") (pinfunction "DO_SDO") (pintype "bidirectional"))
      (node (ref "U84") (pin "SDI") (pinfunction "DI_SDI") (pintype "bidirectional"))
    )
    (net (code "174") (name "Net-(U85-CO)") (class "Default")
      (node (ref "U85") (pin "CKO") (pinfunction "CO_CKO") (pintype "bidirectional"))
      (node (ref "U86") (pin "CKI") (pinfunction "CI_CKI") (pintype "bidirectional"))
    )
    (net (code "175") (name "Net-(U85-DO)") (class "Default")
      (node (ref "U85") (pin "SDO") (pinfunction "DO_SDO") (pintype "bidirectional"))
      (node (ref "U86") (pin "SDI") (pinfunction "DI_SDI") (pintype "bidirectional"))
    )
    (net (code "176") (name "Net-(U86-CO)") (class "Default")
      (node (ref "U86") (pin "CKO") (pinfunction "CO_CKO") (pintype "bidirectional"))
      (node (ref "U87") (pin "CKI") (pinfunction "CI_CKI") (pintype "bidirectional"))
    )
    (net (code "177") (name "Net-(U86-DO)") (class "Default")
      (node (ref "U86") (pin "SDO") (pinfunction "DO_SDO") (pintype "bidirectional"))
      (node (ref "U87") (pin "SDI") (pinfunction "DI_SDI") (pintype "bidirectional"))
    )
    (net (code "178") (name "Net-(U87-CO)") (class "Default")
      (node (ref "U87") (pin "CKO") (pinfunction "CO_CKO") (pintype "bidirectional"))
      (node (ref "U88") (pin "CKI") (pinfunction "CI_CKI") (pintype "bidirectional"))
    )
    (net (code "179") (name "Net-(U87-DO)") (class "Default")
      (node (ref "U87") (pin "SDO") (pinfunction "DO_SDO") (pintype "bidirectional"))
      (node (ref "U88") (pin "SDI") (pinfunction "DI_SDI") (pintype "bidirectional"))
    )
    (net (code "180") (name "Net-(U88-CO)") (class "Default")
      (node (ref "U88") (pin "CKO") (pinfunction "CO_CKO") (pintype "bidirectional"))
      (node (ref "U89") (pin "CKI") (pinfunction "CI_CKI") (pintype "bidirectional"))
    )
    (net (code "181") (name "Net-(U88-DO)") (class "Default")
      (node (ref "U88") (pin "SDO") (pinfunction "DO_SDO") (pintype "bidirectional"))
      (node (ref "U89") (pin "SDI") (pinfunction "DI_SDI") (pintype "bidirectional"))
    )
    (net (code "182") (name "Net-(U89-CO)") (class "Default")
      (node (ref "U89") (pin "CKO") (pinfunction "CO_CKO") (pintype "bidirectional"))
      (node (ref "U90") (pin "CKI") (pinfunction "CI_CKI") (pintype "bidirectional"))
    )
    (net (code "183") (name "Net-(U89-DO)") (class "Default")
      (node (ref "U89") (pin "SDO") (pinfunction "DO_SDO") (pintype "bidirectional"))
      (node (ref "U90") (pin "SDI") (pinfunction "DI_SDI") (pintype "bidirectional"))
    )
    (net (code "184") (name "Net-(U90-CO)") (class "Default")
      (node (ref "U90") (pin "CKO") (pinfunction "CO_CKO") (pintype "bidirectional"))
      (node (ref "U91") (pin "CKI") (pinfunction "CI_CKI") (pintype "bidirectional"))
    )
    (net (code "185") (name "Net-(U90-DO)") (class "Default")
      (node (ref "U90") (pin "SDO") (pinfunction "DO_SDO") (pintype "bidirectional"))
      (node (ref "U91") (pin "SDI") (pinfunction "DI_SDI") (pintype "bidirectional"))
    )
    (net (code "186") (name "Net-(U91-CO)") (class "Default")
      (node (ref "U91") (pin "CKO") (pinfunction "CO_CKO") (pintype "bidirectional"))
      (node (ref "U92") (pin "CKI") (pinfunction "CI_CKI") (pintype "bidirectional"))
    )
    (net (code "187") (name "Net-(U91-DO)") (class "Default")
      (node (ref "U91") (pin "SDO") (pinfunction "DO_SDO") (pintype "bidirectional"))
      (node (ref "U92") (pin "SDI") (pinfunction "DI_SDI") (pintype "bidirectional"))
    )
    (net (code "188") (name "Net-(U92-CO)") (class "Default")
      (node (ref "U92") (pin "CKO") (pinfunction "CO_CKO") (pintype "bidirectional"))
      (node (ref "U93") (pin "CKI") (pinfunction "CI_CKI") (pintype "bidirectional"))
    )
    (net (code "189") (name "Net-(U92-DO)") (class "Default")
      (node (ref "U92") (pin "SDO") (pinfunction "DO_SDO") (pintype "bidirectional"))
      (node (ref "U93") (pin "SDI") (pinfunction "DI_SDI") (pintype "bidirectional"))
    )
    (net (code "190") (name "Net-(U93-CO)") (class "Default")
      (node (ref "U93") (pin "CKO") (pinfunction "CO_CKO") (pintype "bidirectional"))
      (node (ref "U94") (pin "CKI") (pinfunction "CI_CKI") (pintype "bidirectional"))
    )
    (net (code "191") (name "Net-(U93-DO)") (class "Default")
      (node (ref "U93") (pin "SDO") (pinfunction "DO_SDO") (pintype "bidirectional"))
      (node (ref "U94") (pin "SDI") (pinfunction "DI_SDI") (pintype "bidirectional"))
    )
    (net (code "192") (name "Net-(U94-CO)") (class "Default")
      (node (ref "U94") (pin "CKO") (pinfunction "CO_CKO") (pintype "bidirectional"))
      (node (ref "U95") (pin "CKI") (pinfunction "CI_CKI") (pintype "bidirectional"))
    )
    (net (code "193") (name "Net-(U94-DO)") (class "Default")
      (node (ref "U94") (pin "SDO") (pinfunction "DO_SDO") (pintype "bidirectional"))
      (node (ref "U95") (pin "SDI") (pinfunction "DI_SDI") (pintype "bidirectional"))
    )
    (net (code "194") (name "Net-(U95-CO)") (class "Default")
      (node (ref "U95") (pin "CKO") (pinfunction "CO_CKO") (pintype "bidirectional"))
      (node (ref "U96") (pin "CKI") (pinfunction "CI_CKI") (pintype "bidirectional"))
    )
    (net (code "195") (name "Net-(U95-DO)") (class "Default")
      (node (ref "U95") (pin "SDO") (pinfunction "DO_SDO") (pintype "bidirectional"))
      (node (ref "U96") (pin "SDI") (pinfunction "DI_SDI") (pintype "bidirectional"))
    )
    (net (code "196") (name "Net-(U96-CO)") (class "Default")
      (node (ref "U96") (pin "CKO") (pinfunction "CO_CKO") (pintype "bidirectional"))
      (node (ref "U97") (pin "CKI") (pinfunction "CI_CKI") (pintype "bidirectional"))
    )
    (net (code "197") (name "Net-(U96-DO)") (class "Default")
      (node (ref "U96") (pin "SDO") (pinfunction "DO_SDO") (pintype "bidirectional"))
      (node (ref "U97") (pin "SDI") (pinfunction "DI_SDI") (pintype "bidirectional"))
    )
    (net (code "198") (name "Net-(U97-CO)") (class "Default")
      (node (ref "U97") (pin "CKO") (pinfunction "CO_CKO") (pintype "bidirectional"))
      (node (ref "U98") (pin "CKI") (pinfunction "CI_CKI") (pintype "bidirectional"))
    )
    (net (code "199") (name "Net-(U97-DO)") (class "Default")
      (node (ref "U97") (pin "SDO") (pinfunction "DO_SDO") (pintype "bidirectional"))
      (node (ref "U98") (pin "SDI") (pinfunction "DI_SDI") (pintype "bidirectional"))
    )
    (net (code "200") (name "Net-(U98-CO)") (class "Default")
      (node (ref "U98") (pin "CKO") (pinfunction "CO_CKO") (pintype "bidirectional"))
      (node (ref "U99") (pin "CKI") (pinfunction "CI_CKI") (pintype "bidirectional"))
    )
    (net (code "201") (name "Net-(U98-DO)") (class "Default")
      (node (ref "U98") (pin "SDO") (pinfunction "DO_SDO") (pintype "bidirectional"))
      (node (ref "U99") (pin "SDI") (pinfunction "DI_SDI") (pintype "bidirectional"))
    )
    (net (code "202") (name "Net-(U100-CI)") (class "Default")
      (node (ref "U100") (pin "CKI") (pinfunction "CI_CKI") (pintype "bidirectional"))
      (node (ref "U99") (pin "CKO") (pinfunction "CO_CKO") (pintype "bidirectional"))
    )
    (net (code "203") (name "Net-(U100-CO)") (class "Default")
      (node (ref "U100") (pin "CKO") (pinfunction "CO_CKO") (pintype "bidirectional"))
      (node (ref "U101") (pin "CKI") (pinfunction "CI_CKI") (pintype "bidirectional"))
    )
    (net (code "204") (name "Net-(U100-DI)") (class "Default")
      (node (ref "U100") (pin "SDI") (pinfunction "DI_SDI") (pintype "bidirectional"))
      (node (ref "U99") (pin "SDO") (pinfunction "DO_SDO") (pintype "bidirectional"))
    )
    (net (code "205") (name "Net-(U100-DO)") (class "Default")
      (node (ref "U100") (pin "SDO") (pinfunction "DO_SDO") (pintype "bidirectional"))
      (node (ref "U101") (pin "SDI") (pinfunction "DI_SDI") (pintype "bidirectional"))
    )
    (net (code "206") (name "Net-(U101-CO)") (class "Default")
      (node (ref "U101") (pin "CKO") (pinfunction "CO_CKO") (pintype "bidirectional"))
      (node (ref "U102") (pin "CKI") (pinfunction "CI_CKI") (pintype "bidirectional"))
    )
    (net (code "207") (name "Net-(U101-DO)") (class "Default")
      (node (ref "U101") (pin "SDO") (pinfunction "DO_SDO") (pintype "bidirectional"))
      (node (ref "U102") (pin "SDI") (pinfunction "DI_SDI") (pintype "bidirectional"))
    )
    (net (code "208") (name "Net-(U102-CO)") (class "Default")
      (node (ref "U102") (pin "CKO") (pinfunction "CO_CKO") (pintype "bidirectional"))
      (node (ref "U103") (pin "CKI") (pinfunction "CI_CKI") (pintype "bidirectional"))
    )
    (net (code "209") (name "Net-(U102-DO)") (class "Default")
      (node (ref "U102") (pin "SDO") (pinfunction "DO_SDO") (pintype "bidirectional"))
      (node (ref "U103") (pin "SDI") (pinfunction "DI_SDI") (pintype "bidirectional"))
    )
    (net (code "210") (name "Net-(U103-CO)") (class "Default")
      (node (ref "U103") (pin "CKO") (pinfunction "CO_CKO") (pintype "bidirectional"))
      (node (ref "U104") (pin "CKI") (pinfunction "CI_CKI") (pintype "bidirectional"))
    )
    (net (code "211") (name "Net-(U103-DO)") (class "Default")
      (node (ref "U103") (pin "SDO") (pinfunction "DO_SDO") (pintype "bidirectional"))
      (node (ref "U104") (pin "SDI") (pinfunction "DI_SDI") (pintype "bidirectional"))
    )
    (net (code "212") (name "Net-(U104-CO)") (class "Default")
      (node (ref "U104") (pin "CKO") (pinfunction "CO_CKO") (pintype "bidirectional"))
      (node (ref "U105") (pin "CKI") (pinfunction "CI_CKI") (pintype "bidirectional"))
    )
    (net (code "213") (name "Net-(U104-DO)") (class "Default")
      (node (ref "U104") (pin "SDO") (pinfunction "DO_SDO") (pintype "bidirectional"))
      (node (ref "U105") (pin "SDI") (pinfunction "DI_SDI") (pintype "bidirectional"))
    )
    (net (code "214") (name "Net-(U105-CO)") (class "Default")
      (node (ref "U105") (pin "CKO") (pinfunction "CO_CKO") (pintype "bidirectional"))
      (node (ref "U106") (pin "CKI") (pinfunction "CI_CKI") (pintype "bidirectional"))
    )
    (net (code "215") (name "Net-(U105-DO)") (class "Default")
      (node (ref "U105") (pin "SDO") (pinfunction "DO_SDO") (pintype "bidirectional"))
      (node (ref "U106") (pin "SDI") (pinfunction "DI_SDI") (pintype "bidirectional"))
    )
    (net (code "216") (name "Net-(U106-CO)") (class "Default")
      (node (ref "U106") (pin "CKO") (pinfunction "CO_CKO") (pintype "bidirectional"))
      (node (ref "U107") (pin "CKI") (pinfunction "CI_CKI") (pintype "bidirectional"))
    )
    (net (code "217") (name "Net-(U106-DO)") (class "Default")
      (node (ref "U106") (pin "SDO") (pinfunction "DO_SDO") (pintype "bidirectional"))
      (node (ref "U107") (pin "SDI") (pinfunction "DI_SDI") (pintype "bidirectional"))
    )
    (net (code "218") (name "Net-(U107-CO)") (class "Default")
      (node (ref "U107") (pin "CKO") (pinfunction "CO_CKO") (pintype "bidirectional"))
      (node (ref "U108") (pin "CKI") (pinfunction "CI_CKI") (pintype "bidirectional"))
    )
    (net (code "219") (name "Net-(U107-DO)") (class "Default")
      (node (ref "U107") (pin "SDO") (pinfunction "DO_SDO") (pintype "bidirectional"))
      (node (ref "U108") (pin "SDI") (pinfunction "DI_SDI") (pintype "bidirectional"))
    )
    (net (code "220") (name "Net-(U108-CO)") (class "Default")
      (node (ref "U108") (pin "CKO") (pinfunction "CO_CKO") (pintype "bidirectional"))
      (node (ref "U109") (pin "CKI") (pinfunction "CI_CKI") (pintype "bidirectional"))
    )
    (net (code "221") (name "Net-(U108-DO)") (class "Default")
      (node (ref "U108") (pin "SDO") (pinfunction "DO_SDO") (pintype "bidirectional"))
      (node (ref "U109") (pin "SDI") (pinfunction "DI_SDI") (pintype "bidirectional"))
    )
    (net (code "222") (name "Net-(U109-CO)") (class "Default")
      (node (ref "U109") (pin "CKO") (pinfunction "CO_CKO") (pintype "bidirectional"))
      (node (ref "U110") (pin "CKI") (pinfunction "CI_CKI") (pintype "bidirectional"))
    )
    (net (code "223") (name "Net-(U109-DO)") (class "Default")
      (node (ref "U109") (pin "SDO") (pinfunction "DO_SDO") (pintype "bidirectional"))
      (node (ref "U110") (pin "SDI") (pinfunction "DI_SDI") (pintype "bidirectional"))
    )
    (net (code "224") (name "Net-(U110-CO)") (class "Default")
      (node (ref "U110") (pin "CKO") (pinfunction "CO_CKO") (pintype "bidirectional"))
      (node (ref "U111") (pin "CKI") (pinfunction "CI_CKI") (pintype "bidirectional"))
    )
    (net (code "225") (name "Net-(U110-DO)") (class "Default")
      (node (ref "U110") (pin "SDO") (pinfunction "DO_SDO") (pintype "bidirectional"))
      (node (ref "U111") (pin "SDI") (pinfunction "DI_SDI") (pintype "bidirectional"))
    )
    (net (code "226") (name "Net-(U111-CO)") (class "Default")
      (node (ref "U111") (pin "CKO") (pinfunction "CO_CKO") (pintype "bidirectional"))
      (node (ref "U112") (pin "CKI") (pinfunction "CI_CKI") (pintype "bidirectional"))
    )
    (net (code "227") (name "Net-(U111-DO)") (class "Default")
      (node (ref "U111") (pin "SDO") (pinfunction "DO_SDO") (pintype "bidirectional"))
      (node (ref "U112") (pin "SDI") (pinfunction "DI_SDI") (pintype "bidirectional"))
    )
    (net (code "228") (name "Net-(U113-CO)") (class "Default")
      (node (ref "U113") (pin "CKO") (pinfunction "CO_CKO") (pintype "bidirectional"))
      (node (ref "U114") (pin "CKI") (pinfunction "CI_CKI") (pintype "bidirectional"))
    )
    (net (code "229") (name "Net-(U113-DO)") (class "Default")
      (node (ref "U113") (pin "SDO") (pinfunction "DO_SDO") (pintype "bidirectional"))
      (node (ref "U114") (pin "SDI") (pinfunction "DI_SDI") (pintype "bidirectional"))
    )
    (net (code "230") (name "Net-(U114-CO)") (class "Default")
      (node (ref "U114") (pin "CKO") (pinfunction "CO_CKO") (pintype "bidirectional"))
      (node (ref "U115") (pin "CKI") (pinfunction "CI_CKI") (pintype "bidirectional"))
    )
    (net (code "231") (name "Net-(U114-DO)") (class "Default")
      (node (ref "U114") (pin "SDO") (pinfunction "DO_SDO") (pintype "bidirectional"))
      (node (ref "U115") (pin "SDI") (pinfunction "DI_SDI") (pintype "bidirectional"))
    )
    (net (code "232") (name "Net-(U115-CO)") (class "Default")
      (node (ref "U115") (pin "CKO") (pinfunction "CO_CKO") (pintype "bidirectional"))
      (node (ref "U116") (pin "CKI") (pinfunction "CI_CKI") (pintype "bidirectional"))
    )
    (net (code "233") (name "Net-(U115-DO)") (class "Default")
      (node (ref "U115") (pin "SDO") (pinfunction "DO_SDO") (pintype "bidirectional"))
      (node (ref "U116") (pin "SDI") (pinfunction "DI_SDI") (pintype "bidirectional"))
    )
    (net (code "234") (name "Net-(U116-CO)") (class "Default")
      (node (ref "U116") (pin "CKO") (pinfunction "CO_CKO") (pintype "bidirectional"))
      (node (ref "U117") (pin "CKI") (pinfunction "CI_CKI") (pintype "bidirectional"))
    )
    (net (code "235") (name "Net-(U116-DO)") (class "Default")
      (node (ref "U116") (pin "SDO") (pinfunction "DO_SDO") (pintype "bidirectional"))
      (node (ref "U117") (pin "SDI") (pinfunction "DI_SDI") (pintype "bidirectional"))
    )
    (net (code "236") (name "Net-(U117-CO)") (class "Default")
      (node (ref "U117") (pin "CKO") (pinfunction "CO_CKO") (pintype "bidirectional"))
      (node (ref "U118") (pin "CKI") (pinfunction "CI_CKI") (pintype "bidirectional"))
    )
    (net (code "237") (name "Net-(U117-DO)") (class "Default")
      (node (ref "U117") (pin "SDO") (pinfunction "DO_SDO") (pintype "bidirectional"))
      (node (ref "U118") (pin "SDI") (pinfunction "DI_SDI") (pintype "bidirectional"))
    )
    (net (code "238") (name "Net-(U118-CO)") (class "Default")
      (node (ref "U118") (pin "CKO") (pinfunction "CO_CKO") (pintype "bidirectional"))
      (node (ref "U119") (pin "CKI") (pinfunction "CI_CKI") (pintype "bidirectional"))
    )
    (net (code "239") (name "Net-(U118-DO)") (class "Default")
      (node (ref "U118") (pin "SDO") (pinfunction "DO_SDO") (pintype "bidirectional"))
      (node (ref "U119") (pin "SDI") (pinfunction "DI_SDI") (pintype "bidirectional"))
    )
    (net (code "240") (name "Net-(U119-CO)") (class "Default")
      (node (ref "U119") (pin "CKO") (pinfunction "CO_CKO") (pintype "bidirectional"))
      (node (ref "U120") (pin "CKI") (pinfunction "CI_CKI") (pintype "bidirectional"))
    )
    (net (code "241") (name "Net-(U119-DO)") (class "Default")
      (node (ref "U119") (pin "SDO") (pinfunction "DO_SDO") (pintype "bidirectional"))
      (node (ref "U120") (pin "SDI") (pinfunction "DI_SDI") (pintype "bidirectional"))
    )
    (net (code "242") (name "Net-(U120-CO)") (class "Default")
      (node (ref "U120") (pin "CKO") (pinfunction "CO_CKO") (pintype "bidirectional"))
      (node (ref "U121") (pin "CKI") (pinfunction "CI_CKI") (pintype "bidirectional"))
    )
    (net (code "243") (name "Net-(U120-DO)") (class "Default")
      (node (ref "U120") (pin "SDO") (pinfunction "DO_SDO") (pintype "bidirectional"))
      (node (ref "U121") (pin "SDI") (pinfunction "DI_SDI") (pintype "bidirectional"))
    )
    (net (code "244") (name "Net-(U121-CO)") (class "Default")
      (node (ref "U121") (pin "CKO") (pinfunction "CO_CKO") (pintype "bidirectional"))
      (node (ref "U122") (pin "CKI") (pinfunction "CI_CKI") (pintype "bidirectional"))
    )
    (net (code "245") (name "Net-(U121-DO)") (class "Default")
      (node (ref "U121") (pin "SDO") (pinfunction "DO_SDO") (pintype "bidirectional"))
      (node (ref "U122") (pin "SDI") (pinfunction "DI_SDI") (pintype "bidirectional"))
    )
    (net (code "246") (name "Net-(U122-CO)") (class "Default")
      (node (ref "U122") (pin "CKO") (pinfunction "CO_CKO") (pintype "bidirectional"))
      (node (ref "U123") (pin "CKI") (pinfunction "CI_CKI") (pintype "bidirectional"))
    )
    (net (code "247") (name "Net-(U122-DO)") (class "Default")
      (node (ref "U122") (pin "SDO") (pinfunction "DO_SDO") (pintype "bidirectional"))
      (node (ref "U123") (pin "SDI") (pinfunction "DI_SDI") (pintype "bidirectional"))
    )
    (net (code "248") (name "Net-(U123-CO)") (class "Default")
      (node (ref "U123") (pin "CKO") (pinfunction "CO_CKO") (pintype "bidirectional"))
      (node (ref "U124") (pin "CKI") (pinfunction "CI_CKI") (pintype "bidirectional"))
    )
    (net (code "249") (name "Net-(U123-DO)") (class "Default")
      (node (ref "U123") (pin "SDO") (pinfunction "DO_SDO") (pintype "bidirectional"))
      (node (ref "U124") (pin "SDI") (pinfunction "DI_SDI") (pintype "bidirectional"))
    )
    (net (code "250") (name "Net-(U124-CO)") (class "Default")
      (node (ref "U124") (pin "CKO") (pinfunction "CO_CKO") (pintype "bidirectional"))
      (node (ref "U125") (pin "CKI") (pinfunction "CI_CKI") (pintype "bidirectional"))
    )
    (net (code "251") (name "Net-(U124-DO)") (class "Default")
      (node (ref "U124") (pin "SDO") (pinfunction "DO_SDO") (pintype "bidirectional"))
      (node (ref "U125") (pin "SDI") (pinfunction "DI_SDI") (pintype "bidirectional"))
    )
    (net (code "252") (name "Net-(U125-CO)") (class "Default")
      (node (ref "U125") (pin "CKO") (pinfunction "CO_CKO") (pintype "bidirectional"))
      (node (ref "U126") (pin "CKI") (pinfunction "CI_CKI") (pintype "bidirectional"))
    )
    (net (code "253") (name "Net-(U125-DO)") (class "Default")
      (node (ref "U125") (pin "SDO") (pinfunction "DO_SDO") (pintype "bidirectional"))
      (node (ref "U126") (pin "SDI") (pinfunction "DI_SDI") (pintype "bidirectional"))
    )
    (net (code "254") (name "Net-(U127-CI)") (class "Default")
      (node (ref "J1") (pin "4") (pinfunction "4_4") (pintype "passive"))
      (node (ref "U127") (pin "CKI") (pinfunction "CI_CKI") (pintype "bidirectional"))
    )
    (net (code "255") (name "Net-(U127-CO)") (class "Default")
      (node (ref "U127") (pin "CKO") (pinfunction "CO_CKO") (pintype "bidirectional"))
      (node (ref "U128") (pin "CKI") (pinfunction "CI_CKI") (pintype "bidirectional"))
    )
    (net (code "256") (name "Net-(U127-DI)") (class "Default")
      (node (ref "J1") (pin "3") (pinfunction "3_3") (pintype "passive"))
      (node (ref "U127") (pin "SDI") (pinfunction "DI_SDI") (pintype "bidirectional"))
    )
    (net (code "257") (name "Net-(U127-DO)") (class "Default")
      (node (ref "U127") (pin "SDO") (pinfunction "DO_SDO") (pintype "bidirectional"))
      (node (ref "U128") (pin "SDI") (pinfunction "DI_SDI") (pintype "bidirectional"))
    )
    (net (code "258") (name "Net-(U128-CO)") (class "Default")
      (node (ref "U128") (pin "CKO") (pinfunction "CO_CKO") (pintype "bidirectional"))
      (node (ref "U129") (pin "CKI") (pinfunction "CI_CKI") (pintype "bidirectional"))
    )
    (net (code "259") (name "Net-(U128-DO)") (class "Default")
      (node (ref "U128") (pin "SDO") (pinfunction "DO_SDO") (pintype "bidirectional"))
      (node (ref "U129") (pin "SDI") (pinfunction "DI_SDI") (pintype "bidirectional"))
    )
    (net (code "260") (name "Net-(U129-CO)") (class "Default")
      (node (ref "U129") (pin "CKO") (pinfunction "CO_CKO") (pintype "bidirectional"))
      (node (ref "U130") (pin "CKI") (pinfunction "CI_CKI") (pintype "bidirectional"))
    )
    (net (code "261") (name "Net-(U129-DO)") (class "Default")
      (node (ref "U129") (pin "SDO") (pinfunction "DO_SDO") (pintype "bidirectional"))
      (node (ref "U130") (pin "SDI") (pinfunction "DI_SDI") (pintype "bidirectional"))
    )
    (net (code "262") (name "Net-(U130-CO)") (class "Default")
      (node (ref "U130") (pin "CKO") (pinfunction "CO_CKO") (pintype "bidirectional"))
      (node (ref "U131") (pin "CKI") (pinfunction "CI_CKI") (pintype "bidirectional"))
    )
    (net (code "263") (name "Net-(U130-DO)") (class "Default")
      (node (ref "U130") (pin "SDO") (pinfunction "DO_SDO") (pintype "bidirectional"))
      (node (ref "U131") (pin "SDI") (pinfunction "DI_SDI") (pintype "bidirectional"))
    )
    (net (code "264") (name "Net-(U131-CO)") (class "Default")
      (node (ref "U131") (pin "CKO") (pinfunction "CO_CKO") (pintype "bidirectional"))
      (node (ref "U132") (pin "CKI") (pinfunction "CI_CKI") (pintype "bidirectional"))
    )
    (net (code "265") (name "Net-(U131-DO)") (class "Default")
      (node (ref "U131") (pin "SDO") (pinfunction "DO_SDO") (pintype "bidirectional"))
      (node (ref "U132") (pin "SDI") (pinfunction "DI_SDI") (pintype "bidirectional"))
    )
    (net (code "266") (name "Net-(U132-CO)") (class "Default")
      (node (ref "U132") (pin "CKO") (pinfunction "CO_CKO") (pintype "bidirectional"))
      (node (ref "U133") (pin "CKI") (pinfunction "CI_CKI") (pintype "bidirectional"))
    )
    (net (code "267") (name "Net-(U132-DO)") (class "Default")
      (node (ref "U132") (pin "SDO") (pinfunction "DO_SDO") (pintype "bidirectional"))
      (node (ref "U133") (pin "SDI") (pinfunction "DI_SDI") (pintype "bidirectional"))
    )
    (net (code "268") (name "Net-(U133-CO)") (class "Default")
      (node (ref "U133") (pin "CKO") (pinfunction "CO_CKO") (pintype "bidirectional"))
      (node (ref "U134") (pin "CKI") (pinfunction "CI_CKI") (pintype "bidirectional"))
    )
    (net (code "269") (name "Net-(U133-DO)") (class "Default")
      (node (ref "U133") (pin "SDO") (pinfunction "DO_SDO") (pintype "bidirectional"))
      (node (ref "U134") (pin "SDI") (pinfunction "DI_SDI") (pintype "bidirectional"))
    )
    (net (code "270") (name "Net-(U134-CO)") (class "Default")
      (node (ref "U134") (pin "CKO") (pinfunction "CO_CKO") (pintype "bidirectional"))
      (node (ref "U135") (pin "CKI") (pinfunction "CI_CKI") (pintype "bidirectional"))
    )
    (net (code "271") (name "Net-(U134-DO)") (class "Default")
      (node (ref "U134") (pin "SDO") (pinfunction "DO_SDO") (pintype "bidirectional"))
      (node (ref "U135") (pin "SDI") (pinfunction "DI_SDI") (pintype "bidirectional"))
    )
    (net (code "272") (name "Net-(U135-CO)") (class "Default")
      (node (ref "U135") (pin "CKO") (pinfunction "CO_CKO") (pintype "bidirectional"))
      (node (ref "U136") (pin "CKI") (pinfunction "CI_CKI") (pintype "bidirectional"))
    )
    (net (code "273") (name "Net-(U135-DO)") (class "Default")
      (node (ref "U135") (pin "SDO") (pinfunction "DO_SDO") (pintype "bidirectional"))
      (node (ref "U136") (pin "SDI") (pinfunction "DI_SDI") (pintype "bidirectional"))
    )
    (net (code "274") (name "Net-(U136-CO)") (class "Default")
      (node (ref "U136") (pin "CKO") (pinfunction "CO_CKO") (pintype "bidirectional"))
      (node (ref "U137") (pin "CKI") (pinfunction "CI_CKI") (pintype "bidirectional"))
    )
    (net (code "275") (name "Net-(U136-DO)") (class "Default")
      (node (ref "U136") (pin "SDO") (pinfunction "DO_SDO") (pintype "bidirectional"))
      (node (ref "U137") (pin "SDI") (pinfunction "DI_SDI") (pintype "bidirectional"))
    )
    (net (code "276") (name "Net-(U137-CO)") (class "Default")
      (node (ref "U137") (pin "CKO") (pinfunction "CO_CKO") (pintype "bidirectional"))
      (node (ref "U138") (pin "CKI") (pinfunction "CI_CKI") (pintype "bidirectional"))
    )
    (net (code "277") (name "Net-(U137-DO)") (class "Default")
      (node (ref "U137") (pin "SDO") (pinfunction "DO_SDO") (pintype "bidirectional"))
      (node (ref "U138") (pin "SDI") (pinfunction "DI_SDI") (pintype "bidirectional"))
    )
    (net (code "278") (name "Net-(U138-CO)") (class "Default")
      (node (ref "U138") (pin "CKO") (pinfunction "CO_CKO") (pintype "bidirectional"))
      (node (ref "U139") (pin "CKI") (pinfunction "CI_CKI") (pintype "bidirectional"))
    )
    (net (code "279") (name "Net-(U138-DO)") (class "Default")
      (node (ref "U138") (pin "SDO") (pinfunction "DO_SDO") (pintype "bidirectional"))
      (node (ref "U139") (pin "SDI") (pinfunction "DI_SDI") (pintype "bidirectional"))
    )
    (net (code "280") (name "Net-(U139-CO)") (class "Default")
      (node (ref "U139") (pin "CKO") (pinfunction "CO_CKO") (pintype "bidirectional"))
      (node (ref "U140") (pin "CKI") (pinfunction "CI_CKI") (pintype "bidirectional"))
    )
    (net (code "281") (name "Net-(U139-DO)") (class "Default")
      (node (ref "U139") (pin "SDO") (pinfunction "DO_SDO") (pintype "bidirectional"))
      (node (ref "U140") (pin "SDI") (pinfunction "DI_SDI") (pintype "bidirectional"))
    )
    (net (code "282") (name "Net-(U141-CO)") (class "Default")
      (node (ref "U141") (pin "CKO") (pinfunction "CO_CKO") (pintype "bidirectional"))
      (node (ref "U142") (pin "CKI") (pinfunction "CI_CKI") (pintype "bidirectional"))
    )
    (net (code "283") (name "Net-(U141-DO)") (class "Default")
      (node (ref "U141") (pin "SDO") (pinfunction "DO_SDO") (pintype "bidirectional"))
      (node (ref "U142") (pin "SDI") (pinfunction "DI_SDI") (pintype "bidirectional"))
    )
    (net (code "284") (name "Net-(U142-CO)") (class "Default")
      (node (ref "U142") (pin "CKO") (pinfunction "CO_CKO") (pintype "bidirectional"))
      (node (ref "U143") (pin "CKI") (pinfunction "CI_CKI") (pintype "bidirectional"))
    )
    (net (code "285") (name "Net-(U142-DO)") (class "Default")
      (node (ref "U142") (pin "SDO") (pinfunction "DO_SDO") (pintype "bidirectional"))
      (node (ref "U143") (pin "SDI") (pinfunction "DI_SDI") (pintype "bidirectional"))
    )
    (net (code "286") (name "Net-(U143-CO)") (class "Default")
      (node (ref "U143") (pin "CKO") (pinfunction "CO_CKO") (pintype "bidirectional"))
      (node (ref "U144") (pin "CKI") (pinfunction "CI_CKI") (pintype "bidirectional"))
    )
    (net (code "287") (name "Net-(U143-DO)") (class "Default")
      (node (ref "U143") (pin "SDO") (pinfunction "DO_SDO") (pintype "bidirectional"))
      (node (ref "U144") (pin "SDI") (pinfunction "DI_SDI") (pintype "bidirectional"))
    )
    (net (code "288") (name "Net-(U144-CO)") (class "Default")
      (node (ref "U144") (pin "CKO") (pinfunction "CO_CKO") (pintype "bidirectional"))
      (node (ref "U145") (pin "CKI") (pinfunction "CI_CKI") (pintype "bidirectional"))
    )
    (net (code "289") (name "Net-(U144-DO)") (class "Default")
      (node (ref "U144") (pin "SDO") (pinfunction "DO_SDO") (pintype "bidirectional"))
      (node (ref "U145") (pin "SDI") (pinfunction "DI_SDI") (pintype "bidirectional"))
    )
    (net (code "290") (name "Net-(U145-CO)") (class "Default")
      (node (ref "U145") (pin "CKO") (pinfunction "CO_CKO") (pintype "bidirectional"))
      (node (ref "U146") (pin "CKI") (pinfunction "CI_CKI") (pintype "bidirectional"))
    )
    (net (code "291") (name "Net-(U145-DO)") (class "Default")
      (node (ref "U145") (pin "SDO") (pinfunction "DO_SDO") (pintype "bidirectional"))
      (node (ref "U146") (pin "SDI") (pinfunction "DI_SDI") (pintype "bidirectional"))
    )
    (net (code "292") (name "Net-(U146-CO)") (class "Default")
      (node (ref "U146") (pin "CKO") (pinfunction "CO_CKO") (pintype "bidirectional"))
      (node (ref "U147") (pin "CKI") (pinfunction "CI_CKI") (pintype "bidirectional"))
    )
    (net (code "293") (name "Net-(U146-DO)") (class "Default")
      (node (ref "U146") (pin "SDO") (pinfunction "DO_SDO") (pintype "bidirectional"))
      (node (ref "U147") (pin "SDI") (pinfunction "DI_SDI") (pintype "bidirectional"))
    )
    (net (code "294") (name "Net-(U147-CO)") (class "Default")
      (node (ref "U147") (pin "CKO") (pinfunction "CO_CKO") (pintype "bidirectional"))
      (node (ref "U148") (pin "CKI") (pinfunction "CI_CKI") (pintype "bidirectional"))
    )
    (net (code "295") (name "Net-(U147-DO)") (class "Default")
      (node (ref "U147") (pin "SDO") (pinfunction "DO_SDO") (pintype "bidirectional"))
      (node (ref "U148") (pin "SDI") (pinfunction "DI_SDI") (pintype "bidirectional"))
    )
    (net (code "296") (name "Net-(U148-CO)") (class "Default")
      (node (ref "U148") (pin "CKO") (pinfunction "CO_CKO") (pintype "bidirectional"))
      (node (ref "U149") (pin "CKI") (pinfunction "CI_CKI") (pintype "bidirectional"))
    )
    (net (code "297") (name "Net-(U148-DO)") (class "Default")
      (node (ref "U148") (pin "SDO") (pinfunction "DO_SDO") (pintype "bidirectional"))
      (node (ref "U149") (pin "SDI") (pinfunction "DI_SDI") (pintype "bidirectional"))
    )
    (net (code "298") (name "Net-(U149-CO)") (class "Default")
      (node (ref "U149") (pin "CKO") (pinfunction "CO_CKO") (pintype "bidirectional"))
      (node (ref "U150") (pin "CKI") (pinfunction "CI_CKI") (pintype "bidirectional"))
    )
    (net (code "299") (name "Net-(U149-DO)") (class "Default")
      (node (ref "U149") (pin "SDO") (pinfunction "DO_SDO") (pintype "bidirectional"))
      (node (ref "U150") (pin "SDI") (pinfunction "DI_SDI") (pintype "bidirectional"))
    )
    (net (code "300") (name "Net-(U150-CO)") (class "Default")
      (node (ref "U150") (pin "CKO") (pinfunction "CO_CKO") (pintype "bidirectional"))
      (node (ref "U151") (pin "CKI") (pinfunction "CI_CKI") (pintype "bidirectional"))
    )
    (net (code "301") (name "Net-(U150-DO)") (class "Default")
      (node (ref "U150") (pin "SDO") (pinfunction "DO_SDO") (pintype "bidirectional"))
      (node (ref "U151") (pin "SDI") (pinfunction "DI_SDI") (pintype "bidirectional"))
    )
    (net (code "302") (name "Net-(U151-CO)") (class "Default")
      (node (ref "U151") (pin "CKO") (pinfunction "CO_CKO") (pintype "bidirectional"))
      (node (ref "U152") (pin "CKI") (pinfunction "CI_CKI") (pintype "bidirectional"))
    )
    (net (code "303") (name "Net-(U151-DO)") (class "Default")
      (node (ref "U151") (pin "SDO") (pinfunction "DO_SDO") (pintype "bidirectional"))
      (node (ref "U152") (pin "SDI") (pinfunction "DI_SDI") (pintype "bidirectional"))
    )
    (net (code "304") (name "Net-(U152-CO)") (class "Default")
      (node (ref "U152") (pin "CKO") (pinfunction "CO_CKO") (pintype "bidirectional"))
      (node (ref "U153") (pin "CKI") (pinfunction "CI_CKI") (pintype "bidirectional"))
    )
    (net (code "305") (name "Net-(U152-DO)") (class "Default")
      (node (ref "U152") (pin "SDO") (pinfunction "DO_SDO") (pintype "bidirectional"))
      (node (ref "U153") (pin "SDI") (pinfunction "DI_SDI") (pintype "bidirectional"))
    )
    (net (code "306") (name "Net-(U153-CO)") (class "Default")
      (node (ref "U153") (pin "CKO") (pinfunction "CO_CKO") (pintype "bidirectional"))
      (node (ref "U154") (pin "CKI") (pinfunction "CI_CKI") (pintype "bidirectional"))
    )
    (net (code "307") (name "Net-(U153-DO)") (class "Default")
      (node (ref "U153") (pin "SDO") (pinfunction "DO_SDO") (pintype "bidirectional"))
      (node (ref "U154") (pin "SDI") (pinfunction "DI_SDI") (pintype "bidirectional"))
    )
    (net (code "308") (name "Net-(U154-CO)") (class "Default")
      (node (ref "U154") (pin "CKO") (pinfunction "CO_CKO") (pintype "bidirectional"))
      (node (ref "U155") (pin "CKI") (pinfunction "CI_CKI") (pintype "bidirectional"))
    )
    (net (code "309") (name "Net-(U154-DO)") (class "Default")
      (node (ref "U154") (pin "SDO") (pinfunction "DO_SDO") (pintype "bidirectional"))
      (node (ref "U155") (pin "SDI") (pinfunction "DI_SDI") (pintype "bidirectional"))
    )
    (net (code "310") (name "Net-(U155-CO)") (class "Default")
      (node (ref "U155") (pin "CKO") (pinfunction "CO_CKO") (pintype "bidirectional"))
      (node (ref "U156") (pin "CKI") (pinfunction "CI_CKI") (pintype "bidirectional"))
    )
    (net (code "311") (name "Net-(U155-DO)") (class "Default")
      (node (ref "U155") (pin "SDO") (pinfunction "DO_SDO") (pintype "bidirectional"))
      (node (ref "U156") (pin "SDI") (pinfunction "DI_SDI") (pintype "bidirectional"))
    )
    (net (code "312") (name "Net-(U156-CO)") (class "Default")
      (node (ref "U156") (pin "CKO") (pinfunction "CO_CKO") (pintype "bidirectional"))
      (node (ref "U157") (pin "CKI") (pinfunction "CI_CKI") (pintype "bidirectional"))
    )
    (net (code "313") (name "Net-(U156-DO)") (class "Default")
      (node (ref "U156") (pin "SDO") (pinfunction "DO_SDO") (pintype "bidirectional"))
      (node (ref "U157") (pin "SDI") (pinfunction "DI_SDI") (pintype "bidirectional"))
    )
    (net (code "314") (name "Net-(U157-CO)") (class "Default")
      (node (ref "U157") (pin "CKO") (pinfunction "CO_CKO") (pintype "bidirectional"))
      (node (ref "U158") (pin "CKI") (pinfunction "CI_CKI") (pintype "bidirectional"))
    )
    (net (code "315") (name "Net-(U157-DO)") (class "Default")
      (node (ref "U157") (pin "SDO") (pinfunction "DO_SDO") (pintype "bidirectional"))
      (node (ref "U158") (pin "SDI") (pinfunction "DI_SDI") (pintype "bidirectional"))
    )
    (net (code "316") (name "Net-(U158-CO)") (class "Default")
      (node (ref "U158") (pin "CKO") (pinfunction "CO_CKO") (pintype "bidirectional"))
      (node (ref "U159") (pin "CKI") (pinfunction "CI_CKI") (pintype "bidirectional"))
    )
    (net (code "317") (name "Net-(U158-DO)") (class "Default")
      (node (ref "U158") (pin "SDO") (pinfunction "DO_SDO") (pintype "bidirectional"))
      (node (ref "U159") (pin "SDI") (pinfunction "DI_SDI") (pintype "bidirectional"))
    )
    (net (code "318") (name "Net-(U159-CO)") (class "Default")
      (node (ref "U159") (pin "CKO") (pinfunction "CO_CKO") (pintype "bidirectional"))
      (node (ref "U160") (pin "CKI") (pinfunction "CI_CKI") (pintype "bidirectional"))
    )
    (net (code "319") (name "Net-(U159-DO)") (class "Default")
      (node (ref "U159") (pin "SDO") (pinfunction "DO_SDO") (pintype "bidirectional"))
      (node (ref "U160") (pin "SDI") (pinfunction "DI_SDI") (pintype "bidirectional"))
    )
    (net (code "320") (name "Net-(U160-CO)") (class "Default")
      (node (ref "U160") (pin "CKO") (pinfunction "CO_CKO") (pintype "bidirectional"))
      (node (ref "U161") (pin "CKI") (pinfunction "CI_CKI") (pintype "bidirectional"))
    )
    (net (code "321") (name "Net-(U160-DO)") (class "Default")
      (node (ref "U160") (pin "SDO") (pinfunction "DO_SDO") (pintype "bidirectional"))
      (node (ref "U161") (pin "SDI") (pinfunction "DI_SDI") (pintype "bidirectional"))
    )
    (net (code "322") (name "Net-(U161-CO)") (class "Default")
      (node (ref "U161") (pin "CKO") (pinfunction "CO_CKO") (pintype "bidirectional"))
      (node (ref "U162") (pin "CKI") (pinfunction "CI_CKI") (pintype "bidirectional"))
    )
    (net (code "323") (name "Net-(U161-DO)") (class "Default")
      (node (ref "U161") (pin "SDO") (pinfunction "DO_SDO") (pintype "bidirectional"))
      (node (ref "U162") (pin "SDI") (pinfunction "DI_SDI") (pintype "bidirectional"))
    )
    (net (code "324") (name "Net-(U162-CO)") (class "Default")
      (node (ref "U162") (pin "CKO") (pinfunction "CO_CKO") (pintype "bidirectional"))
      (node (ref "U163") (pin "CKI") (pinfunction "CI_CKI") (pintype "bidirectional"))
    )
    (net (code "325") (name "Net-(U162-DO)") (class "Default")
      (node (ref "U162") (pin "SDO") (pinfunction "DO_SDO") (pintype "bidirectional"))
      (node (ref "U163") (pin "SDI") (pinfunction "DI_SDI") (pintype "bidirectional"))
    )
    (net (code "326") (name "Net-(U163-CO)") (class "Default")
      (node (ref "U163") (pin "CKO") (pinfunction "CO_CKO") (pintype "bidirectional"))
      (node (ref "U164") (pin "CKI") (pinfunction "CI_CKI") (pintype "bidirectional"))
    )
    (net (code "327") (name "Net-(U163-DO)") (class "Default")
      (node (ref "U163") (pin "SDO") (pinfunction "DO_SDO") (pintype "bidirectional"))
      (node (ref "U164") (pin "SDI") (pinfunction "DI_SDI") (pintype "bidirectional"))
    )
    (net (code "328") (name "Net-(U164-CO)") (class "Default")
      (node (ref "U164") (pin "CKO") (pinfunction "CO_CKO") (pintype "bidirectional"))
      (node (ref "U165") (pin "CKI") (pinfunction "CI_CKI") (pintype "bidirectional"))
    )
    (net (code "329") (name "Net-(U164-DO)") (class "Default")
      (node (ref "U164") (pin "SDO") (pinfunction "DO_SDO") (pintype "bidirectional"))
      (node (ref "U165") (pin "SDI") (pinfunction "DI_SDI") (pintype "bidirectional"))
    )
    (net (code "330") (name "Net-(U165-CO)") (class "Default")
      (node (ref "U165") (pin "CKO") (pinfunction "CO_CKO") (pintype "bidirectional"))
      (node (ref "U166") (pin "CKI") (pinfunction "CI_CKI") (pintype "bidirectional"))
    )
    (net (code "331") (name "Net-(U165-DO)") (class "Default")
      (node (ref "U165") (pin "SDO") (pinfunction "DO_SDO") (pintype "bidirectional"))
      (node (ref "U166") (pin "SDI") (pinfunction "DI_SDI") (pintype "bidirectional"))
    )
    (net (code "332") (name "Net-(U166-CO)") (class "Default")
      (node (ref "U166") (pin "CKO") (pinfunction "CO_CKO") (pintype "bidirectional"))
      (node (ref "U167") (pin "CKI") (pinfunction "CI_CKI") (pintype "bidirectional"))
    )
    (net (code "333") (name "Net-(U166-DO)") (class "Default")
      (node (ref "U166") (pin "SDO") (pinfunction "DO_SDO") (pintype "bidirectional"))
      (node (ref "U167") (pin "SDI") (pinfunction "DI_SDI") (pintype "bidirectional"))
    )
    (net (code "334") (name "Net-(U167-CO)") (class "Default")
      (node (ref "U167") (pin "CKO") (pinfunction "CO_CKO") (pintype "bidirectional"))
      (node (ref "U168") (pin "CKI") (pinfunction "CI_CKI") (pintype "bidirectional"))
    )
    (net (code "335") (name "Net-(U167-DO)") (class "Default")
      (node (ref "U167") (pin "SDO") (pinfunction "DO_SDO") (pintype "bidirectional"))
      (node (ref "U168") (pin "SDI") (pinfunction "DI_SDI") (pintype "bidirectional"))
    )
    (net (code "336") (name "Net-(U169-CO)") (class "Default")
      (node (ref "U169") (pin "CKO") (pinfunction "CO_CKO") (pintype "bidirectional"))
      (node (ref "U170") (pin "CKI") (pinfunction "CI_CKI") (pintype "bidirectional"))
    )
    (net (code "337") (name "Net-(U169-DO)") (class "Default")
      (node (ref "U169") (pin "SDO") (pinfunction "DO_SDO") (pintype "bidirectional"))
      (node (ref "U170") (pin "SDI") (pinfunction "DI_SDI") (pintype "bidirectional"))
    )
    (net (code "338") (name "Net-(U170-CO)") (class "Default")
      (node (ref "U170") (pin "CKO") (pinfunction "CO_CKO") (pintype "bidirectional"))
      (node (ref "U171") (pin "CKI") (pinfunction "CI_CKI") (pintype "bidirectional"))
    )
    (net (code "339") (name "Net-(U170-DO)") (class "Default")
      (node (ref "U170") (pin "SDO") (pinfunction "DO_SDO") (pintype "bidirectional"))
      (node (ref "U171") (pin "SDI") (pinfunction "DI_SDI") (pintype "bidirectional"))
    )
    (net (code "340") (name "Net-(U171-CO)") (class "Default")
      (node (ref "U171") (pin "CKO") (pinfunction "CO_CKO") (pintype "bidirectional"))
      (node (ref "U172") (pin "CKI") (pinfunction "CI_CKI") (pintype "bidirectional"))
    )
    (net (code "341") (name "Net-(U171-DO)") (class "Default")
      (node (ref "U171") (pin "SDO") (pinfunction "DO_SDO") (pintype "bidirectional"))
      (node (ref "U172") (pin "SDI") (pinfunction "DI_SDI") (pintype "bidirectional"))
    )
    (net (code "342") (name "Net-(U172-CO)") (class "Default")
      (node (ref "U172") (pin "CKO") (pinfunction "CO_CKO") (pintype "bidirectional"))
      (node (ref "U173") (pin "CKI") (pinfunction "CI_CKI") (pintype "bidirectional"))
    )
    (net (code "343") (name "Net-(U172-DO)") (class "Default")
      (node (ref "U172") (pin "SDO") (pinfunction "DO_SDO") (pintype "bidirectional"))
      (node (ref "U173") (pin "SDI") (pinfunction "DI_SDI") (pintype "bidirectional"))
    )
    (net (code "344") (name "Net-(U173-CO)") (class "Default")
      (node (ref "U173") (pin "CKO") (pinfunction "CO_CKO") (pintype "bidirectional"))
      (node (ref "U174") (pin "CKI") (pinfunction "CI_CKI") (pintype "bidirectional"))
    )
    (net (code "345") (name "Net-(U173-DO)") (class "Default")
      (node (ref "U173") (pin "SDO") (pinfunction "DO_SDO") (pintype "bidirectional"))
      (node (ref "U174") (pin "SDI") (pinfunction "DI_SDI") (pintype "bidirectional"))
    )
    (net (code "346") (name "Net-(U174-CO)") (class "Default")
      (node (ref "U174") (pin "CKO") (pinfunction "CO_CKO") (pintype "bidirectional"))
      (node (ref "U175") (pin "CKI") (pinfunction "CI_CKI") (pintype "bidirectional"))
    )
    (net (code "347") (name "Net-(U174-DO)") (class "Default")
      (node (ref "U174") (pin "SDO") (pinfunction "DO_SDO") (pintype "bidirectional"))
      (node (ref "U175") (pin "SDI") (pinfunction "DI_SDI") (pintype "bidirectional"))
    )
    (net (code "348") (name "Net-(U175-CO)") (class "Default")
      (node (ref "U175") (pin "CKO") (pinfunction "CO_CKO") (pintype "bidirectional"))
      (node (ref "U176") (pin "CKI") (pinfunction "CI_CKI") (pintype "bidirectional"))
    )
    (net (code "349") (name "Net-(U175-DO)") (class "Default")
      (node (ref "U175") (pin "SDO") (pinfunction "DO_SDO") (pintype "bidirectional"))
      (node (ref "U176") (pin "SDI") (pinfunction "DI_SDI") (pintype "bidirectional"))
    )
    (net (code "350") (name "Net-(U176-CO)") (class "Default")
      (node (ref "U176") (pin "CKO") (pinfunction "CO_CKO") (pintype "bidirectional"))
      (node (ref "U177") (pin "CKI") (pinfunction "CI_CKI") (pintype "bidirectional"))
    )
    (net (code "351") (name "Net-(U176-DO)") (class "Default")
      (node (ref "U176") (pin "SDO") (pinfunction "DO_SDO") (pintype "bidirectional"))
      (node (ref "U177") (pin "SDI") (pinfunction "DI_SDI") (pintype "bidirectional"))
    )
    (net (code "352") (name "Net-(U177-CO)") (class "Default")
      (node (ref "U177") (pin "CKO") (pinfunction "CO_CKO") (pintype "bidirectional"))
      (node (ref "U178") (pin "CKI") (pinfunction "CI_CKI") (pintype "bidirectional"))
    )
    (net (code "353") (name "Net-(U177-DO)") (class "Default")
      (node (ref "U177") (pin "SDO") (pinfunction "DO_SDO") (pintype "bidirectional"))
      (node (ref "U178") (pin "SDI") (pinfunction "DI_SDI") (pintype "bidirectional"))
    )
    (net (code "354") (name "Net-(U178-CO)") (class "Default")
      (node (ref "U178") (pin "CKO") (pinfunction "CO_CKO") (pintype "bidirectional"))
      (node (ref "U179") (pin "CKI") (pinfunction "CI_CKI") (pintype "bidirectional"))
    )
    (net (code "355") (name "Net-(U178-DO)") (class "Default")
      (node (ref "U178") (pin "SDO") (pinfunction "DO_SDO") (pintype "bidirectional"))
      (node (ref "U179") (pin "SDI") (pinfunction "DI_SDI") (pintype "bidirectional"))
    )
    (net (code "356") (name "Net-(U179-CO)") (class "Default")
      (node (ref "U179") (pin "CKO") (pinfunction "CO_CKO") (pintype "bidirectional"))
      (node (ref "U180") (pin "CKI") (pinfunction "CI_CKI") (pintype "bidirectional"))
    )
    (net (code "357") (name "Net-(U179-DO)") (class "Default")
      (node (ref "U179") (pin "SDO") (pinfunction "DO_SDO") (pintype "bidirectional"))
      (node (ref "U180") (pin "SDI") (pinfunction "DI_SDI") (pintype "bidirectional"))
    )
    (net (code "358") (name "Net-(U180-CO)") (class "Default")
      (node (ref "U180") (pin "CKO") (pinfunction "CO_CKO") (pintype "bidirectional"))
      (node (ref "U181") (pin "CKI") (pinfunction "CI_CKI") (pintype "bidirectional"))
    )
    (net (code "359") (name "Net-(U180-DO)") (class "Default")
      (node (ref "U180") (pin "SDO") (pinfunction "DO_SDO") (pintype "bidirectional"))
      (node (ref "U181") (pin "SDI") (pinfunction "DI_SDI") (pintype "bidirectional"))
    )
    (net (code "360") (name "Net-(U181-CO)") (class "Default")
      (node (ref "U181") (pin "CKO") (pinfunction "CO_CKO") (pintype "bidirectional"))
      (node (ref "U182") (pin "CKI") (pinfunction "CI_CKI") (pintype "bidirectional"))
    )
    (net (code "361") (name "Net-(U181-DO)") (class "Default")
      (node (ref "U181") (pin "SDO") (pinfunction "DO_SDO") (pintype "bidirectional"))
      (node (ref "U182") (pin "SDI") (pinfunction "DI_SDI") (pintype "bidirectional"))
    )
    (net (code "362") (name "Net-(U182-CO)") (class "Default")
      (node (ref "U182") (pin "CKO") (pinfunction "CO_CKO") (pintype "bidirectional"))
      (node (ref "U183") (pin "CKI") (pinfunction "CI_CKI") (pintype "bidirectional"))
    )
    (net (code "363") (name "Net-(U182-DO)") (class "Default")
      (node (ref "U182") (pin "SDO") (pinfunction "DO_SDO") (pintype "bidirectional"))
      (node (ref "U183") (pin "SDI") (pinfunction "DI_SDI") (pintype "bidirectional"))
    )
    (net (code "364") (name "Net-(U183-CO)") (class "Default")
      (node (ref "U183") (pin "CKO") (pinfunction "CO_CKO") (pintype "bidirectional"))
      (node (ref "U184") (pin "CKI") (pinfunction "CI_CKI") (pintype "bidirectional"))
    )
    (net (code "365") (name "Net-(U183-DO)") (class "Default")
      (node (ref "U183") (pin "SDO") (pinfunction "DO_SDO") (pintype "bidirectional"))
      (node (ref "U184") (pin "SDI") (pinfunction "DI_SDI") (pintype "bidirectional"))
    )
    (net (code "366") (name "Net-(U184-CO)") (class "Default")
      (node (ref "U184") (pin "CKO") (pinfunction "CO_CKO") (pintype "bidirectional"))
      (node (ref "U185") (pin "CKI") (pinfunction "CI_CKI") (pintype "bidirectional"))
    )
    (net (code "367") (name "Net-(U184-DO)") (class "Default")
      (node (ref "U184") (pin "SDO") (pinfunction "DO_SDO") (pintype "bidirectional"))
      (node (ref "U185") (pin "SDI") (pinfunction "DI_SDI") (pintype "bidirectional"))
    )
    (net (code "368") (name "Net-(U185-CO)") (class "Default")
      (node (ref "U185") (pin "CKO") (pinfunction "CO_CKO") (pintype "bidirectional"))
      (node (ref "U186") (pin "CKI") (pinfunction "CI_CKI") (pintype "bidirectional"))
    )
    (net (code "369") (name "Net-(U185-DO)") (class "Default")
      (node (ref "U185") (pin "SDO") (pinfunction "DO_SDO") (pintype "bidirectional"))
      (node (ref "U186") (pin "SDI") (pinfunction "DI_SDI") (pintype "bidirectional"))
    )
    (net (code "370") (name "Net-(U186-CO)") (class "Default")
      (node (ref "U186") (pin "CKO") (pinfunction "CO_CKO") (pintype "bidirectional"))
      (node (ref "U187") (pin "CKI") (pinfunction "CI_CKI") (pintype "bidirectional"))
    )
    (net (code "371") (name "Net-(U186-DO)") (class "Default")
      (node (ref "U186") (pin "SDO") (pinfunction "DO_SDO") (pintype "bidirectional"))
      (node (ref "U187") (pin "SDI") (pinfunction "DI_SDI") (pintype "bidirectional"))
    )
    (net (code "372") (name "Net-(U187-CO)") (class "Default")
      (node (ref "U187") (pin "CKO") (pinfunction "CO_CKO") (pintype "bidirectional"))
      (node (ref "U188") (pin "CKI") (pinfunction "CI_CKI") (pintype "bidirectional"))
    )
    (net (code "373") (name "Net-(U187-DO)") (class "Default")
      (node (ref "U187") (pin "SDO") (pinfunction "DO_SDO") (pintype "bidirectional"))
      (node (ref "U188") (pin "SDI") (pinfunction "DI_SDI") (pintype "bidirectional"))
    )
    (net (code "374") (name "Net-(U188-CO)") (class "Default")
      (node (ref "U188") (pin "CKO") (pinfunction "CO_CKO") (pintype "bidirectional"))
      (node (ref "U189") (pin "CKI") (pinfunction "CI_CKI") (pintype "bidirectional"))
    )
    (net (code "375") (name "Net-(U188-DO)") (class "Default")
      (node (ref "U188") (pin "SDO") (pinfunction "DO_SDO") (pintype "bidirectional"))
      (node (ref "U189") (pin "SDI") (pinfunction "DI_SDI") (pintype "bidirectional"))
    )
    (net (code "376") (name "Net-(U189-CO)") (class "Default")
      (node (ref "U189") (pin "CKO") (pinfunction "CO_CKO") (pintype "bidirectional"))
      (node (ref "U190") (pin "CKI") (pinfunction "CI_CKI") (pintype "bidirectional"))
    )
    (net (code "377") (name "Net-(U189-DO)") (class "Default")
      (node (ref "U189") (pin "SDO") (pinfunction "DO_SDO") (pintype "bidirectional"))
      (node (ref "U190") (pin "SDI") (pinfunction "DI_SDI") (pintype "bidirectional"))
    )
    (net (code "378") (name "Net-(U190-CO)") (class "Default")
      (node (ref "U190") (pin "CKO") (pinfunction "CO_CKO") (pintype "bidirectional"))
      (node (ref "U191") (pin "CKI") (pinfunction "CI_CKI") (pintype "bidirectional"))
    )
    (net (code "379") (name "Net-(U190-DO)") (class "Default")
      (node (ref "U190") (pin "SDO") (pinfunction "DO_SDO") (pintype "bidirectional"))
      (node (ref "U191") (pin "SDI") (pinfunction "DI_SDI") (pintype "bidirectional"))
    )
    (net (code "380") (name "Net-(U191-CO)") (class "Default")
      (node (ref "U191") (pin "CKO") (pinfunction "CO_CKO") (pintype "bidirectional"))
      (node (ref "U192") (pin "CKI") (pinfunction "CI_CKI") (pintype "bidirectional"))
    )
    (net (code "381") (name "Net-(U191-DO)") (class "Default")
      (node (ref "U191") (pin "SDO") (pinfunction "DO_SDO") (pintype "bidirectional"))
      (node (ref "U192") (pin "SDI") (pinfunction "DI_SDI") (pintype "bidirectional"))
    )
    (net (code "382") (name "Net-(U192-CO)") (class "Default")
      (node (ref "U192") (pin "CKO") (pinfunction "CO_CKO") (pintype "bidirectional"))
      (node (ref "U193") (pin "CKI") (pinfunction "CI_CKI") (pintype "bidirectional"))
    )
    (net (code "383") (name "Net-(U192-DO)") (class "Default")
      (node (ref "U192") (pin "SDO") (pinfunction "DO_SDO") (pintype "bidirectional"))
      (node (ref "U193") (pin "SDI") (pinfunction "DI_SDI") (pintype "bidirectional"))
    )
    (net (code "384") (name "Net-(U193-CO)") (class "Default")
      (node (ref "U193") (pin "CKO") (pinfunction "CO_CKO") (pintype "bidirectional"))
      (node (ref "U194") (pin "CKI") (pinfunction "CI_CKI") (pintype "bidirectional"))
    )
    (net (code "385") (name "Net-(U193-DO)") (class "Default")
      (node (ref "U193") (pin "SDO") (pinfunction "DO_SDO") (pintype "bidirectional"))
      (node (ref "U194") (pin "SDI") (pinfunction "DI_SDI") (pintype "bidirectional"))
    )
    (net (code "386") (name "Net-(U194-CO)") (class "Default")
      (node (ref "U194") (pin "CKO") (pinfunction "CO_CKO") (pintype "bidirectional"))
      (node (ref "U195") (pin "CKI") (pinfunction "CI_CKI") (pintype "bidirectional"))
    )
    (net (code "387") (name "Net-(U194-DO)") (class "Default")
      (node (ref "U194") (pin "SDO") (pinfunction "DO_SDO") (pintype "bidirectional"))
      (node (ref "U195") (pin "SDI") (pinfunction "DI_SDI") (pintype "bidirectional"))
    )
    (net (code "388") (name "Net-(U195-CO)") (class "Default")
      (node (ref "U195") (pin "CKO") (pinfunction "CO_CKO") (pintype "bidirectional"))
      (node (ref "U196") (pin "CKI") (pinfunction "CI_CKI") (pintype "bidirectional"))
    )
    (net (code "389") (name "Net-(U195-DO)") (class "Default")
      (node (ref "U195") (pin "SDO") (pinfunction "DO_SDO") (pintype "bidirectional"))
      (node (ref "U196") (pin "SDI") (pinfunction "DI_SDI") (pintype "bidirectional"))
    )
    (net (code "390") (name "Net-(U197-CO)") (class "Default")
      (node (ref "U197") (pin "CKO") (pinfunction "CO_CKO") (pintype "bidirectional"))
      (node (ref "U198") (pin "CKI") (pinfunction "CI_CKI") (pintype "bidirectional"))
    )
    (net (code "391") (name "Net-(U197-DO)") (class "Default")
      (node (ref "U197") (pin "SDO") (pinfunction "DO_SDO") (pintype "bidirectional"))
      (node (ref "U198") (pin "SDI") (pinfunction "DI_SDI") (pintype "bidirectional"))
    )
    (net (code "392") (name "Net-(U198-CO)") (class "Default")
      (node (ref "U198") (pin "CKO") (pinfunction "CO_CKO") (pintype "bidirectional"))
      (node (ref "U199") (pin "CKI") (pinfunction "CI_CKI") (pintype "bidirectional"))
    )
    (net (code "393") (name "Net-(U198-DO)") (class "Default")
      (node (ref "U198") (pin "SDO") (pinfunction "DO_SDO") (pintype "bidirectional"))
      (node (ref "U199") (pin "SDI") (pinfunction "DI_SDI") (pintype "bidirectional"))
    )
    (net (code "394") (name "Net-(U199-CO)") (class "Default")
      (node (ref "U199") (pin "CKO") (pinfunction "CO_CKO") (pintype "bidirectional"))
      (node (ref "U200") (pin "CKI") (pinfunction "CI_CKI") (pintype "bidirectional"))
    )
    (net (code "395") (name "Net-(U199-DO)") (class "Default")
      (node (ref "U199") (pin "SDO") (pinfunction "DO_SDO") (pintype "bidirectional"))
      (node (ref "U200") (pin "SDI") (pinfunction "DI_SDI") (pintype "bidirectional"))
    )
    (net (code "396") (name "Net-(U200-CO)") (class "Default")
      (node (ref "U200") (pin "CKO") (pinfunction "CO_CKO") (pintype "bidirectional"))
      (node (ref "U201") (pin "CKI") (pinfunction "CI_CKI") (pintype "bidirectional"))
    )
    (net (code "397") (name "Net-(U200-DO)") (class "Default")
      (node (ref "U200") (pin "SDO") (pinfunction "DO_SDO") (pintype "bidirectional"))
      (node (ref "U201") (pin "SDI") (pinfunction "DI_SDI") (pintype "bidirectional"))
    )
    (net (code "398") (name "Net-(U201-CO)") (class "Default")
      (node (ref "U201") (pin "CKO") (pinfunction "CO_CKO") (pintype "bidirectional"))
      (node (ref "U202") (pin "CKI") (pinfunction "CI_CKI") (pintype "bidirectional"))
    )
    (net (code "399") (name "Net-(U201-DO)") (class "Default")
      (node (ref "U201") (pin "SDO") (pinfunction "DO_SDO") (pintype "bidirectional"))
      (node (ref "U202") (pin "SDI") (pinfunction "DI_SDI") (pintype "bidirectional"))
    )
    (net (code "400") (name "Net-(U202-CO)") (class "Default")
      (node (ref "U202") (pin "CKO") (pinfunction "CO_CKO") (pintype "bidirectional"))
      (node (ref "U203") (pin "CKI") (pinfunction "CI_CKI") (pintype "bidirectional"))
    )
    (net (code "401") (name "Net-(U202-DO)") (class "Default")
      (node (ref "U202") (pin "SDO") (pinfunction "DO_SDO") (pintype "bidirectional"))
      (node (ref "U203") (pin "SDI") (pinfunction "DI_SDI") (pintype "bidirectional"))
    )
    (net (code "402") (name "Net-(U203-CO)") (class "Default")
      (node (ref "U203") (pin "CKO") (pinfunction "CO_CKO") (pintype "bidirectional"))
      (node (ref "U204") (pin "CKI") (pinfunction "CI_CKI") (pintype "bidirectional"))
    )
    (net (code "403") (name "Net-(U203-DO)") (class "Default")
      (node (ref "U203") (pin "SDO") (pinfunction "DO_SDO") (pintype "bidirectional"))
      (node (ref "U204") (pin "SDI") (pinfunction "DI_SDI") (pintype "bidirectional"))
    )
    (net (code "404") (name "Net-(U204-CO)") (class "Default")
      (node (ref "U204") (pin "CKO") (pinfunction "CO_CKO") (pintype "bidirectional"))
      (node (ref "U205") (pin "CKI") (pinfunction "CI_CKI") (pintype "bidirectional"))
    )
    (net (code "405") (name "Net-(U204-DO)") (class "Default")
      (node (ref "U204") (pin "SDO") (pinfunction "DO_SDO") (pintype "bidirectional"))
      (node (ref "U205") (pin "SDI") (pinfunction "DI_SDI") (pintype "bidirectional"))
    )
    (net (code "406") (name "Net-(U205-CO)") (class "Default")
      (node (ref "U205") (pin "CKO") (pinfunction "CO_CKO") (pintype "bidirectional"))
      (node (ref "U206") (pin "CKI") (pinfunction "CI_CKI") (pintype "bidirectional"))
    )
    (net (code "407") (name "Net-(U205-DO)") (class "Default")
      (node (ref "U205") (pin "SDO") (pinfunction "DO_SDO") (pintype "bidirectional"))
      (node (ref "U206") (pin "SDI") (pinfunction "DI_SDI") (pintype "bidirectional"))
    )
    (net (code "408") (name "Net-(U206-CO)") (class "Default")
      (node (ref "U206") (pin "CKO") (pinfunction "CO_CKO") (pintype "bidirectional"))
      (node (ref "U207") (pin "CKI") (pinfunction "CI_CKI") (pintype "bidirectional"))
    )
    (net (code "409") (name "Net-(U206-DO)") (class "Default")
      (node (ref "U206") (pin "SDO") (pinfunction "DO_SDO") (pintype "bidirectional"))
      (node (ref "U207") (pin "SDI") (pinfunction "DI_SDI") (pintype "bidirectional"))
    )
    (net (code "410") (name "Net-(U207-CO)") (class "Default")
      (node (ref "U207") (pin "CKO") (pinfunction "CO_CKO") (pintype "bidirectional"))
      (node (ref "U208") (pin "CKI") (pinfunction "CI_CKI") (pintype "bidirectional"))
    )
    (net (code "411") (name "Net-(U207-DO)") (class "Default")
      (node (ref "U207") (pin "SDO") (pinfunction "DO_SDO") (pintype "bidirectional"))
      (node (ref "U208") (pin "SDI") (pinfunction "DI_SDI") (pintype "bidirectional"))
    )
    (net (code "412") (name "Net-(U208-CO)") (class "Default")
      (node (ref "U208") (pin "CKO") (pinfunction "CO_CKO") (pintype "bidirectional"))
      (node (ref "U209") (pin "CKI") (pinfunction "CI_CKI") (pintype "bidirectional"))
    )
    (net (code "413") (name "Net-(U208-DO)") (class "Default")
      (node (ref "U208") (pin "SDO") (pinfunction "DO_SDO") (pintype "bidirectional"))
      (node (ref "U209") (pin "SDI") (pinfunction "DI_SDI") (pintype "bidirectional"))
    )
    (net (code "414") (name "Net-(U209-CO)") (class "Default")
      (node (ref "U209") (pin "CKO") (pinfunction "CO_CKO") (pintype "bidirectional"))
      (node (ref "U210") (pin "CKI") (pinfunction "CI_CKI") (pintype "bidirectional"))
    )
    (net (code "415") (name "Net-(U209-DO)") (class "Default")
      (node (ref "U209") (pin "SDO") (pinfunction "DO_SDO") (pintype "bidirectional"))
      (node (ref "U210") (pin "SDI") (pinfunction "DI_SDI") (pintype "bidirectional"))
    )
    (net (code "416") (name "Net-(U210-CO)") (class "Default")
      (node (ref "U210") (pin "CKO") (pinfunction "CO_CKO") (pintype "bidirectional"))
      (node (ref "U211") (pin "CKI") (pinfunction "CI_CKI") (pintype "bidirectional"))
    )
    (net (code "417") (name "Net-(U210-DO)") (class "Default")
      (node (ref "U210") (pin "SDO") (pinfunction "DO_SDO") (pintype "bidirectional"))
      (node (ref "U211") (pin "SDI") (pinfunction "DI_SDI") (pintype "bidirectional"))
    )
    (net (code "418") (name "Net-(U211-CO)") (class "Default")
      (node (ref "U211") (pin "CKO") (pinfunction "CO_CKO") (pintype "bidirectional"))
      (node (ref "U212") (pin "CKI") (pinfunction "CI_CKI") (pintype "bidirectional"))
    )
    (net (code "419") (name "Net-(U211-DO)") (class "Default")
      (node (ref "U211") (pin "SDO") (pinfunction "DO_SDO") (pintype "bidirectional"))
      (node (ref "U212") (pin "SDI") (pinfunction "DI_SDI") (pintype "bidirectional"))
    )
    (net (code "420") (name "Net-(U212-CO)") (class "Default")
      (node (ref "U212") (pin "CKO") (pinfunction "CO_CKO") (pintype "bidirectional"))
      (node (ref "U213") (pin "CKI") (pinfunction "CI_CKI") (pintype "bidirectional"))
    )
    (net (code "421") (name "Net-(U212-DO)") (class "Default")
      (node (ref "U212") (pin "SDO") (pinfunction "DO_SDO") (pintype "bidirectional"))
      (node (ref "U213") (pin "SDI") (pinfunction "DI_SDI") (pintype "bidirectional"))
    )
    (net (code "422") (name "Net-(U213-CO)") (class "Default")
      (node (ref "U213") (pin "CKO") (pinfunction "CO_CKO") (pintype "bidirectional"))
      (node (ref "U214") (pin "CKI") (pinfunction "CI_CKI") (pintype "bidirectional"))
    )
    (net (code "423") (name "Net-(U213-DO)") (class "Default")
      (node (ref "U213") (pin "SDO") (pinfunction "DO_SDO") (pintype "bidirectional"))
      (node (ref "U214") (pin "SDI") (pinfunction "DI_SDI") (pintype "bidirectional"))
    )
    (net (code "424") (name "Net-(U214-CO)") (class "Default")
      (node (ref "U214") (pin "CKO") (pinfunction "CO_CKO") (pintype "bidirectional"))
      (node (ref "U215") (pin "CKI") (pinfunction "CI_CKI") (pintype "bidirectional"))
    )
    (net (code "425") (name "Net-(U214-DO)") (class "Default")
      (node (ref "U214") (pin "SDO") (pinfunction "DO_SDO") (pintype "bidirectional"))
      (node (ref "U215") (pin "SDI") (pinfunction "DI_SDI") (pintype "bidirectional"))
    )
    (net (code "426") (name "Net-(U215-CO)") (class "Default")
      (node (ref "U215") (pin "CKO") (pinfunction "CO_CKO") (pintype "bidirectional"))
      (node (ref "U216") (pin "CKI") (pinfunction "CI_CKI") (pintype "bidirectional"))
    )
    (net (code "427") (name "Net-(U215-DO)") (class "Default")
      (node (ref "U215") (pin "SDO") (pinfunction "DO_SDO") (pintype "bidirectional"))
      (node (ref "U216") (pin "SDI") (pinfunction "DI_SDI") (pintype "bidirectional"))
    )
    (net (code "428") (name "Net-(U216-CO)") (class "Default")
      (node (ref "U216") (pin "CKO") (pinfunction "CO_CKO") (pintype "bidirectional"))
      (node (ref "U217") (pin "CKI") (pinfunction "CI_CKI") (pintype "bidirectional"))
    )
    (net (code "429") (name "Net-(U216-DO)") (class "Default")
      (node (ref "U216") (pin "SDO") (pinfunction "DO_SDO") (pintype "bidirectional"))
      (node (ref "U217") (pin "SDI") (pinfunction "DI_SDI") (pintype "bidirectional"))
    )
    (net (code "430") (name "Net-(U217-CO)") (class "Default")
      (node (ref "U217") (pin "CKO") (pinfunction "CO_CKO") (pintype "bidirectional"))
      (node (ref "U218") (pin "CKI") (pinfunction "CI_CKI") (pintype "bidirectional"))
    )
    (net (code "431") (name "Net-(U217-DO)") (class "Default")
      (node (ref "U217") (pin "SDO") (pinfunction "DO_SDO") (pintype "bidirectional"))
      (node (ref "U218") (pin "SDI") (pinfunction "DI_SDI") (pintype "bidirectional"))
    )
    (net (code "432") (name "Net-(U218-CO)") (class "Default")
      (node (ref "U218") (pin "CKO") (pinfunction "CO_CKO") (pintype "bidirectional"))
      (node (ref "U219") (pin "CKI") (pinfunction "CI_CKI") (pintype "bidirectional"))
    )
    (net (code "433") (name "Net-(U218-DO)") (class "Default")
      (node (ref "U218") (pin "SDO") (pinfunction "DO_SDO") (pintype "bidirectional"))
      (node (ref "U219") (pin "SDI") (pinfunction "DI_SDI") (pintype "bidirectional"))
    )
    (net (code "434") (name "Net-(U219-CO)") (class "Default")
      (node (ref "U219") (pin "CKO") (pinfunction "CO_CKO") (pintype "bidirectional"))
      (node (ref "U220") (pin "CKI") (pinfunction "CI_CKI") (pintype "bidirectional"))
    )
    (net (code "435") (name "Net-(U219-DO)") (class "Default")
      (node (ref "U219") (pin "SDO") (pinfunction "DO_SDO") (pintype "bidirectional"))
      (node (ref "U220") (pin "SDI") (pinfunction "DI_SDI") (pintype "bidirectional"))
    )
    (net (code "436") (name "Net-(U220-CO)") (class "Default")
      (node (ref "U220") (pin "CKO") (pinfunction "CO_CKO") (pintype "bidirectional"))
      (node (ref "U221") (pin "CKI") (pinfunction "CI_CKI") (pintype "bidirectional"))
    )
    (net (code "437") (name "Net-(U220-DO)") (class "Default")
      (node (ref "U220") (pin "SDO") (pinfunction "DO_SDO") (pintype "bidirectional"))
      (node (ref "U221") (pin "SDI") (pinfunction "DI_SDI") (pintype "bidirectional"))
    )
    (net (code "438") (name "Net-(U221-CO)") (class "Default")
      (node (ref "U221") (pin "CKO") (pinfunction "CO_CKO") (pintype "bidirectional"))
      (node (ref "U222") (pin "CKI") (pinfunction "CI_CKI") (pintype "bidirectional"))
    )
    (net (code "439") (name "Net-(U221-DO)") (class "Default")
      (node (ref "U221") (pin "SDO") (pinfunction "DO_SDO") (pintype "bidirectional"))
      (node (ref "U222") (pin "SDI") (pinfunction "DI_SDI") (pintype "bidirectional"))
    )
    (net (code "440") (name "Net-(U222-CO)") (class "Default")
      (node (ref "U222") (pin "CKO") (pinfunction "CO_CKO") (pintype "bidirectional"))
      (node (ref "U223") (pin "CKI") (pinfunction "CI_CKI") (pintype "bidirectional"))
    )
    (net (code "441") (name "Net-(U222-DO)") (class "Default")
      (node (ref "U222") (pin "SDO") (pinfunction "DO_SDO") (pintype "bidirectional"))
      (node (ref "U223") (pin "SDI") (pinfunction "DI_SDI") (pintype "bidirectional"))
    )
    (net (code "442") (name "Net-(U223-CO)") (class "Default")
      (node (ref "U223") (pin "CKO") (pinfunction "CO_CKO") (pintype "bidirectional"))
      (node (ref "U224") (pin "CKI") (pinfunction "CI_CKI") (pintype "bidirectional"))
    )
    (net (code "443") (name "Net-(U223-DO)") (class "Default")
      (node (ref "U223") (pin "SDO") (pinfunction "DO_SDO") (pintype "bidirectional"))
      (node (ref "U224") (pin "SDI") (pinfunction "DI_SDI") (pintype "bidirectional"))
    )
    (net (code "444") (name "Net-(U225-CO)") (class "Default")
      (node (ref "U225") (pin "CKO") (pinfunction "CO_CKO") (pintype "bidirectional"))
      (node (ref "U226") (pin "CKI") (pinfunction "CI_CKI") (pintype "bidirectional"))
    )
    (net (code "445") (name "Net-(U225-DO)") (class "Default")
      (node (ref "U225") (pin "SDO") (pinfunction "DO_SDO") (pintype "bidirectional"))
      (node (ref "U226") (pin "SDI") (pinfunction "DI_SDI") (pintype "bidirectional"))
    )
    (net (code "446") (name "Net-(U226-CO)") (class "Default")
      (node (ref "U226") (pin "CKO") (pinfunction "CO_CKO") (pintype "bidirectional"))
      (node (ref "U227") (pin "CKI") (pinfunction "CI_CKI") (pintype "bidirectional"))
    )
    (net (code "447") (name "Net-(U226-DO)") (class "Default")
      (node (ref "U226") (pin "SDO") (pinfunction "DO_SDO") (pintype "bidirectional"))
      (node (ref "U227") (pin "SDI") (pinfunction "DI_SDI") (pintype "bidirectional"))
    )
    (net (code "448") (name "Net-(U227-CO)") (class "Default")
      (node (ref "U227") (pin "CKO") (pinfunction "CO_CKO") (pintype "bidirectional"))
      (node (ref "U228") (pin "CKI") (pinfunction "CI_CKI") (pintype "bidirectional"))
    )
    (net (code "449") (name "Net-(U227-DO)") (class "Default")
      (node (ref "U227") (pin "SDO") (pinfunction "DO_SDO") (pintype "bidirectional"))
      (node (ref "U228") (pin "SDI") (pinfunction "DI_SDI") (pintype "bidirectional"))
    )
    (net (code "450") (name "Net-(U228-CO)") (class "Default")
      (node (ref "U228") (pin "CKO") (pinfunction "CO_CKO") (pintype "bidirectional"))
      (node (ref "U229") (pin "CKI") (pinfunction "CI_CKI") (pintype "bidirectional"))
    )
    (net (code "451") (name "Net-(U228-DO)") (class "Default")
      (node (ref "U228") (pin "SDO") (pinfunction "DO_SDO") (pintype "bidirectional"))
      (node (ref "U229") (pin "SDI") (pinfunction "DI_SDI") (pintype "bidirectional"))
    )
    (net (code "452") (name "Net-(U229-CO)") (class "Default")
      (node (ref "U229") (pin "CKO") (pinfunction "CO_CKO") (pintype "bidirectional"))
      (node (ref "U230") (pin "CKI") (pinfunction "CI_CKI") (pintype "bidirectional"))
    )
    (net (code "453") (name "Net-(U229-DO)") (class "Default")
      (node (ref "U229") (pin "SDO") (pinfunction "DO_SDO") (pintype "bidirectional"))
      (node (ref "U230") (pin "SDI") (pinfunction "DI_SDI") (pintype "bidirectional"))
    )
    (net (code "454") (name "Net-(U230-CO)") (class "Default")
      (node (ref "U230") (pin "CKO") (pinfunction "CO_CKO") (pintype "bidirectional"))
      (node (ref "U231") (pin "CKI") (pinfunction "CI_CKI") (pintype "bidirectional"))
    )
    (net (code "455") (name "Net-(U230-DO)") (class "Default")
      (node (ref "U230") (pin "SDO") (pinfunction "DO_SDO") (pintype "bidirectional"))
      (node (ref "U231") (pin "SDI") (pinfunction "DI_SDI") (pintype "bidirectional"))
    )
    (net (code "456") (name "Net-(U231-CO)") (class "Default")
      (node (ref "U231") (pin "CKO") (pinfunction "CO_CKO") (pintype "bidirectional"))
      (node (ref "U232") (pin "CKI") (pinfunction "CI_CKI") (pintype "bidirectional"))
    )
    (net (code "457") (name "Net-(U231-DO)") (class "Default")
      (node (ref "U231") (pin "SDO") (pinfunction "DO_SDO") (pintype "bidirectional"))
      (node (ref "U232") (pin "SDI") (pinfunction "DI_SDI") (pintype "bidirectional"))
    )
    (net (code "458") (name "Net-(U232-CO)") (class "Default")
      (node (ref "U232") (pin "CKO") (pinfunction "CO_CKO") (pintype "bidirectional"))
      (node (ref "U233") (pin "CKI") (pinfunction "CI_CKI") (pintype "bidirectional"))
    )
    (net (code "459") (name "Net-(U232-DO)") (class "Default")
      (node (ref "U232") (pin "SDO") (pinfunction "DO_SDO") (pintype "bidirectional"))
      (node (ref "U233") (pin "SDI") (pinfunction "DI_SDI") (pintype "bidirectional"))
    )
    (net (code "460") (name "Net-(U233-CO)") (class "Default")
      (node (ref "U233") (pin "CKO") (pinfunction "CO_CKO") (pintype "bidirectional"))
      (node (ref "U234") (pin "CKI") (pinfunction "CI_CKI") (pintype "bidirectional"))
    )
    (net (code "461") (name "Net-(U233-DO)") (class "Default")
      (node (ref "U233") (pin "SDO") (pinfunction "DO_SDO") (pintype "bidirectional"))
      (node (ref "U234") (pin "SDI") (pinfunction "DI_SDI") (pintype "bidirectional"))
    )
    (net (code "462") (name "Net-(U234-CO)") (class "Default")
      (node (ref "U234") (pin "CKO") (pinfunction "CO_CKO") (pintype "bidirectional"))
      (node (ref "U235") (pin "CKI") (pinfunction "CI_CKI") (pintype "bidirectional"))
    )
    (net (code "463") (name "Net-(U234-DO)") (class "Default")
      (node (ref "U234") (pin "SDO") (pinfunction "DO_SDO") (pintype "bidirectional"))
      (node (ref "U235") (pin "SDI") (pinfunction "DI_SDI") (pintype "bidirectional"))
    )
    (net (code "464") (name "Net-(U235-CO)") (class "Default")
      (node (ref "U235") (pin "CKO") (pinfunction "CO_CKO") (pintype "bidirectional"))
      (node (ref "U236") (pin "CKI") (pinfunction "CI_CKI") (pintype "bidirectional"))
    )
    (net (code "465") (name "Net-(U235-DO)") (class "Default")
      (node (ref "U235") (pin "SDO") (pinfunction "DO_SDO") (pintype "bidirectional"))
      (node (ref "U236") (pin "SDI") (pinfunction "DI_SDI") (pintype "bidirectional"))
    )
    (net (code "466") (name "Net-(U236-CO)") (class "Default")
      (node (ref "U236") (pin "CKO") (pinfunction "CO_CKO") (pintype "bidirectional"))
      (node (ref "U237") (pin "CKI") (pinfunction "CI_CKI") (pintype "bidirectional"))
    )
    (net (code "467") (name "Net-(U236-DO)") (class "Default")
      (node (ref "U236") (pin "SDO") (pinfunction "DO_SDO") (pintype "bidirectional"))
      (node (ref "U237") (pin "SDI") (pinfunction "DI_SDI") (pintype "bidirectional"))
    )
    (net (code "468") (name "Net-(U237-CO)") (class "Default")
      (node (ref "U237") (pin "CKO") (pinfunction "CO_CKO") (pintype "bidirectional"))
      (node (ref "U238") (pin "CKI") (pinfunction "CI_CKI") (pintype "bidirectional"))
    )
    (net (code "469") (name "Net-(U237-DO)") (class "Default")
      (node (ref "U237") (pin "SDO") (pinfunction "DO_SDO") (pintype "bidirectional"))
      (node (ref "U238") (pin "SDI") (pinfunction "DI_SDI") (pintype "bidirectional"))
    )
    (net (code "470") (name "Net-(U238-CO)") (class "Default")
      (node (ref "U238") (pin "CKO") (pinfunction "CO_CKO") (pintype "bidirectional"))
      (node (ref "U239") (pin "CKI") (pinfunction "CI_CKI") (pintype "bidirectional"))
    )
    (net (code "471") (name "Net-(U238-DO)") (class "Default")
      (node (ref "U238") (pin "SDO") (pinfunction "DO_SDO") (pintype "bidirectional"))
      (node (ref "U239") (pin "SDI") (pinfunction "DI_SDI") (pintype "bidirectional"))
    )
    (net (code "472") (name "Net-(U239-CO)") (class "Default")
      (node (ref "U239") (pin "CKO") (pinfunction "CO_CKO") (pintype "bidirectional"))
      (node (ref "U240") (pin "CKI") (pinfunction "CI_CKI") (pintype "bidirectional"))
    )
    (net (code "473") (name "Net-(U239-DO)") (class "Default")
      (node (ref "U239") (pin "SDO") (pinfunction "DO_SDO") (pintype "bidirectional"))
      (node (ref "U240") (pin "SDI") (pinfunction "DI_SDI") (pintype "bidirectional"))
    )
    (net (code "474") (name "Net-(U240-CO)") (class "Default")
      (node (ref "U240") (pin "CKO") (pinfunction "CO_CKO") (pintype "bidirectional"))
      (node (ref "U241") (pin "CKI") (pinfunction "CI_CKI") (pintype "bidirectional"))
    )
    (net (code "475") (name "Net-(U240-DO)") (class "Default")
      (node (ref "U240") (pin "SDO") (pinfunction "DO_SDO") (pintype "bidirectional"))
      (node (ref "U241") (pin "SDI") (pinfunction "DI_SDI") (pintype "bidirectional"))
    )
    (net (code "476") (name "Net-(U241-CO)") (class "Default")
      (node (ref "U241") (pin "CKO") (pinfunction "CO_CKO") (pintype "bidirectional"))
      (node (ref "U242") (pin "CKI") (pinfunction "CI_CKI") (pintype "bidirectional"))
    )
    (net (code "477") (name "Net-(U241-DO)") (class "Default")
      (node (ref "U241") (pin "SDO") (pinfunction "DO_SDO") (pintype "bidirectional"))
      (node (ref "U242") (pin "SDI") (pinfunction "DI_SDI") (pintype "bidirectional"))
    )
    (net (code "478") (name "Net-(U242-CO)") (class "Default")
      (node (ref "U242") (pin "CKO") (pinfunction "CO_CKO") (pintype "bidirectional"))
      (node (ref "U243") (pin "CKI") (pinfunction "CI_CKI") (pintype "bidirectional"))
    )
    (net (code "479") (name "Net-(U242-DO)") (class "Default")
      (node (ref "U242") (pin "SDO") (pinfunction "DO_SDO") (pintype "bidirectional"))
      (node (ref "U243") (pin "SDI") (pinfunction "DI_SDI") (pintype "bidirectional"))
    )
    (net (code "480") (name "Net-(U243-CO)") (class "Default")
      (node (ref "U243") (pin "CKO") (pinfunction "CO_CKO") (pintype "bidirectional"))
      (node (ref "U244") (pin "CKI") (pinfunction "CI_CKI") (pintype "bidirectional"))
    )
    (net (code "481") (name "Net-(U243-DO)") (class "Default")
      (node (ref "U243") (pin "SDO") (pinfunction "DO_SDO") (pintype "bidirectional"))
      (node (ref "U244") (pin "SDI") (pinfunction "DI_SDI") (pintype "bidirectional"))
    )
    (net (code "482") (name "Net-(U244-CO)") (class "Default")
      (node (ref "U244") (pin "CKO") (pinfunction "CO_CKO") (pintype "bidirectional"))
      (node (ref "U245") (pin "CKI") (pinfunction "CI_CKI") (pintype "bidirectional"))
    )
    (net (code "483") (name "Net-(U244-DO)") (class "Default")
      (node (ref "U244") (pin "SDO") (pinfunction "DO_SDO") (pintype "bidirectional"))
      (node (ref "U245") (pin "SDI") (pinfunction "DI_SDI") (pintype "bidirectional"))
    )
    (net (code "484") (name "Net-(U245-CO)") (class "Default")
      (node (ref "U245") (pin "CKO") (pinfunction "CO_CKO") (pintype "bidirectional"))
      (node (ref "U246") (pin "CKI") (pinfunction "CI_CKI") (pintype "bidirectional"))
    )
    (net (code "485") (name "Net-(U245-DO)") (class "Default")
      (node (ref "U245") (pin "SDO") (pinfunction "DO_SDO") (pintype "bidirectional"))
      (node (ref "U246") (pin "SDI") (pinfunction "DI_SDI") (pintype "bidirectional"))
    )
    (net (code "486") (name "Net-(U246-CO)") (class "Default")
      (node (ref "U246") (pin "CKO") (pinfunction "CO_CKO") (pintype "bidirectional"))
      (node (ref "U247") (pin "CKI") (pinfunction "CI_CKI") (pintype "bidirectional"))
    )
    (net (code "487") (name "Net-(U246-DO)") (class "Default")
      (node (ref "U246") (pin "SDO") (pinfunction "DO_SDO") (pintype "bidirectional"))
      (node (ref "U247") (pin "SDI") (pinfunction "DI_SDI") (pintype "bidirectional"))
    )
    (net (code "488") (name "Net-(U247-CO)") (class "Default")
      (node (ref "U247") (pin "CKO") (pinfunction "CO_CKO") (pintype "bidirectional"))
      (node (ref "U248") (pin "CKI") (pinfunction "CI_CKI") (pintype "bidirectional"))
    )
    (net (code "489") (name "Net-(U247-DO)") (class "Default")
      (node (ref "U247") (pin "SDO") (pinfunction "DO_SDO") (pintype "bidirectional"))
      (node (ref "U248") (pin "SDI") (pinfunction "DI_SDI") (pintype "bidirectional"))
    )
    (net (code "490") (name "Net-(U248-CO)") (class "Default")
      (node (ref "U248") (pin "CKO") (pinfunction "CO_CKO") (pintype "bidirectional"))
      (node (ref "U249") (pin "CKI") (pinfunction "CI_CKI") (pintype "bidirectional"))
    )
    (net (code "491") (name "Net-(U248-DO)") (class "Default")
      (node (ref "U248") (pin "SDO") (pinfunction "DO_SDO") (pintype "bidirectional"))
      (node (ref "U249") (pin "SDI") (pinfunction "DI_SDI") (pintype "bidirectional"))
    )
    (net (code "492") (name "Net-(U249-CO)") (class "Default")
      (node (ref "U249") (pin "CKO") (pinfunction "CO_CKO") (pintype "bidirectional"))
      (node (ref "U250") (pin "CKI") (pinfunction "CI_CKI") (pintype "bidirectional"))
    )
    (net (code "493") (name "Net-(U249-DO)") (class "Default")
      (node (ref "U249") (pin "SDO") (pinfunction "DO_SDO") (pintype "bidirectional"))
      (node (ref "U250") (pin "SDI") (pinfunction "DI_SDI") (pintype "bidirectional"))
    )
    (net (code "494") (name "Net-(U250-CO)") (class "Default")
      (node (ref "U250") (pin "CKO") (pinfunction "CO_CKO") (pintype "bidirectional"))
      (node (ref "U251") (pin "CKI") (pinfunction "CI_CKI") (pintype "bidirectional"))
    )
    (net (code "495") (name "Net-(U250-DO)") (class "Default")
      (node (ref "U250") (pin "SDO") (pinfunction "DO_SDO") (pintype "bidirectional"))
      (node (ref "U251") (pin "SDI") (pinfunction "DI_SDI") (pintype "bidirectional"))
    )
    (net (code "496") (name "Net-(U251-CO)") (class "Default")
      (node (ref "U251") (pin "CKO") (pinfunction "CO_CKO") (pintype "bidirectional"))
      (node (ref "U252") (pin "CKI") (pinfunction "CI_CKI") (pintype "bidirectional"))
    )
    (net (code "497") (name "Net-(U251-DO)") (class "Default")
      (node (ref "U251") (pin "SDO") (pinfunction "DO_SDO") (pintype "bidirectional"))
      (node (ref "U252") (pin "SDI") (pinfunction "DI_SDI") (pintype "bidirectional"))
    )
    (net (code "498") (name "SD1") (class "Default")
      (node (ref "U28") (pin "SDO") (pinfunction "DO_SDO") (pintype "bidirectional"))
      (node (ref "U29") (pin "SDI") (pinfunction "DI_SDI") (pintype "bidirectional"))
    )
    (net (code "499") (name "SD2") (class "Default")
      (node (ref "U56") (pin "SDO") (pinfunction "DO_SDO") (pintype "bidirectional"))
      (node (ref "U57") (pin "SDI") (pinfunction "DI_SDI") (pintype "bidirectional"))
    )
    (net (code "500") (name "SD3") (class "Default")
      (node (ref "U84") (pin "SDO") (pinfunction "DO_SDO") (pintype "bidirectional"))
      (node (ref "U85") (pin "SDI") (pinfunction "DI_SDI") (pintype "bidirectional"))
    )
    (net (code "501") (name "SD4") (class "Default")
      (node (ref "U112") (pin "SDO") (pinfunction "DO_SDO") (pintype "bidirectional"))
      (node (ref "U113") (pin "SDI") (pinfunction "DI_SDI") (pintype "bidirectional"))
    )
    (net (code "502") (name "SD5") (class "Default")
      (node (ref "U140") (pin "SDO") (pinfunction "DO_SDO") (pintype "bidirectional"))
      (node (ref "U141") (pin "SDI") (pinfunction "DI_SDI") (pintype "bidirectional"))
    )
    (net (code "503") (name "SD6") (class "Default")
      (node (ref "U168") (pin "SDO") (pinfunction "DO_SDO") (pintype "bidirectional"))
      (node (ref "U169") (pin "SDI") (pinfunction "DI_SDI") (pintype "bidirectional"))
    )
    (net (code "504") (name "SD7") (class "Default")
      (node (ref "U196") (pin "SDO") (pinfunction "DO_SDO") (pintype "bidirectional"))
      (node (ref "U197") (pin "SDI") (pinfunction "DI_SDI") (pintype "bidirectional"))
    )
    (net (code "505") (name "SD8") (class "Default")
      (node (ref "U224") (pin "SDO") (pinfunction "DO_SDO") (pintype "bidirectional"))
      (node (ref "U225") (pin "SDI") (pinfunction "DI_SDI") (pintype "bidirectional"))
    )
    (net (code "506") (name "VCC") (class "Default")
      (node (ref "J1") (pin "2") (pinfunction "2_2") (pintype "power_in"))
      (node (ref "J2") (pin "2") (pinfunction "2_2") (pintype "power_in"))
      (node (ref "U1") (pin "VDD") (pinfunction "VCC_VDD") (pintype "bidirectional"))
      (node (ref "U10") (pin "VDD") (pinfunction "VCC_VDD") (pintype "bidirectional"))
      (node (ref "U100") (pin "VDD") (pinfunction "VCC_VDD") (pintype "bidirectional"))
      (node (ref "U101") (pin "VDD") (pinfunction "VCC_VDD") (pintype "bidirectional"))
      (node (ref "U102") (pin "VDD") (pinfunction "VCC_VDD") (pintype "bidirectional"))
      (node (ref "U103") (pin "VDD") (pinfunction "VCC_VDD") (pintype "bidirectional"))
      (node (ref "U104") (pin "VDD") (pinfunction "VCC_VDD") (pintype "bidirectional"))
      (node (ref "U105") (pin "VDD") (pinfunction "VCC_VDD") (pintype "bidirectional"))
      (node (ref "U106") (pin "VDD") (pinfunction "VCC_VDD") (pintype "bidirectional"))
      (node (ref "U107") (pin "VDD") (pinfunction "VCC_VDD") (pintype "bidirectional"))
      (node (ref "U108") (pin "VDD") (pinfunction "VCC_VDD") (pintype "bidirectional"))
      (node (ref "U109") (pin "VDD") (pinfunction "VCC_VDD") (pintype "bidirectional"))
      (node (ref "U11") (pin "VDD") (pinfunction "VCC_VDD") (pintype "bidirectional"))
      (node (ref "U110") (pin "VDD") (pinfunction "VCC_VDD") (pintype "bidirectional"))
      (node (ref "U111") (pin "VDD") (pinfunction "VCC_VDD") (pintype "bidirectional"))
      (node (ref "U112") (pin "VDD") (pinfunction "VCC_VDD") (pintype "bidirectional"))
      (node (ref "U113") (pin "VDD") (pinfunction "VCC_VDD") (pintype "bidirectional"))
      (node (ref "U114") (pin "VDD") (pinfunction "VCC_VDD") (pintype "bidirectional"))
      (node (ref "U115") (pin "VDD") (pinfunction "VCC_VDD") (pintype "bidirectional"))
      (node (ref "U116") (pin "VDD") (pinfunction "VCC_VDD") (pintype "bidirectional"))
      (node (ref "U117") (pin "VDD") (pinfunction "VCC_VDD") (pintype "bidirectional"))
      (node (ref "U118") (pin "VDD") (pinfunction "VCC_VDD") (pintype "bidirectional"))
      (node (ref "U119") (pin "VDD") (pinfunction "VCC_VDD") (pintype "bidirectional"))
      (node (ref "U12") (pin "VDD") (pinfunction "VCC_VDD") (pintype "bidirectional"))
      (node (ref "U120") (pin "VDD") (pinfunction "VCC_VDD") (pintype "bidirectional"))
      (node (ref "U121") (pin "VDD") (pinfunction "VCC_VDD") (pintype "bidirectional"))
      (node (ref "U122") (pin "VDD") (pinfunction "VCC_VDD") (pintype "bidirectional"))
      (node (ref "U123") (pin "VDD") (pinfunction "VCC_VDD") (pintype "bidirectional"))
      (node (ref "U124") (pin "VDD") (pinfunction "VCC_VDD") (pintype "bidirectional"))
      (node (ref "U125") (pin "VDD") (pinfunction "VCC_VDD") (pintype "bidirectional"))
      (node (ref "U126") (pin "VDD") (pinfunction "VCC_VDD") (pintype "bidirectional"))
      (node (ref "U127") (pin "VDD") (pinfunction "VCC_VDD") (pintype "bidirectional"))
      (node (ref "U128") (pin "VDD") (pinfunction "VCC_VDD") (pintype "bidirectional"))
      (node (ref "U129") (pin "VDD") (pinfunction "VCC_VDD") (pintype "bidirectional"))
      (node (ref "U13") (pin "VDD") (pinfunction "VCC_VDD") (pintype "bidirectional"))
      (node (ref "U130") (pin "VDD") (pinfunction "VCC_VDD") (pintype "bidirectional"))
      (node (ref "U131") (pin "VDD") (pinfunction "VCC_VDD") (pintype "bidirectional"))
      (node (ref "U132") (pin "VDD") (pinfunction "VCC_VDD") (pintype "bidirectional"))
      (node (ref "U133") (pin "VDD") (pinfunction "VCC_VDD") (pintype "bidirectional"))
      (node (ref "U134") (pin "VDD") (pinfunction "VCC_VDD") (pintype "bidirectional"))
      (node (ref "U135") (pin "VDD") (pinfunction "VCC_VDD") (pintype "bidirectional"))
      (node (ref "U136") (pin "VDD") (pinfunction "VCC_VDD") (pintype "bidirectional"))
      (node (ref "U137") (pin "VDD") (pinfunction "VCC_VDD") (pintype "bidirectional"))
      (node (ref "U138") (pin "VDD") (pinfunction "VCC_VDD") (pintype "bidirectional"))
      (node (ref "U139") (pin "VDD") (pinfunction "VCC_VDD") (pintype "bidirectional"))
      (node (ref "U14") (pin "VDD") (pinfunction "VCC_VDD") (pintype "bidirectional"))
      (node (ref "U140") (pin "VDD") (pinfunction "VCC_VDD") (pintype "bidirectional"))
      (node (ref "U141") (pin "VDD") (pinfunction "VCC_VDD") (pintype "bidirectional"))
      (node (ref "U142") (pin "VDD") (pinfunction "VCC_VDD") (pintype "bidirectional"))
      (node (ref "U143") (pin "VDD") (pinfunction "VCC_VDD") (pintype "bidirectional"))
      (node (ref "U144") (pin "VDD") (pinfunction "VCC_VDD") (pintype "bidirectional"))
      (node (ref "U145") (pin "VDD") (pinfunction "VCC_VDD") (pintype "bidirectional"))
      (node (ref "U146") (pin "VDD") (pinfunction "VCC_VDD") (pintype "bidirectional"))
      (node (ref "U147") (pin "VDD") (pinfunction "VCC_VDD") (pintype "bidirectional"))
      (node (ref "U148") (pin "VDD") (pinfunction "VCC_VDD") (pintype "bidirectional"))
      (node (ref "U149") (pin "VDD") (pinfunction "VCC_VDD") (pintype "bidirectional"))
      (node (ref "U15") (pin "VDD") (pinfunction "VCC_VDD") (pintype "bidirectional"))
      (node (ref "U150") (pin "VDD") (pinfunction "VCC_VDD") (pintype "bidirectional"))
      (node (ref "U151") (pin "VDD") (pinfunction "VCC_VDD") (pintype "bidirectional"))
      (node (ref "U152") (pin "VDD") (pinfunction "VCC_VDD") (pintype "bidirectional"))
      (node (ref "U153") (pin "VDD") (pinfunction "VCC_VDD") (pintype "bidirectional"))
      (node (ref "U154") (pin "VDD") (pinfunction "VCC_VDD") (pintype "bidirectional"))
      (node (ref "U155") (pin "VDD") (pinfunction "VCC_VDD") (pintype "bidirectional"))
      (node (ref "U156") (pin "VDD") (pinfunction "VCC_VDD") (pintype "bidirectional"))
      (node (ref "U157") (pin "VDD") (pinfunction "VCC_VDD") (pintype "bidirectional"))
      (node (ref "U158") (pin "VDD") (pinfunction "VCC_VDD") (pintype "bidirectional"))
      (node (ref "U159") (pin "VDD") (pinfunction "VCC_VDD") (pintype "bidirectional"))
      (node (ref "U16") (pin "VDD") (pinfunction "VCC_VDD") (pintype "bidirectional"))
      (node (ref "U160") (pin "VDD") (pinfunction "VCC_VDD") (pintype "bidirectional"))
      (node (ref "U161") (pin "VDD") (pinfunction "VCC_VDD") (pintype "bidirectional"))
      (node (ref "U162") (pin "VDD") (pinfunction "VCC_VDD") (pintype "bidirectional"))
      (node (ref "U163") (pin "VDD") (pinfunction "VCC_VDD") (pintype "bidirectional"))
      (node (ref "U164") (pin "VDD") (pinfunction "VCC_VDD") (pintype "bidirectional"))
      (node (ref "U165") (pin "VDD") (pinfunction "VCC_VDD") (pintype "bidirectional"))
      (node (ref "U166") (pin "VDD") (pinfunction "VCC_VDD") (pintype "bidirectional"))
      (node (ref "U167") (pin "VDD") (pinfunction "VCC_VDD") (pintype "bidirectional"))
      (node (ref "U168") (pin "VDD") (pinfunction "VCC_VDD") (pintype "bidirectional"))
      (node (ref "U169") (pin "VDD") (pinfunction "VCC_VDD") (pintype "bidirectional"))
      (node (ref "U17") (pin "VDD") (pinfunction "VCC_VDD") (pintype "bidirectional"))
      (node (ref "U170") (pin "VDD") (pinfunction "VCC_VDD") (pintype "bidirectional"))
      (node (ref "U171") (pin "VDD") (pinfunction "VCC_VDD") (pintype "bidirectional"))
      (node (ref "U172") (pin "VDD") (pinfunction "VCC_VDD") (pintype "bidirectional"))
      (node (ref "U173") (pin "VDD") (pinfunction "VCC_VDD") (pintype "bidirectional"))
      (node (ref "U174") (pin "VDD") (pinfunction "VCC_VDD") (pintype "bidirectional"))
      (node (ref "U175") (pin "VDD") (pinfunction "VCC_VDD") (pintype "bidirectional"))
      (node (ref "U176") (pin "VDD") (pinfunction "VCC_VDD") (pintype "bidirectional"))
      (node (ref "U177") (pin "VDD") (pinfunction "VCC_VDD") (pintype "bidirectional"))
      (node (ref "U178") (pin "VDD") (pinfunction "VCC_VDD") (pintype "bidirectional"))
      (node (ref "U179") (pin "VDD") (pinfunction "VCC_VDD") (pintype "bidirectional"))
      (node (ref "U18") (pin "VDD") (pinfunction "VCC_VDD") (pintype "bidirectional"))
      (node (ref "U180") (pin "VDD") (pinfunction "VCC_VDD") (pintype "bidirectional"))
      (node (ref "U181") (pin "VDD") (pinfunction "VCC_VDD") (pintype "bidirectional"))
      (node (ref "U182") (pin "VDD") (pinfunction "VCC_VDD") (pintype "bidirectional"))
      (node (ref "U183") (pin "VDD") (pinfunction "VCC_VDD") (pintype "bidirectional"))
      (node (ref "U184") (pin "VDD") (pinfunction "VCC_VDD") (pintype "bidirectional"))
      (node (ref "U185") (pin "VDD") (pinfunction "VCC_VDD") (pintype "bidirectional"))
      (node (ref "U186") (pin "VDD") (pinfunction "VCC_VDD") (pintype "bidirectional"))
      (node (ref "U187") (pin "VDD") (pinfunction "VCC_VDD") (pintype "bidirectional"))
      (node (ref "U188") (pin "VDD") (pinfunction "VCC_VDD") (pintype "bidirectional"))
      (node (ref "U189") (pin "VDD") (pinfunction "VCC_VDD") (pintype "bidirectional"))
      (node (ref "U19") (pin "VDD") (pinfunction "VCC_VDD") (pintype "bidirectional"))
      (node (ref "U190") (pin "VDD") (pinfunction "VCC_VDD") (pintype "bidirectional"))
      (node (ref "U191") (pin "VDD") (pinfunction "VCC_VDD") (pintype "bidirectional"))
      (node (ref "U192") (pin "VDD") (pinfunction "VCC_VDD") (pintype "bidirectional"))
      (node (ref "U193") (pin "VDD") (pinfunction "VCC_VDD") (pintype "bidirectional"))
      (node (ref "U194") (pin "VDD") (pinfunction "VCC_VDD") (pintype "bidirectional"))
      (node (ref "U195") (pin "VDD") (pinfunction "VCC_VDD") (pintype "bidirectional"))
      (node (ref "U196") (pin "VDD") (pinfunction "VCC_VDD") (pintype "bidirectional"))
      (node (ref "U197") (pin "VDD") (pinfunction "VCC_VDD") (pintype "bidirectional"))
      (node (ref "U198") (pin "VDD") (pinfunction "VCC_VDD") (pintype "bidirectional"))
      (node (ref "U199") (pin "VDD") (pinfunction "VCC_VDD") (pintype "bidirectional"))
      (node (ref "U2") (pin "VDD") (pinfunction "VCC_VDD") (pintype "bidirectional"))
      (node (ref "U20") (pin "VDD") (pinfunction "VCC_VDD") (pintype "bidirectional"))
      (node (ref "U200") (pin "VDD") (pinfunction "VCC_VDD") (pintype "bidirectional"))
      (node (ref "U201") (pin "VDD") (pinfunction "VCC_VDD") (pintype "bidirectional"))
      (node (ref "U202") (pin "VDD") (pinfunction "VCC_VDD") (pintype "bidirectional"))
      (node (ref "U203") (pin "VDD") (pinfunction "VCC_VDD") (pintype "bidirectional"))
      (node (ref "U204") (pin "VDD") (pinfunction "VCC_VDD") (pintype "bidirectional"))
      (node (ref "U205") (pin "VDD") (pinfunction "VCC_VDD") (pintype "bidirectional"))
      (node (ref "U206") (pin "VDD") (pinfunction "VCC_VDD") (pintype "bidirectional"))
      (node (ref "U207") (pin "VDD") (pinfunction "VCC_VDD") (pintype "bidirectional"))
      (node (ref "U208") (pin "VDD") (pinfunction "VCC_VDD") (pintype "bidirectional"))
      (node (ref "U209") (pin "VDD") (pinfunction "VCC_VDD") (pintype "bidirectional"))
      (node (ref "U21") (pin "VDD") (pinfunction "VCC_VDD") (pintype "bidirectional"))
      (node (ref "U210") (pin "VDD") (pinfunction "VCC_VDD") (pintype "bidirectional"))
      (node (ref "U211") (pin "VDD") (pinfunction "VCC_VDD") (pintype "bidirectional"))
      (node (ref "U212") (pin "VDD") (pinfunction "VCC_VDD") (pintype "bidirectional"))
      (node (ref "U213") (pin "VDD") (pinfunction "VCC_VDD") (pintype "bidirectional"))
      (node (ref "U214") (pin "VDD") (pinfunction "VCC_VDD") (pintype "bidirectional"))
      (node (ref "U215") (pin "VDD") (pinfunction "VCC_VDD") (pintype "bidirectional"))
      (node (ref "U216") (pin "VDD") (pinfunction "VCC_VDD") (pintype "bidirectional"))
      (node (ref "U217") (pin "VDD") (pinfunction "VCC_VDD") (pintype "bidirectional"))
      (node (ref "U218") (pin "VDD") (pinfunction "VCC_VDD") (pintype "bidirectional"))
      (node (ref "U219") (pin "VDD") (pinfunction "VCC_VDD") (pintype "bidirectional"))
      (node (ref "U22") (pin "VDD") (pinfunction "VCC_VDD") (pintype "bidirectional"))
      (node (ref "U220") (pin "VDD") (pinfunction "VCC_VDD") (pintype "bidirectional"))
      (node (ref "U221") (pin "VDD") (pinfunction "VCC_VDD") (pintype "bidirectional"))
      (node (ref "U222") (pin "VDD") (pinfunction "VCC_VDD") (pintype "bidirectional"))
      (node (ref "U223") (pin "VDD") (pinfunction "VCC_VDD") (pintype "bidirectional"))
      (node (ref "U224") (pin "VDD") (pinfunction "VCC_VDD") (pintype "bidirectional"))
      (node (ref "U225") (pin "VDD") (pinfunction "VCC_VDD") (pintype "bidirectional"))
      (node (ref "U226") (pin "VDD") (pinfunction "VCC_VDD") (pintype "bidirectional"))
      (node (ref "U227") (pin "VDD") (pinfunction "VCC_VDD") (pintype "bidirectional"))
      (node (ref "U228") (pin "VDD") (pinfunction "VCC_VDD") (pintype "bidirectional"))
      (node (ref "U229") (pin "VDD") (pinfunction "VCC_VDD") (pintype "bidirectional"))
      (node (ref "U23") (pin "VDD") (pinfunction "VCC_VDD") (pintype "bidirectional"))
      (node (ref "U230") (pin "VDD") (pinfunction "VCC_VDD") (pintype "bidirectional"))
      (node (ref "U231") (pin "VDD") (pinfunction "VCC_VDD") (pintype "bidirectional"))
      (node (ref "U232") (pin "VDD") (pinfunction "VCC_VDD") (pintype "bidirectional"))
      (node (ref "U233") (pin "VDD") (pinfunction "VCC_VDD") (pintype "bidirectional"))
      (node (ref "U234") (pin "VDD") (pinfunction "VCC_VDD") (pintype "bidirectional"))
      (node (ref "U235") (pin "VDD") (pinfunction "VCC_VDD") (pintype "bidirectional"))
      (node (ref "U236") (pin "VDD") (pinfunction "VCC_VDD") (pintype "bidirectional"))
      (node (ref "U237") (pin "VDD") (pinfunction "VCC_VDD") (pintype "bidirectional"))
      (node (ref "U238") (pin "VDD") (pinfunction "VCC_VDD") (pintype "bidirectional"))
      (node (ref "U239") (pin "VDD") (pinfunction "VCC_VDD") (pintype "bidirectional"))
      (node (ref "U24") (pin "VDD") (pinfunction "VCC_VDD") (pintype "bidirectional"))
      (node (ref "U240") (pin "VDD") (pinfunction "VCC_VDD") (pintype "bidirectional"))
      (node (ref "U241") (pin "VDD") (pinfunction "VCC_VDD") (pintype "bidirectional"))
      (node (ref "U242") (pin "VDD") (pinfunction "VCC_VDD") (pintype "bidirectional"))
      (node (ref "U243") (pin "VDD") (pinfunction "VCC_VDD") (pintype "bidirectional"))
      (node (ref "U244") (pin "VDD") (pinfunction "VCC_VDD") (pintype "bidirectional"))
      (node (ref "U245") (pin "VDD") (pinfunction "VCC_VDD") (pintype "bidirectional"))
      (node (ref "U246") (pin "VDD") (pinfunction "VCC_VDD") (pintype "bidirectional"))
      (node (ref "U247") (pin "VDD") (pinfunction "VCC_VDD") (pintype "bidirectional"))
      (node (ref "U248") (pin "VDD") (pinfunction "VCC_VDD") (pintype "bidirectional"))
      (node (ref "U249") (pin "VDD") (pinfunction "VCC_VDD") (pintype "bidirectional"))
      (node (ref "U25") (pin "VDD") (pinfunction "VCC_VDD") (pintype "bidirectional"))
      (node (ref "U250") (pin "VDD") (pinfunction "VCC_VDD") (pintype "bidirectional"))
      (node (ref "U251") (pin "VDD") (pinfunction "VCC_VDD") (pintype "bidirectional"))
      (node (ref "U252") (pin "VDD") (pinfunction "VCC_VDD") (pintype "bidirectional"))
      (node (ref "U26") (pin "VDD") (pinfunction "VCC_VDD") (pintype "bidirectional"))
      (node (ref "U27") (pin "VDD") (pinfunction "VCC_VDD") (pintype "bidirectional"))
      (node (ref "U28") (pin "VDD") (pinfunction "VCC_VDD") (pintype "bidirectional"))
      (node (ref "U29") (pin "VDD") (pinfunction "VCC_VDD") (pintype "bidirectional"))
      (node (ref "U3") (pin "VDD") (pinfunction "VCC_VDD") (pintype "bidirectional"))
      (node (ref "U30") (pin "VDD") (pinfunction "VCC_VDD") (pintype "bidirectional"))
      (node (ref "U31") (pin "VDD") (pinfunction "VCC_VDD") (pintype "bidirectional"))
      (node (ref "U32") (pin "VDD") (pinfunction "VCC_VDD") (pintype "bidirectional"))
      (node (ref "U33") (pin "VDD") (pinfunction "VCC_VDD") (pintype "bidirectional"))
      (node (ref "U34") (pin "VDD") (pinfunction "VCC_VDD") (pintype "bidirectional"))
      (node (ref "U35") (pin "VDD") (pinfunction "VCC_VDD") (pintype "bidirectional"))
      (node (ref "U36") (pin "VDD") (pinfunction "VCC_VDD") (pintype "bidirectional"))
      (node (ref "U37") (pin "VDD") (pinfunction "VCC_VDD") (pintype "bidirectional"))
      (node (ref "U38") (pin "VDD") (pinfunction "VCC_VDD") (pintype "bidirectional"))
      (node (ref "U39") (pin "VDD") (pinfunction "VCC_VDD") (pintype "bidirectional"))
      (node (ref "U4") (pin "VDD") (pinfunction "VCC_VDD") (pintype "bidirectional"))
      (node (ref "U40") (pin "VDD") (pinfunction "VCC_VDD") (pintype "bidirectional"))
      (node (ref "U41") (pin "VDD") (pinfunction "VCC_VDD") (pintype "bidirectional"))
      (node (ref "U42") (pin "VDD") (pinfunction "VCC_VDD") (pintype "bidirectional"))
      (node (ref "U43") (pin "VDD") (pinfunction "VCC_VDD") (pintype "bidirectional"))
      (node (ref "U44") (pin "VDD") (pinfunction "VCC_VDD") (pintype "bidirectional"))
      (node (ref "U45") (pin "VDD") (pinfunction "VCC_VDD") (pintype "bidirectional"))
      (node (ref "U46") (pin "VDD") (pinfunction "VCC_VDD") (pintype "bidirectional"))
      (node (ref "U47") (pin "VDD") (pinfunction "VCC_VDD") (pintype "bidirectional"))
      (node (ref "U48") (pin "VDD") (pinfunction "VCC_VDD") (pintype "bidirectional"))
      (node (ref "U49") (pin "VDD") (pinfunction "VCC_VDD") (pintype "bidirectional"))
      (node (ref "U5") (pin "VDD") (pinfunction "VCC_VDD") (pintype "bidirectional"))
      (node (ref "U50") (pin "VDD") (pinfunction "VCC_VDD") (pintype "bidirectional"))
      (node (ref "U51") (pin "VDD") (pinfunction "VCC_VDD") (pintype "bidirectional"))
      (node (ref "U52") (pin "VDD") (pinfunction "VCC_VDD") (pintype "bidirectional"))
      (node (ref "U53") (pin "VDD") (pinfunction "VCC_VDD") (pintype "bidirectional"))
      (node (ref "U54") (pin "VDD") (pinfunction "VCC_VDD") (pintype "bidirectional"))
      (node (ref "U55") (pin "VDD") (pinfunction "VCC_VDD") (pintype "bidirectional"))
      (node (ref "U56") (pin "VDD") (pinfunction "VCC_VDD") (pintype "bidirectional"))
      (node (ref "U57") (pin "VDD") (pinfunction "VCC_VDD") (pintype "bidirectional"))
      (node (ref "U58") (pin "VDD") (pinfunction "VCC_VDD") (pintype "bidirectional"))
      (node (ref "U59") (pin "VDD") (pinfunction "VCC_VDD") (pintype "bidirectional"))
      (node (ref "U6") (pin "VDD") (pinfunction "VCC_VDD") (pintype "bidirectional"))
      (node (ref "U60") (pin "VDD") (pinfunction "VCC_VDD") (pintype "bidirectional"))
      (node (ref "U61") (pin "VDD") (pinfunction "VCC_VDD") (pintype "bidirectional"))
      (node (ref "U62") (pin "VDD") (pinfunction "VCC_VDD") (pintype "bidirectional"))
      (node (ref "U63") (pin "VDD") (pinfunction "VCC_VDD") (pintype "bidirectional"))
      (node (ref "U64") (pin "VDD") (pinfunction "VCC_VDD") (pintype "bidirectional"))
      (node (ref "U65") (pin "VDD") (pinfunction "VCC_VDD") (pintype "bidirectional"))
      (node (ref "U66") (pin "VDD") (pinfunction "VCC_VDD") (pintype "bidirectional"))
      (node (ref "U67") (pin "VDD") (pinfunction "VCC_VDD") (pintype "bidirectional"))
      (node (ref "U68") (pin "VDD") (pinfunction "VCC_VDD") (pintype "bidirectional"))
      (node (ref "U69") (pin "VDD") (pinfunction "VCC_VDD") (pintype "bidirectional"))
      (node (ref "U7") (pin "VDD") (pinfunction "VCC_VDD") (pintype "bidirectional"))
      (node (ref "U70") (pin "VDD") (pinfunction "VCC_VDD") (pintype "bidirectional"))
      (node (ref "U71") (pin "VDD") (pinfunction "VCC_VDD") (pintype "bidirectional"))
      (node (ref "U72") (pin "VDD") (pinfunction "VCC_VDD") (pintype "bidirectional"))
      (node (ref "U73") (pin "VDD") (pinfunction "VCC_VDD") (pintype "bidirectional"))
      (node (ref "U74") (pin "VDD") (pinfunction "VCC_VDD") (pintype "bidirectional"))
      (node (ref "U75") (pin "VDD") (pinfunction "VCC_VDD") (pintype "bidirectional"))
      (node (ref "U76") (pin "VDD") (pinfunction "VCC_VDD") (pintype "bidirectional"))
      (node (ref "U77") (pin "VDD") (pinfunction "VCC_VDD") (pintype "bidirectional"))
      (node (ref "U78") (pin "VDD") (pinfunction "VCC_VDD") (pintype "bidirectional"))
      (node (ref "U79") (pin "VDD") (pinfunction "VCC_VDD") (pintype "bidirectional"))
      (node (ref "U8") (pin "VDD") (pinfunction "VCC_VDD") (pintype "bidirectional"))
      (node (ref "U80") (pin "VDD") (pinfunction "VCC_VDD") (pintype "bidirectional"))
      (node (ref "U81") (pin "VDD") (pinfunction "VCC_VDD") (pintype "bidirectional"))
      (node (ref "U82") (pin "VDD") (pinfunction "VCC_VDD") (pintype "bidirectional"))
      (node (ref "U83") (pin "VDD") (pinfunction "VCC_VDD") (pintype "bidirectional"))
      (node (ref "U84") (pin "VDD") (pinfunction "VCC_VDD") (pintype "bidirectional"))
      (node (ref "U85") (pin "VDD") (pinfunction "VCC_VDD") (pintype "bidirectional"))
      (node (ref "U86") (pin "VDD") (pinfunction "VCC_VDD") (pintype "bidirectional"))
      (node (ref "U87") (pin "VDD") (pinfunction "VCC_VDD") (pintype "bidirectional"))
      (node (ref "U88") (pin "VDD") (pinfunction "VCC_VDD") (pintype "bidirectional"))
      (node (ref "U89") (pin "VDD") (pinfunction "VCC_VDD") (pintype "bidirectional"))
      (node (ref "U9") (pin "VDD") (pinfunction "VCC_VDD") (pintype "bidirectional"))
      (node (ref "U90") (pin "VDD") (pinfunction "VCC_VDD") (pintype "bidirectional"))
      (node (ref "U91") (pin "VDD") (pinfunction "VCC_VDD") (pintype "bidirectional"))
      (node (ref "U92") (pin "VDD") (pinfunction "VCC_VDD") (pintype "bidirectional"))
      (node (ref "U93") (pin "VDD") (pinfunction "VCC_VDD") (pintype "bidirectional"))
      (node (ref "U94") (pin "VDD") (pinfunction "VCC_VDD") (pintype "bidirectional"))
      (node (ref "U95") (pin "VDD") (pinfunction "VCC_VDD") (pintype "bidirectional"))
      (node (ref "U96") (pin "VDD") (pinfunction "VCC_VDD") (pintype "bidirectional"))
      (node (ref "U97") (pin "VDD") (pinfunction "VCC_VDD") (pintype "bidirectional"))
      (node (ref "U98") (pin "VDD") (pinfunction "VCC_VDD") (pintype "bidirectional"))
      (node (ref "U99") (pin "VDD") (pinfunction "VCC_VDD") (pintype "bidirectional"))
    )
    (net (code "507") (name "unconnected-(U126-CO-PadCKO)") (class "Default")
      (node (ref "U126") (pin "CKO") (pinfunction "CO_CKO") (pintype "bidirectional"))
    )
    (net (code "508") (name "unconnected-(U126-DO-PadSDO)") (class "Default")
      (node (ref "U126") (pin "SDO") (pinfunction "DO_SDO") (pintype "bidirectional"))
    )
    (net (code "509") (name "unconnected-(U252-CO-PadCKO)") (class "Default")
      (node (ref "U252") (pin "CKO") (pinfunction "CO_CKO") (pintype "bidirectional"))
    )
    (net (code "510") (name "unconnected-(U252-DO-PadSDO)") (class "Default")
      (node (ref "U252") (pin "SDO") (pinfunction "DO_SDO") (pintype "bidirectional"))
    )
  )
)
